# V6_01.net
KiCad netlist of a schematic drawn in Altium Designer
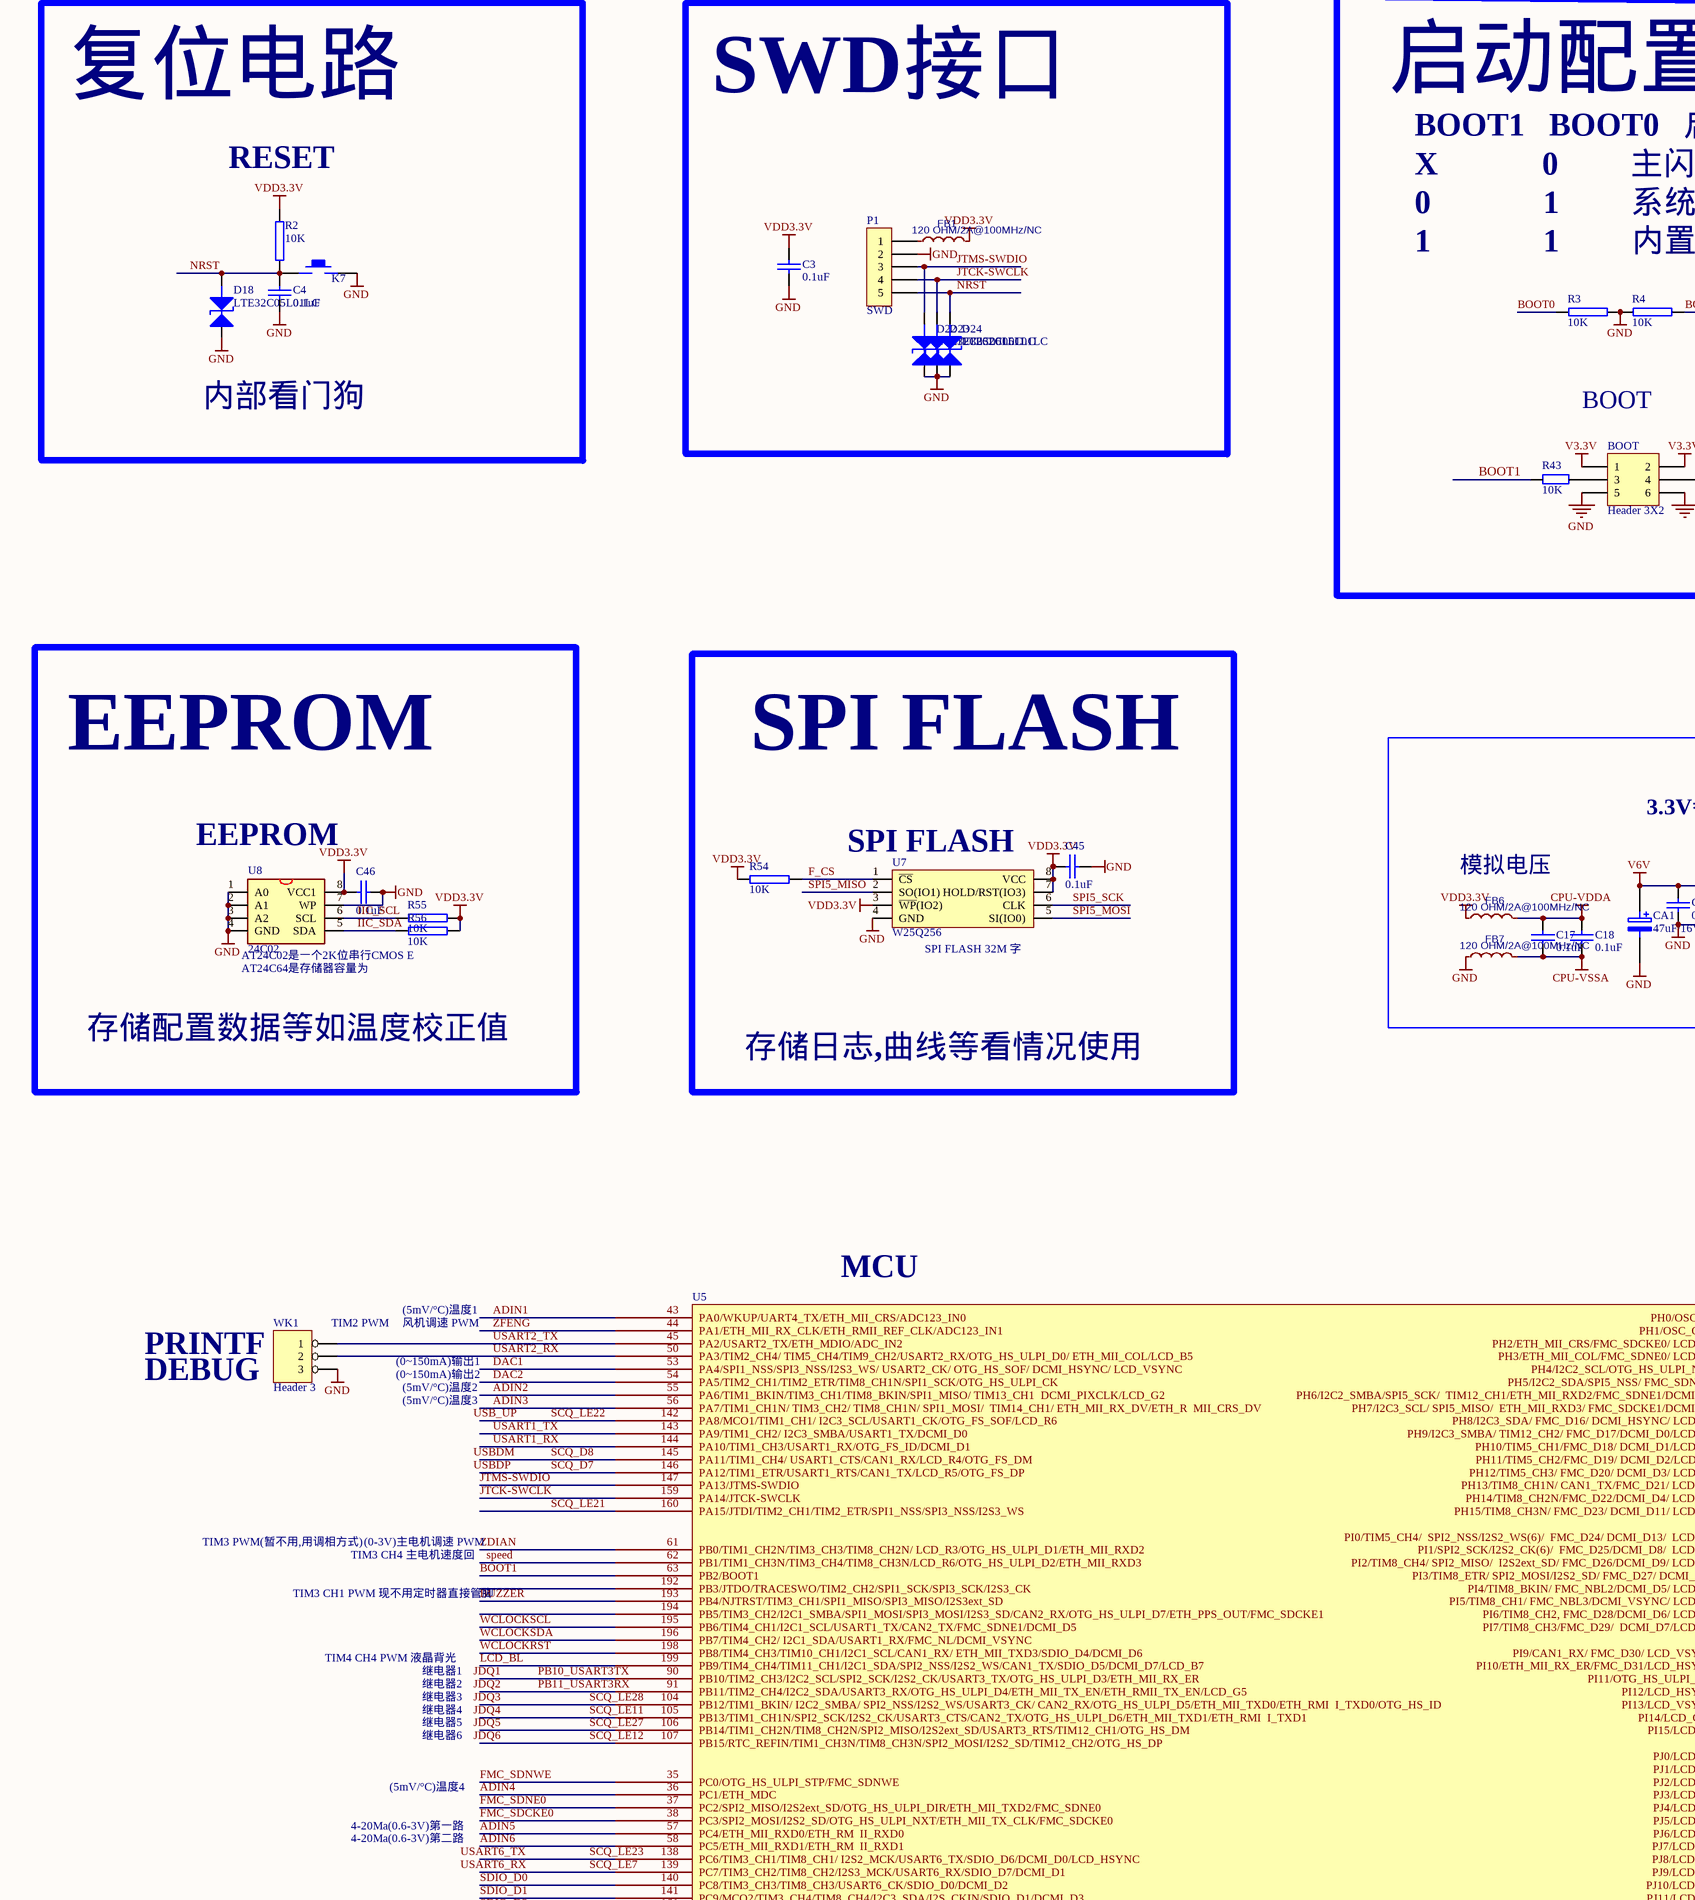
[diagram p0: 盲人学习机V6.01.SchDoc, top left]
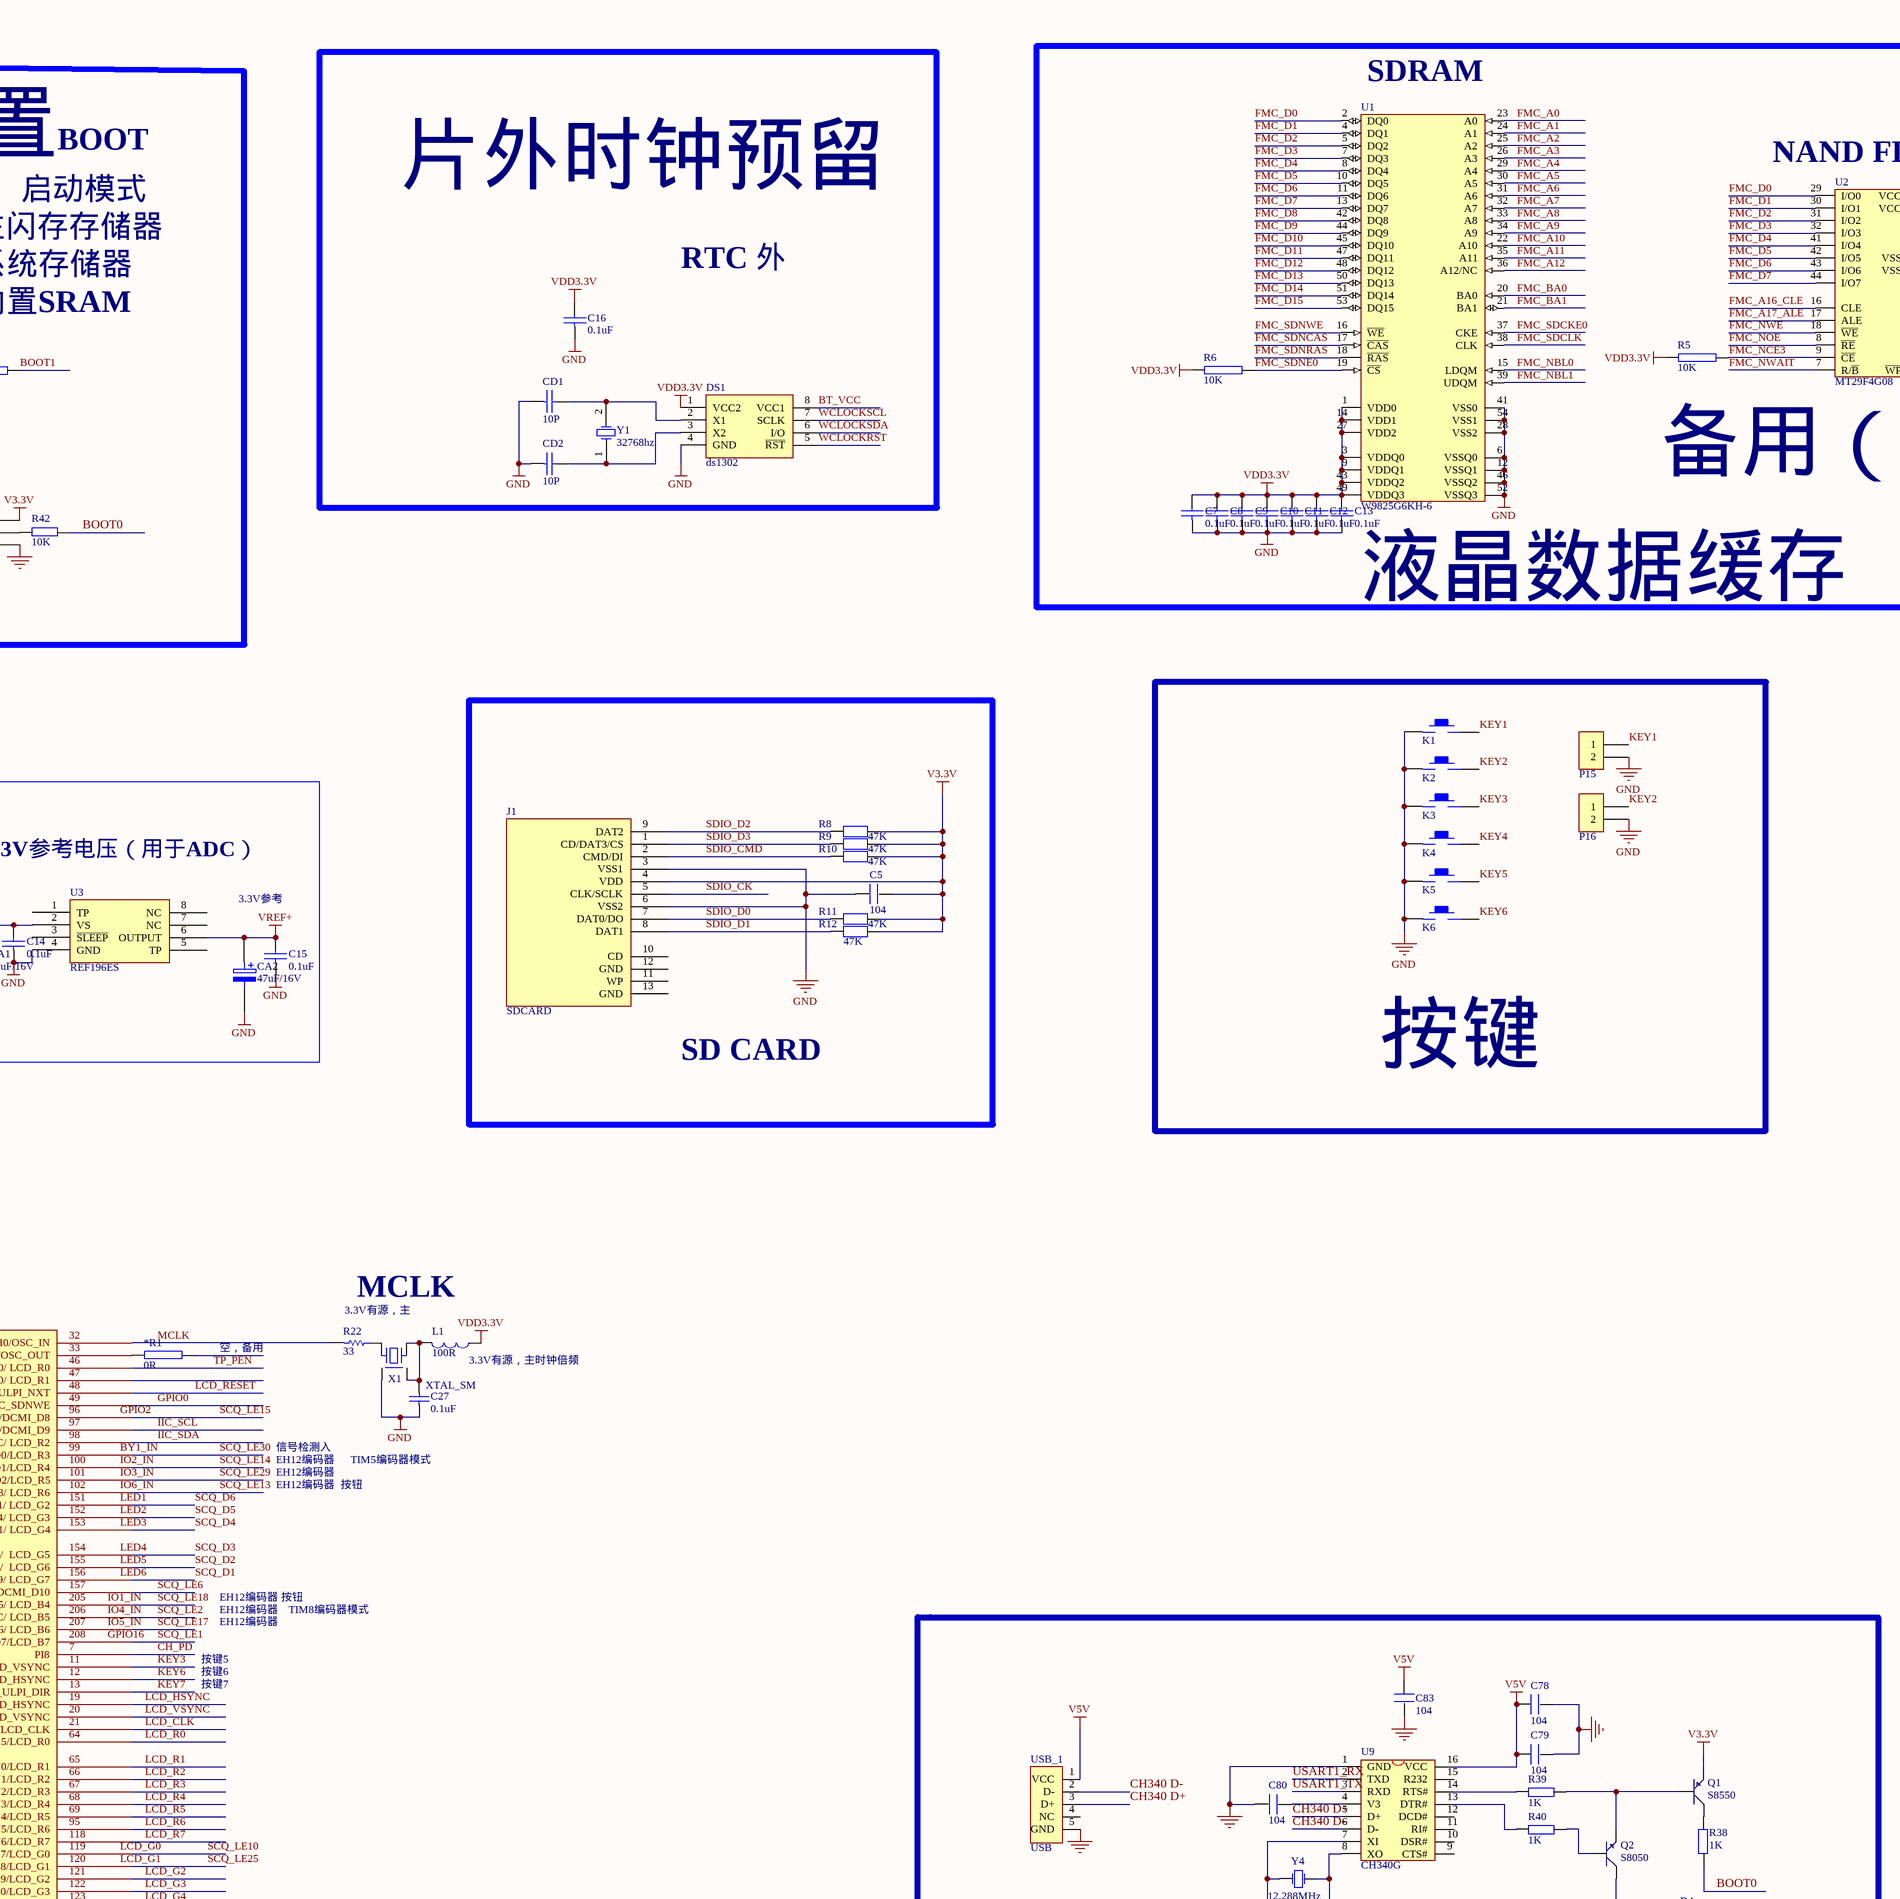
[diagram p1: 盲人学习机V6.01.SchDoc, top middle]
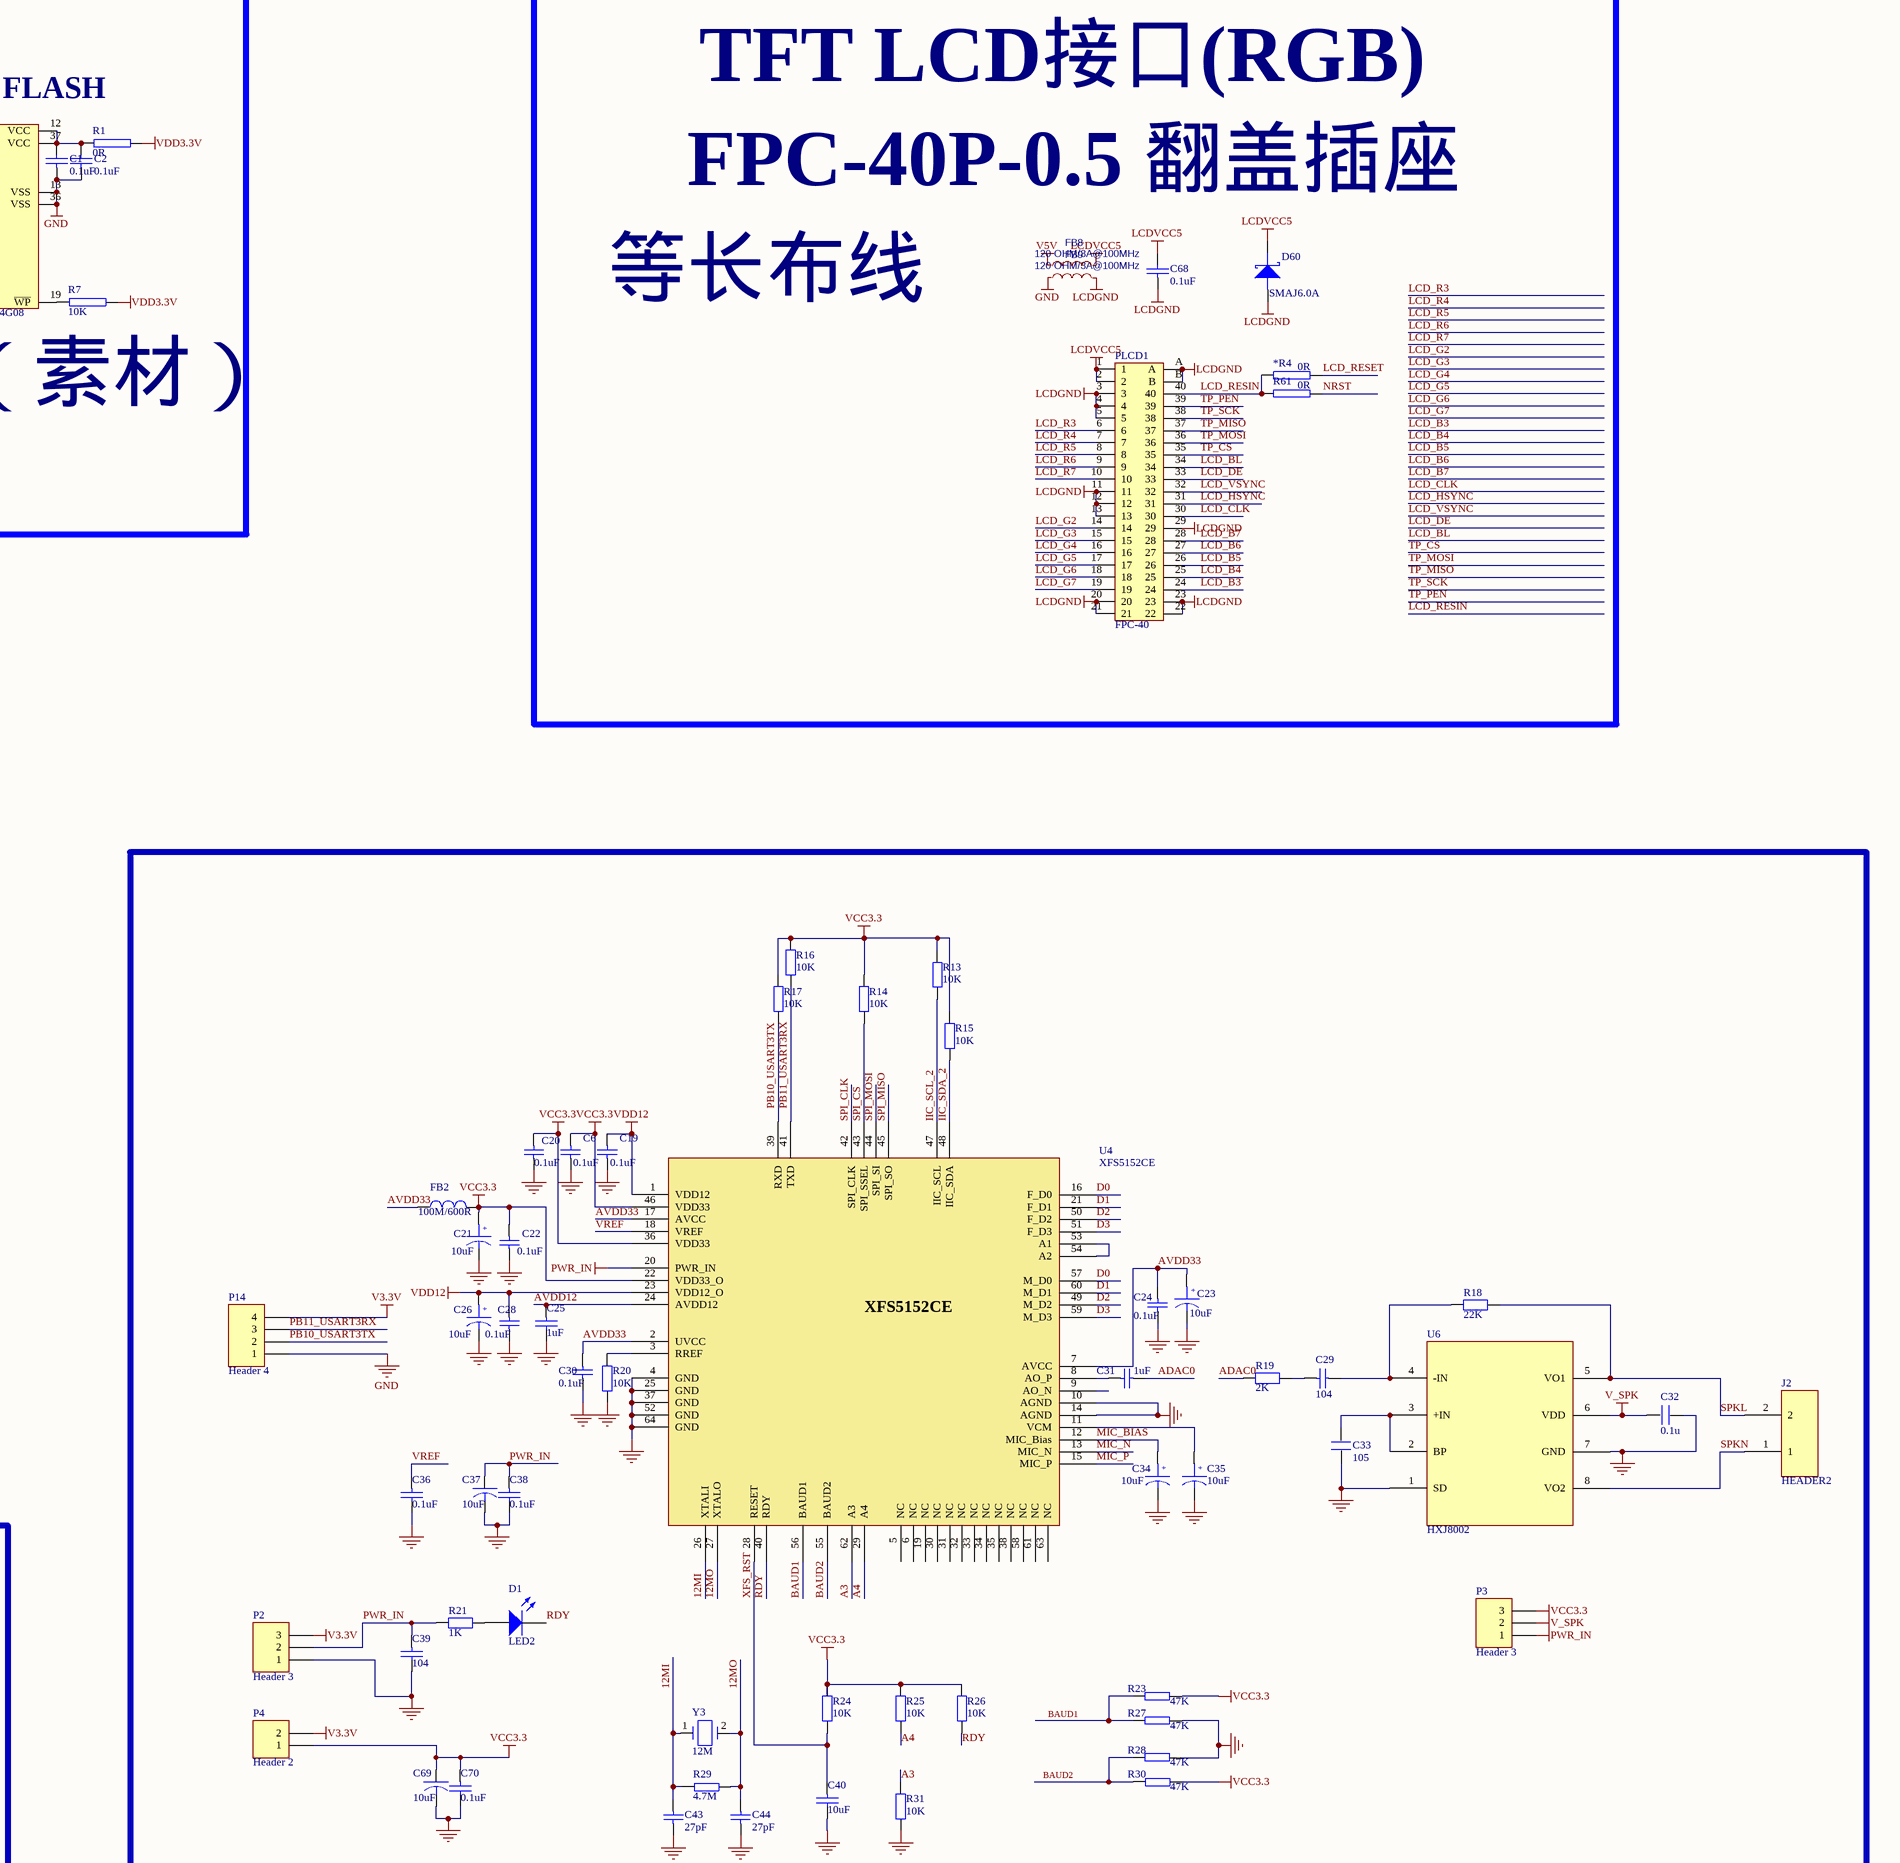
[diagram p2: 盲人学习机V6.01.SchDoc, top right]
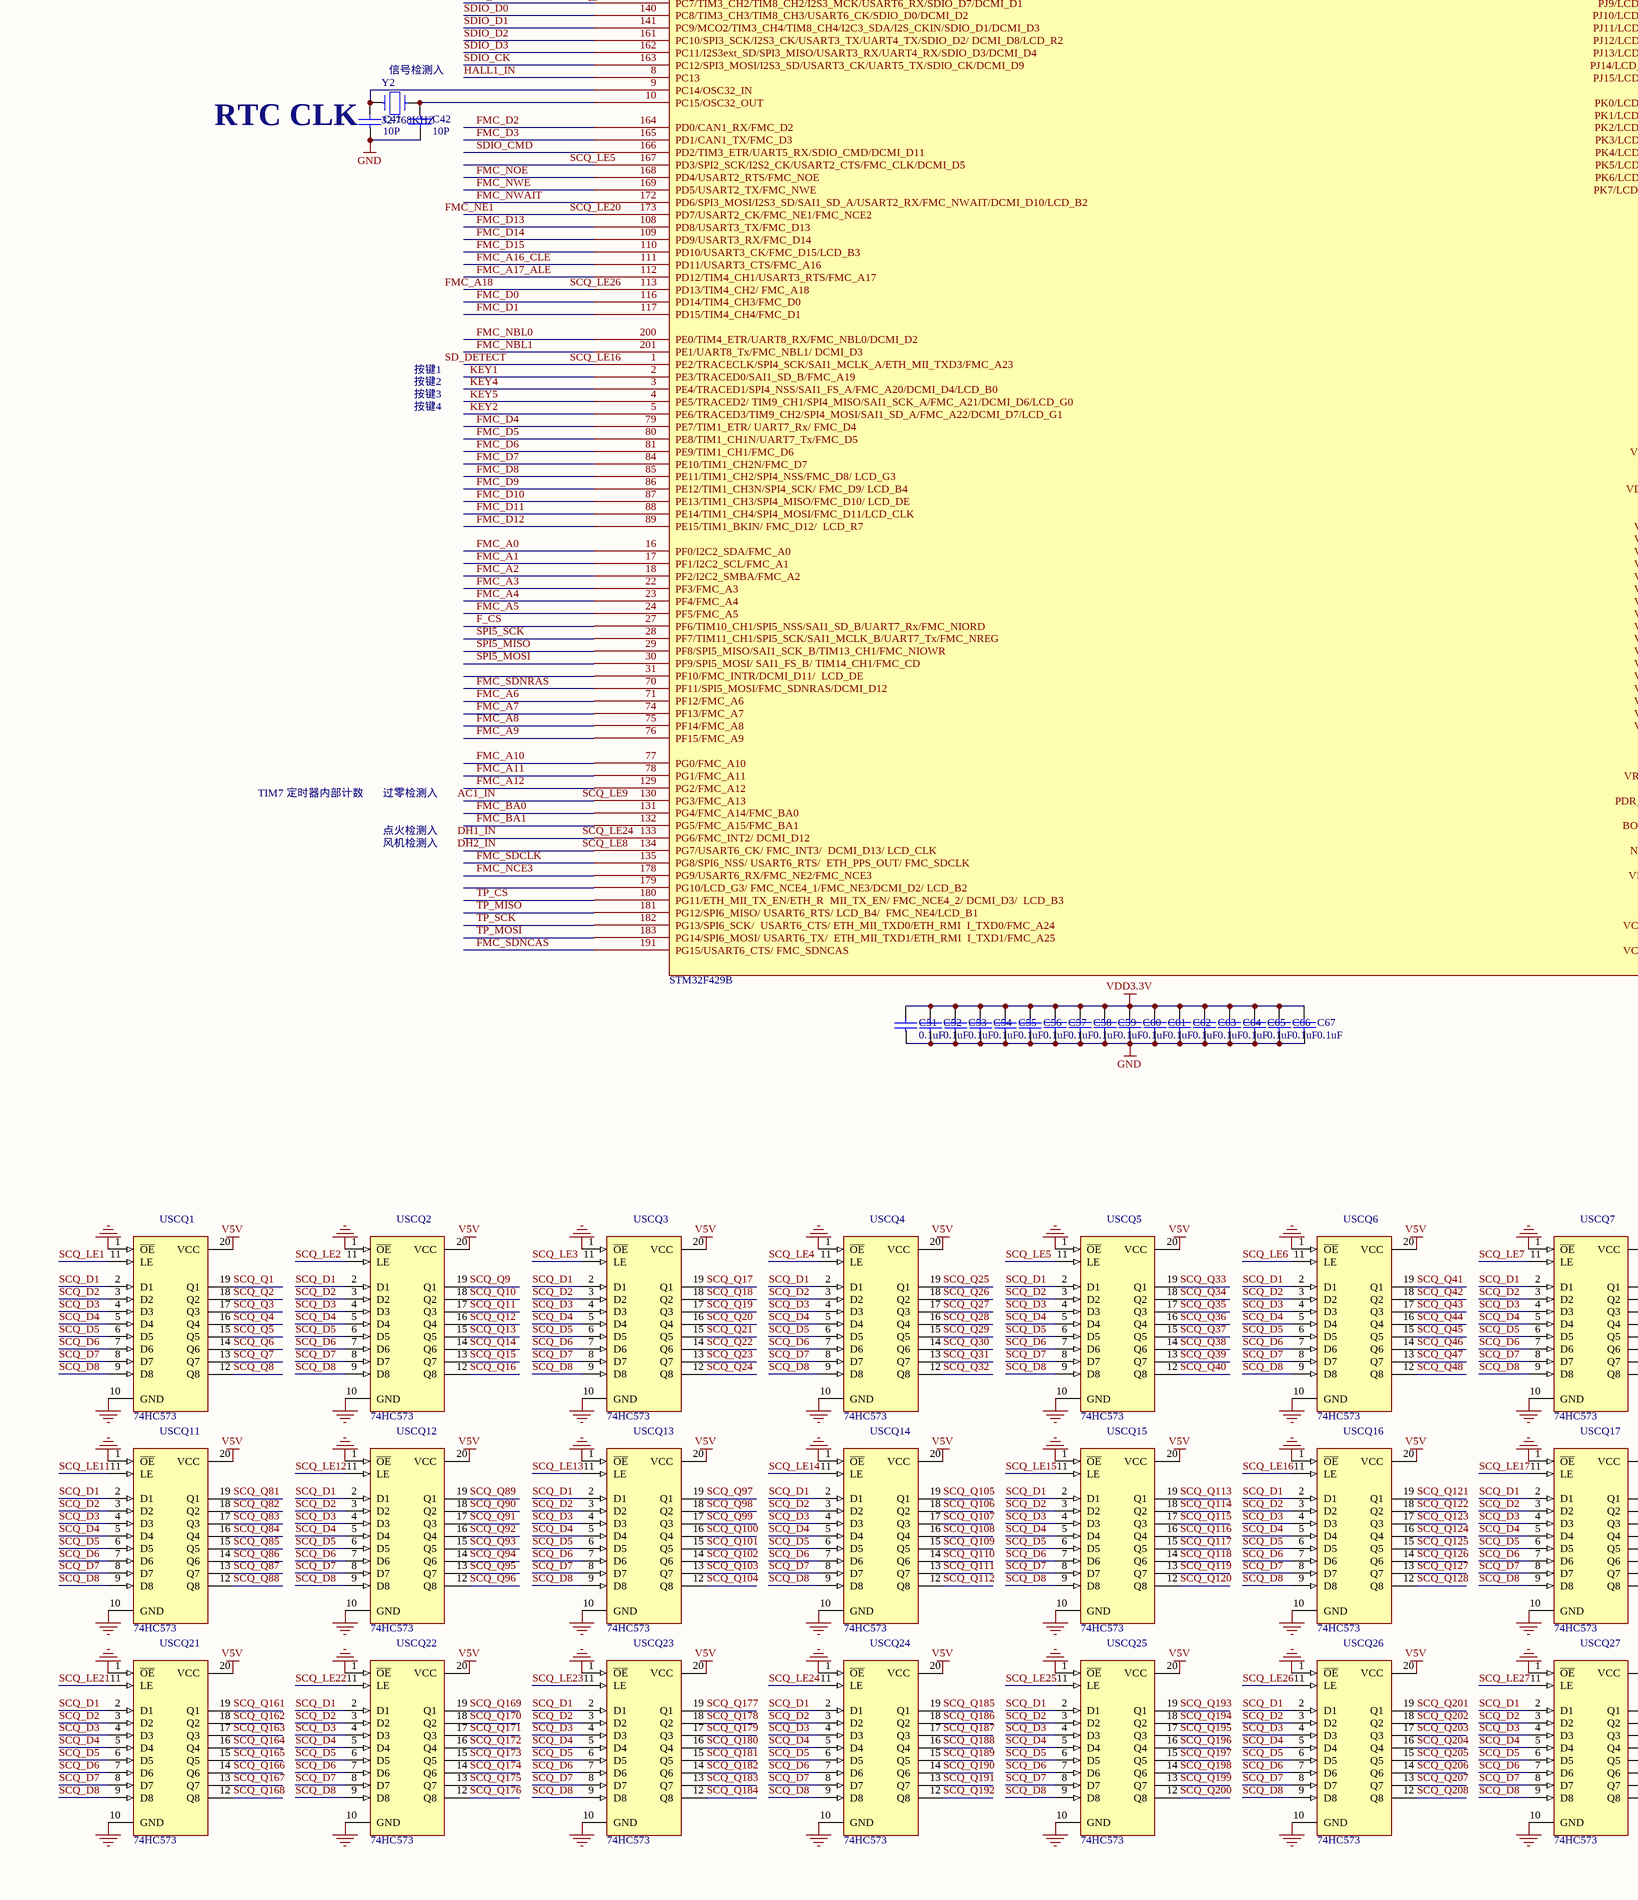
[diagram p3: 盲人学习机V6.01.SchDoc, bottom left]
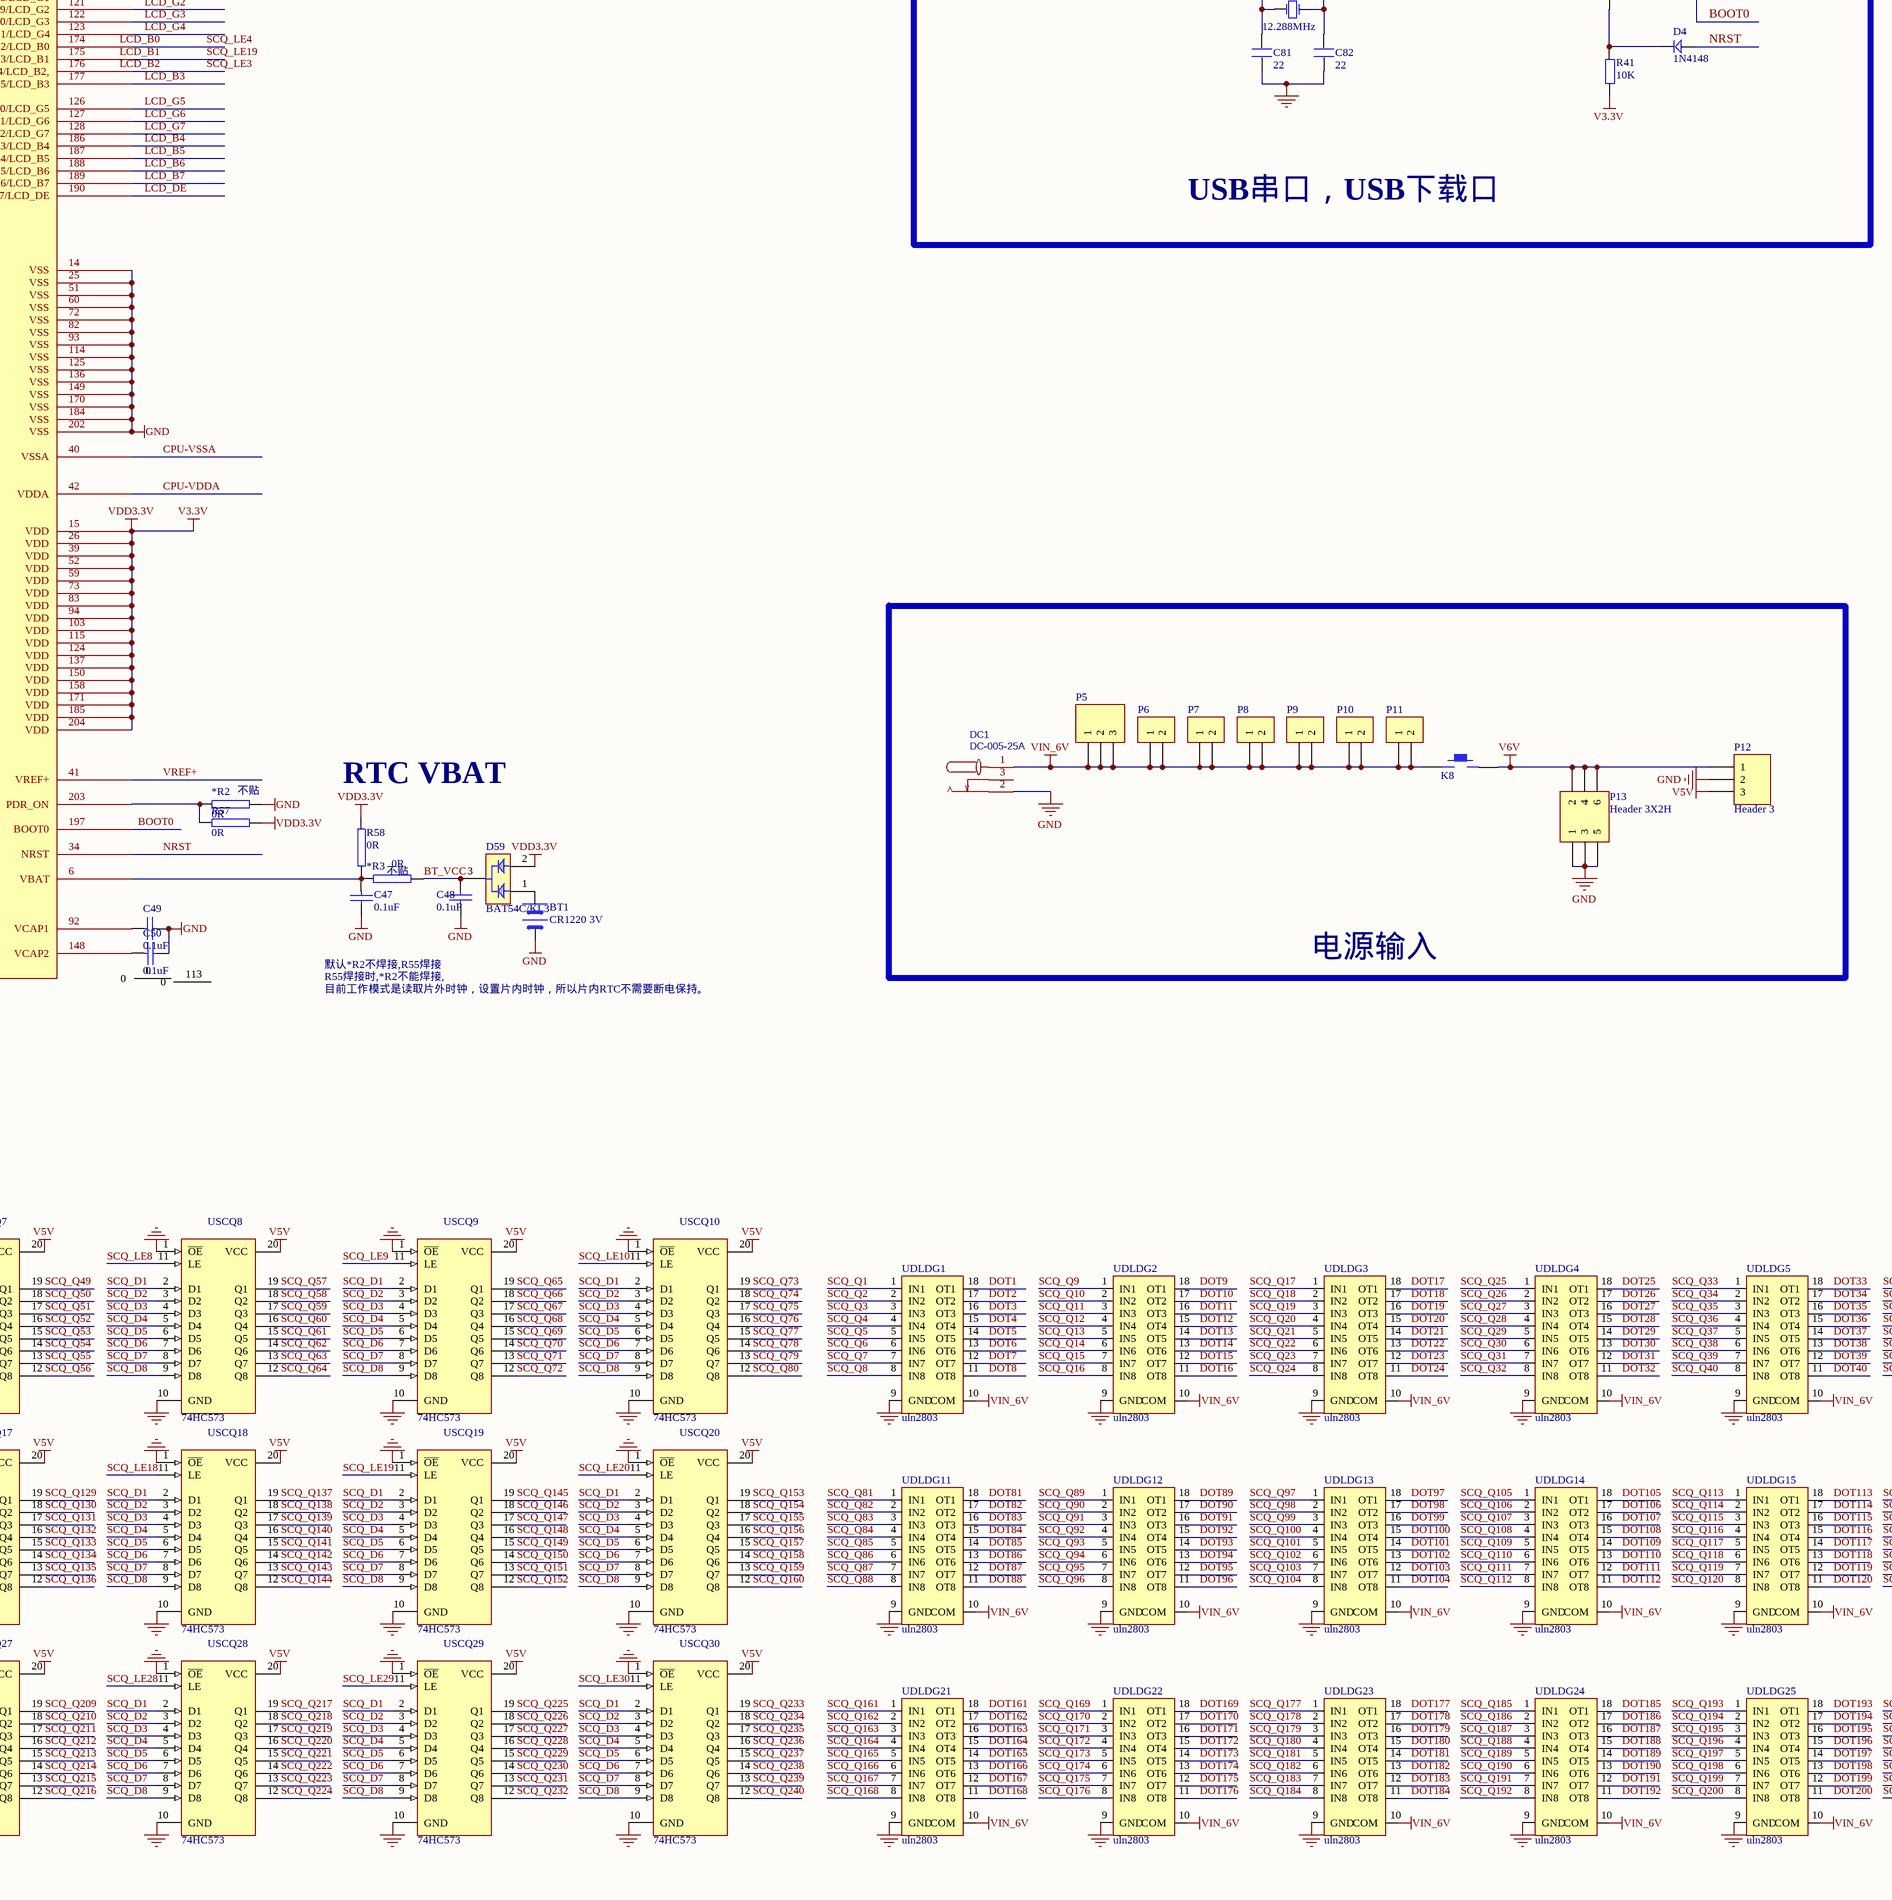
[diagram p4: 盲人学习机V6.01.SchDoc, bottom middle]
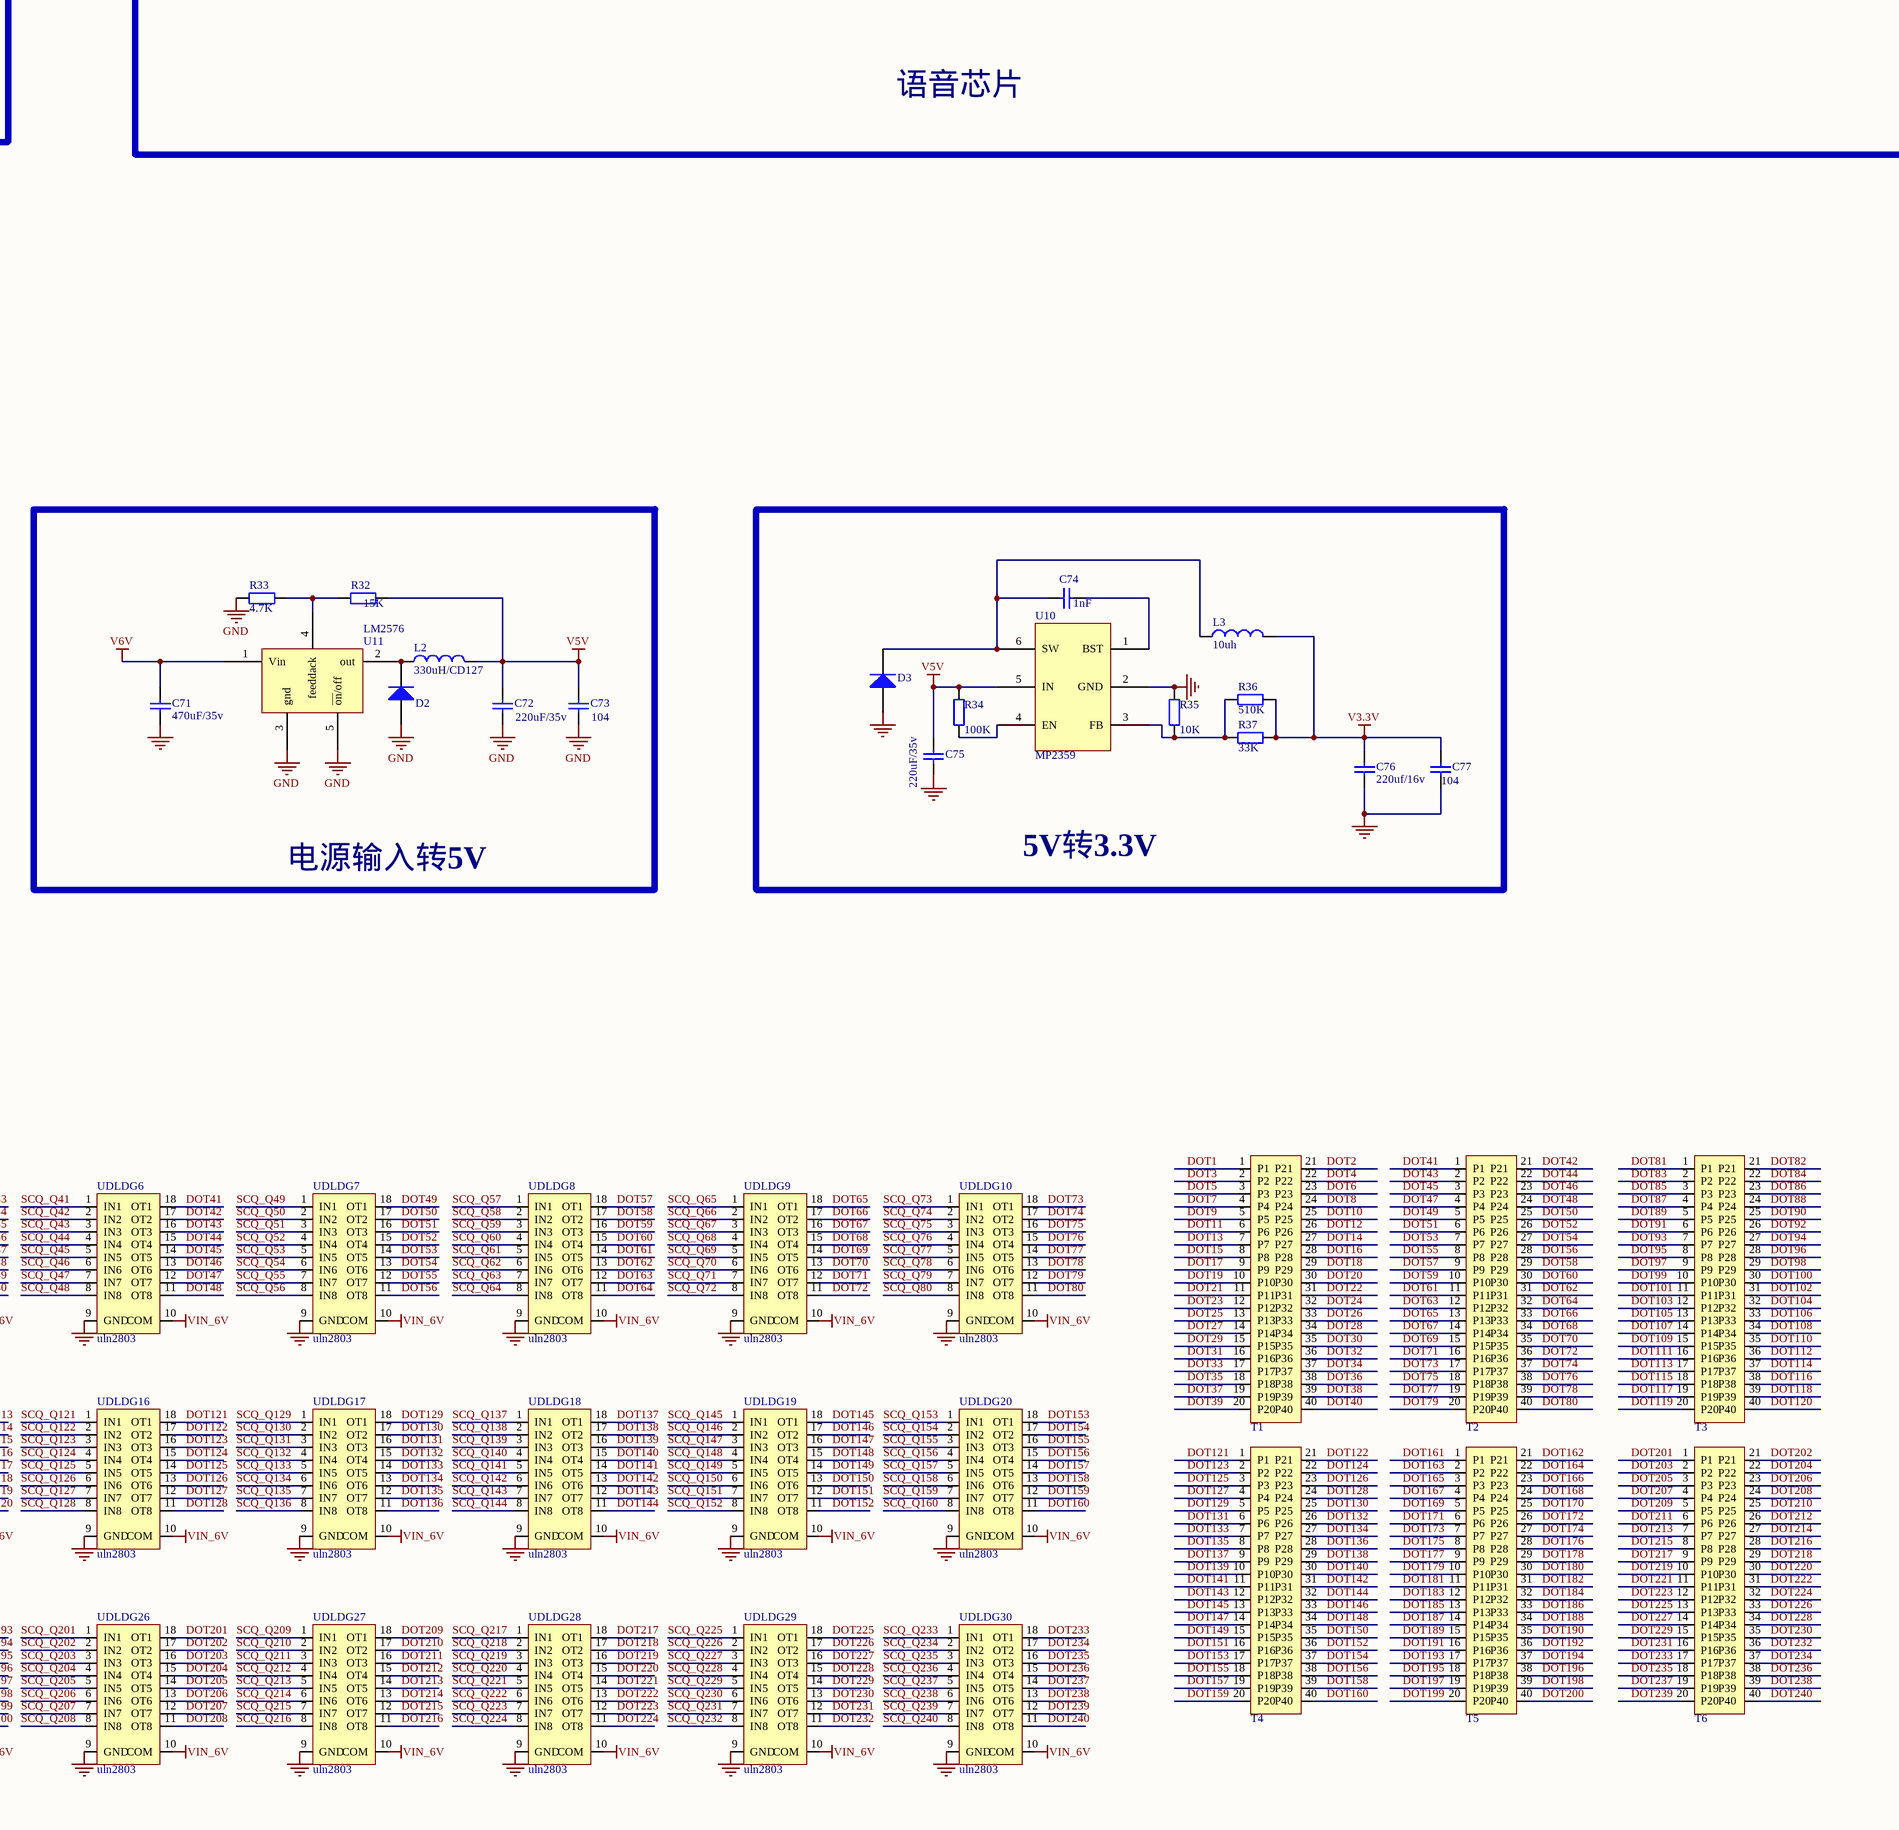
[diagram p5: 盲人学习机V6.01.SchDoc, bottom right]

(export (version "E")
  (design (tool "Eeschema 10.0.6"))
  (components
    (comp (ref "*R1") (value "0R") (footprint "0603R") (libsource (lib "*") (part "RES2")))
    (comp (ref "*R2") (value "0R") (footprint "0603R") (libsource (lib "*") (part "RES2")))
    (comp (ref "*R3") (value "0R") (footprint "0603R") (libsource (lib "") (part "RES2_1")))
    (comp (ref "*R4") (value "0R") (footprint "0603R") (libsource (lib "*") (part "RES2")))
    (comp (ref "BOOT")
      (value "Header 3X2")
      (footprint "HDR2X3")
      (description "Header, 3-Pin, Dual row")
      (fields (field (name "PUBLISHER") "Altium Limited"))
      (libsource (lib "战舰STM32开发板底板封装库") (part "Header 3X2"))
    )
    (comp (ref "BT1") (value "CR1220 3V") (footprint "CR1220-1") (libsource (lib "*") (part "BATTERY")))
    (comp (ref "C1")
      (value "0.1uF")
      (footprint "0603C")
      (description "Capacitor")
      (libsource (lib "*") (part "CAP"))
    )
    (comp (ref "C2")
      (value "0.1uF")
      (footprint "0603C")
      (description "Capacitor")
      (libsource (lib "*") (part "CAP"))
    )
    (comp (ref "C3")
      (value "0.1uF")
      (footprint "0603C")
      (description "Capacitor")
      (libsource (lib "*") (part "CAP"))
    )
    (comp (ref "C4")
      (value "0.1uF")
      (footprint "0603C")
      (description "Capacitor")
      (libsource (lib "*") (part "CAP"))
    )
    (comp (ref "C5") (value "104") (footprint "0603C") (libsource (lib "液晶模块封装库") (part "C")))
    (comp (ref "C6")
      (value "0.1uF")
      (footprint "0603C")
      (description "电容")
      (fields (field (name "PUBLISHER") "Altium Limited"))
      (libsource (lib "*") (part "Cap NP"))
    )
    (comp (ref "C7")
      (value "0.1uF")
      (footprint "0603C")
      (description "Capacitor")
      (libsource (lib "*") (part "CAP"))
    )
    (comp (ref "C8")
      (value "0.1uF")
      (footprint "0603C")
      (description "Capacitor")
      (libsource (lib "*") (part "CAP"))
    )
    (comp (ref "C9")
      (value "0.1uF")
      (footprint "0603C")
      (description "Capacitor")
      (libsource (lib "*") (part "CAP"))
    )
    (comp (ref "C10")
      (value "0.1uF")
      (footprint "0603C")
      (description "Capacitor")
      (libsource (lib "*") (part "CAP"))
    )
    (comp (ref "C11")
      (value "0.1uF")
      (footprint "0603C")
      (description "Capacitor")
      (libsource (lib "*") (part "CAP"))
    )
    (comp (ref "C12")
      (value "0.1uF")
      (footprint "0603C")
      (description "Capacitor")
      (libsource (lib "*") (part "CAP"))
    )
    (comp (ref "C13")
      (value "0.1uF")
      (footprint "0603C")
      (description "Capacitor")
      (libsource (lib "*") (part "CAP"))
    )
    (comp (ref "C14")
      (value "0.1uF")
      (footprint "0603C")
      (description "Capacitor")
      (libsource (lib "*") (part "CAP"))
    )
    (comp (ref "C15")
      (value "0.1uF")
      (footprint "0603C")
      (description "Capacitor")
      (libsource (lib "*") (part "CAP"))
    )
    (comp (ref "C16")
      (value "0.1uF")
      (footprint "0603C")
      (description "Capacitor")
      (libsource (lib "*") (part "CAP"))
    )
    (comp (ref "C17")
      (value "0.1uF")
      (footprint "0603C")
      (description "Capacitor")
      (libsource (lib "*") (part "CAP"))
    )
    (comp (ref "C18")
      (value "0.1uF")
      (footprint "0603C")
      (description "Capacitor")
      (libsource (lib "*") (part "CAP"))
    )
    (comp (ref "C19")
      (value "0.1uF")
      (footprint "0603C")
      (description "电容")
      (fields (field (name "PUBLISHER") "Altium Limited"))
      (libsource (lib "*") (part "Cap NP"))
    )
    (comp (ref "C20")
      (value "0.1uF")
      (footprint "0603C")
      (description "电容")
      (fields (field (name "PUBLISHER") "Altium Limited"))
      (libsource (lib "*") (part "Cap NP"))
    )
    (comp (ref "C21") (value "10uF") (footprint "0805C") (libsource (lib "*") (part "CAP POL")))
    (comp (ref "C22")
      (value "0.1uF")
      (footprint "0603C")
      (description "电容")
      (fields (field (name "PUBLISHER") "Altium Limited"))
      (libsource (lib "*") (part "Cap NP"))
    )
    (comp (ref "C23") (value "10uF") (footprint "0805C") (libsource (lib "*") (part "CAP POL")))
    (comp (ref "C24")
      (value "0.1uF")
      (footprint "0603C")
      (description "电容")
      (fields (field (name "PUBLISHER") "Altium Limited"))
      (libsource (lib "*") (part "Cap NP"))
    )
    (comp (ref "C25")
      (value "1uF")
      (footprint "0603C")
      (description "Capacitor")
      (libsource (lib "*") (part "CAP"))
    )
    (comp (ref "C26") (value "10uF") (footprint "0805C") (libsource (lib "*") (part "CAP POL")))
    (comp (ref "C27")
      (value "0.1uF")
      (footprint "0603C")
      (description "1nF")
      (fields (field (name "Comment") "Cap S1") (field (name "PUBLISHER") "Altium Limited"))
      (libsource (lib "*") (part "Cap S1"))
    )
    (comp (ref "C28")
      (value "0.1uF")
      (footprint "0603C")
      (description "电容")
      (fields (field (name "PUBLISHER") "Altium Limited"))
      (libsource (lib "*") (part "Cap NP"))
    )
    (comp (ref "C29")
      (value "104")
      (footprint "0603C")
      (description "电容")
      (fields (field (name "PUBLISHER") "Altium Limited"))
      (libsource (lib "*") (part "Cap NP"))
    )
    (comp (ref "C30")
      (value "0.1uF")
      (footprint "0603C")
      (description "电容")
      (fields (field (name "PUBLISHER") "Altium Limited"))
      (libsource (lib "*") (part "Cap NP"))
    )
    (comp (ref "C31")
      (value "1uF")
      (footprint "0603C")
      (description "电容")
      (fields (field (name "PUBLISHER") "Altium Limited"))
      (libsource (lib "*") (part "Cap NP"))
    )
    (comp (ref "C32") (value "0.1u") (footprint "0603C") (libsource (lib "战舰STM32开发板底板封装库") (part "C")))
    (comp (ref "C33") (value "105") (footprint "0603C") (libsource (lib "战舰STM32开发板底板封装库") (part "C")))
    (comp (ref "C34") (value "10uF") (footprint "0805C") (libsource (lib "*") (part "CAP POL")))
    (comp (ref "C35") (value "10uF") (footprint "0805C") (libsource (lib "*") (part "CAP POL")))
    (comp (ref "C36")
      (value "0.1uF")
      (footprint "0603C")
      (description "Capacitor")
      (libsource (lib "*") (part "CAP"))
    )
    (comp (ref "C37")
      (value "10uF")
      (footprint "0805C")
      (description "Capacitor")
      (libsource (lib "*") (part "CAPACITOR"))
    )
    (comp (ref "C38")
      (value "0.1uF")
      (footprint "0603C")
      (description "Capacitor")
      (libsource (lib "*") (part "CAP"))
    )
    (comp (ref "C39")
      (value "104")
      (footprint "0603C")
      (description "Capacitor")
      (libsource (lib "*") (part "CAP"))
    )
    (comp (ref "C40")
      (value "10uF")
      (footprint "0603C")
      (description "Capacitor")
      (libsource (lib "*") (part "CAP"))
    )
    (comp (ref "C41")
      (value "10P")
      (footprint "0603C")
      (description "Capacitor")
      (libsource (lib "*") (part "CAP"))
    )
    (comp (ref "C42")
      (value "10P")
      (footprint "0603C")
      (description "Capacitor")
      (libsource (lib "*") (part "CAP"))
    )
    (comp (ref "C43")
      (value "27pF")
      (footprint "0603C")
      (description "电容")
      (fields (field (name "PUBLISHER") "Altium Limited"))
      (libsource (lib "*") (part "Cap NP"))
    )
    (comp (ref "C44")
      (value "27pF")
      (footprint "0603C")
      (description "电容")
      (fields (field (name "PUBLISHER") "Altium Limited"))
      (libsource (lib "*") (part "Cap NP"))
    )
    (comp (ref "C45")
      (value "0.1uF")
      (footprint "0603C")
      (description "Capacitor")
      (libsource (lib "*") (part "CAP"))
    )
    (comp (ref "C46")
      (value "0.1uF")
      (footprint "0603C")
      (description "Capacitor")
      (libsource (lib "*") (part "CAP"))
    )
    (comp (ref "C47")
      (value "0.1uF")
      (footprint "0603C")
      (description "Capacitor")
      (libsource (lib "*") (part "CAP"))
    )
    (comp (ref "C48")
      (value "0.1uF")
      (footprint "0603C")
      (description "Capacitor")
      (libsource (lib "") (part "CAP_1"))
    )
    (comp (ref "C49")
      (value "0.1uF")
      (footprint "0603C")
      (description "Capacitor")
      (libsource (lib "*") (part "CAP"))
    )
    (comp (ref "C50")
      (value "0.1uF")
      (footprint "0603C")
      (description "Capacitor")
      (libsource (lib "*") (part "CAP"))
    )
    (comp (ref "C51")
      (value "0.1uF")
      (footprint "0603C")
      (description "Capacitor")
      (libsource (lib "*") (part "CAP"))
    )
    (comp (ref "C52")
      (value "0.1uF")
      (footprint "0603C")
      (description "Capacitor")
      (libsource (lib "*") (part "CAP"))
    )
    (comp (ref "C53")
      (value "0.1uF")
      (footprint "0603C")
      (description "Capacitor")
      (libsource (lib "*") (part "CAP"))
    )
    (comp (ref "C54")
      (value "0.1uF")
      (footprint "0603C")
      (description "Capacitor")
      (libsource (lib "*") (part "CAP"))
    )
    (comp (ref "C55")
      (value "0.1uF")
      (footprint "0603C")
      (description "Capacitor")
      (libsource (lib "*") (part "CAP"))
    )
    (comp (ref "C56")
      (value "0.1uF")
      (footprint "0603C")
      (description "Capacitor")
      (libsource (lib "*") (part "CAP"))
    )
    (comp (ref "C57")
      (value "0.1uF")
      (footprint "0603C")
      (description "Capacitor")
      (libsource (lib "*") (part "CAP"))
    )
    (comp (ref "C58")
      (value "0.1uF")
      (footprint "0603C")
      (description "Capacitor")
      (libsource (lib "*") (part "CAP"))
    )
    (comp (ref "C59")
      (value "0.1uF")
      (footprint "0603C")
      (description "Capacitor")
      (libsource (lib "*") (part "CAP"))
    )
    (comp (ref "C60")
      (value "0.1uF")
      (footprint "0603C")
      (description "Capacitor")
      (libsource (lib "*") (part "CAP"))
    )
    (comp (ref "C61")
      (value "0.1uF")
      (footprint "0603C")
      (description "Capacitor")
      (libsource (lib "*") (part "CAP"))
    )
    (comp (ref "C62")
      (value "0.1uF")
      (footprint "0603C")
      (description "Capacitor")
      (libsource (lib "*") (part "CAP"))
    )
    (comp (ref "C63")
      (value "0.1uF")
      (footprint "0603C")
      (description "Capacitor")
      (libsource (lib "*") (part "CAP"))
    )
    (comp (ref "C64")
      (value "0.1uF")
      (footprint "0603C")
      (description "Capacitor")
      (libsource (lib "*") (part "CAP"))
    )
    (comp (ref "C65")
      (value "0.1uF")
      (footprint "0603C")
      (description "Capacitor")
      (libsource (lib "*") (part "CAP"))
    )
    (comp (ref "C66")
      (value "0.1uF")
      (footprint "0603C")
      (description "Capacitor")
      (libsource (lib "*") (part "CAP"))
    )
    (comp (ref "C67")
      (value "0.1uF")
      (footprint "0603C")
      (description "Capacitor")
      (libsource (lib "*") (part "CAP"))
    )
    (comp (ref "C68")
      (value "0.1uF")
      (footprint "0603C")
      (description "Capacitor")
      (libsource (lib "*") (part "CAP"))
    )
    (comp (ref "C69")
      (value "10uF")
      (footprint "0805C")
      (description "Capacitor")
      (libsource (lib "*") (part "CAPACITOR"))
    )
    (comp (ref "C70")
      (value "0.1uF")
      (footprint "0603C")
      (description "Capacitor")
      (libsource (lib "*") (part "CAP"))
    )
    (comp (ref "C71")
      (value "470uF/35v")
      (footprint "C-1010-S")
      (description "Capacitor")
      (fields (field (name "PUBLISHER") "Altium Limited"))
      (libsource (lib "Miscellaneous Devices") (part "Cap"))
    )
    (comp (ref "C72")
      (value "220uF/35v")
      (footprint "C-0808-S")
      (description "Capacitor")
      (fields (field (name "PUBLISHER") "Altium Limited"))
      (libsource (lib "Miscellaneous Devices") (part "Cap"))
    )
    (comp (ref "C73")
      (value "104")
      (footprint "0603C")
      (description "Capacitor")
      (fields (field (name "PUBLISHER") "Altium Limited"))
      (libsource (lib "Miscellaneous Devices") (part "Cap"))
    )
    (comp (ref "C74")
      (value "1nF")
      (footprint "0603C")
      (description "Capacitor")
      (fields (field (name "PUBLISHER") "Altium Limited"))
      (libsource (lib "Miscellaneous Devices") (part "Cap"))
    )
    (comp (ref "C75")
      (value "220uF/35v")
      (footprint "C-0808-S")
      (description "Capacitor")
      (fields (field (name "PUBLISHER") "Altium Limited"))
      (libsource (lib "Miscellaneous Devices") (part "Cap"))
    )
    (comp (ref "C76")
      (value "220uf/16v")
      (footprint "C-0808-S")
      (description "Capacitor")
      (fields (field (name "PUBLISHER") "Altium Limited"))
      (libsource (lib "Miscellaneous Devices") (part "Cap"))
    )
    (comp (ref "C77")
      (value "104")
      (footprint "0603C")
      (description "Capacitor")
      (fields (field (name "PUBLISHER") "Altium Limited"))
      (libsource (lib "Miscellaneous Devices") (part "Cap"))
    )
    (comp (ref "C78") (value "104") (footprint "0603C") (libsource (lib "战舰STM32开发板底板封装库") (part "C")))
    (comp (ref "C79") (value "104") (footprint "0603C") (libsource (lib "战舰STM32开发板底板封装库") (part "C")))
    (comp (ref "C80") (value "104") (footprint "0603C") (libsource (lib "战舰STM32开发板底板封装库") (part "C")))
    (comp (ref "C81") (value "22") (footprint "0603C") (libsource (lib "战舰STM32开发板底板封装库") (part "C")))
    (comp (ref "C82") (value "22") (footprint "0603C") (libsource (lib "战舰STM32开发板底板封装库") (part "C")))
    (comp (ref "C83") (value "104") (footprint "0603C") (libsource (lib "战舰STM32开发板底板封装库") (part "C")))
    (comp (ref "CA1")
      (value "47uF/16V")
      (footprint "C1210")
      (description "Electrolytic Capacitor")
      (libsource (lib "*") (part "ELECTRO2"))
    )
    (comp (ref "CA2")
      (value "47uF/16V")
      (footprint "C1210")
      (description "Electrolytic Capacitor")
      (libsource (lib "*") (part "ELECTRO2"))
    )
    (comp (ref "CD1")
      (value "10P")
      (footprint "0603C")
      (description "Capacitor")
      (libsource (lib "*") (part "CAP"))
    )
    (comp (ref "CD2")
      (value "10P")
      (footprint "0603C")
      (description "Capacitor")
      (libsource (lib "*") (part "CAP"))
    )
    (comp (ref "D1")
      (value "LED2")
      (footprint "3.2X1.6X1.1")
      (description "Typical RED, GREEN, YELLOW, AMBER GaAs LED")
      (fields (field (name "PUBLISHER") "Altium Limited"))
      (libsource (lib "Miscellaneous Devices") (part "LED2"))
    )
    (comp (ref "D2")
      (value "~")
      (footprint "DO-214AA")
      (description "Default Diode")
      (fields (field (name "PUBLISHER") "Altium Limited"))
      (libsource (lib "Miscellaneous Devices") (part "Diode"))
    )
    (comp (ref "D3")
      (value "~")
      (footprint "1206D-N")
      (description "Default Diode")
      (fields (field (name "PUBLISHER") "Altium Limited"))
      (libsource (lib "Miscellaneous Devices") (part "Diode"))
    )
    (comp (ref "D4") (value "1N4148") (footprint "DIODE_SOP") (libsource (lib "战舰STM32开发板底板封装库") (part "D")))
    (comp (ref "D18")
      (value "LTE32C05L01LC")
      (footprint "SOD-323")
      (description "Zener Diode")
      (libsource (lib "*") (part "ZENER2"))
    )
    (comp (ref "D22")
      (value "LTE32C05L01LC")
      (footprint "SOD-323")
      (description "Zener Diode")
      (libsource (lib "*") (part "ZENER2"))
    )
    (comp (ref "D23")
      (value "LTE32C05L01LC")
      (footprint "SOD-323")
      (description "Zener Diode")
      (libsource (lib "*") (part "ZENER2"))
    )
    (comp (ref "D24")
      (value "LTE32C05L01LC")
      (footprint "SOD-323")
      (description "Zener Diode")
      (libsource (lib "*") (part "ZENER2"))
    )
    (comp (ref "D59") (value "BAT54C/KL3") (footprint "SOT-23") (libsource (lib "*") (part "BAT54C/KL3")))
    (comp (ref "D60")
      (value "SMAJ6.0A")
      (footprint "DO-214AB")
      (description "Schottky Diode")
      (libsource (lib "*") (part "DIODE SCHOTTKY"))
    )
    (comp (ref "DC1")
      (value "DC-005-25A")
      (footprint "DC10B")
      (fields (field (name "BOM_SUPPLIER PART") "C136715") (field (name "CONTRIBUTOR") "LCSC"))
      (libsource (lib "altium-import") (part "root_0_DC-005-25A_"))
    )
    (comp (ref "DS1") (value "ds1302") (footprint "SO-8N") (libsource (lib "*") (part "ds1302")))
    (comp (ref "FB1")
      (value "120 OHM/2A@100MHz/NC")
      (footprint "SL0603")
      (fields
        (field (name "BOM_MANUFACTURER PART") "BLM18PG121SN1D")
        (field (name "BOM_SUPPLIER PART") "C73100")
      )
      (libsource (lib "*") (part "120 OHM/2A@100MHz"))
    )
    (comp (ref "FB2")
      (value "100M/600R")
      (footprint "0603R")
      (description "磁珠")
      (fields (field (name "PUBLISHER") "Altium Limited"))
      (libsource (lib "*") (part "Fbead"))
    )
    (comp (ref "FB6")
      (value "120 OHM/2A@100MHz/NC")
      (footprint "SL0603")
      (fields
        (field (name "BOM_MANUFACTURER PART") "BLM18PG121SN1D")
        (field (name "BOM_SUPPLIER PART") "C73100")
      )
      (libsource (lib "*") (part "120 OHM/2A@100MHz"))
    )
    (comp (ref "FB7")
      (value "120 OHM/2A@100MHz/NC")
      (footprint "SL0603")
      (fields
        (field (name "BOM_MANUFACTURER PART") "BLM18PG121SN1D")
        (field (name "BOM_SUPPLIER PART") "C73100")
      )
      (libsource (lib "*") (part "120 OHM/2A@100MHz"))
    )
    (comp (ref "FB8")
      (value "120 OHM/3A@100MHz")
      (footprint "SL0805")
      (fields
        (field (name "BOM_MANUFACTURER PART") "BLM21PG121SN1D")
        (field (name "BOM_SUPPLIER PART") "C79382")
      )
      (libsource (lib "*") (part "120 OHM/3A@100MHz"))
    )
    (comp (ref "FB9")
      (value "120 OHM/3A@100MHz")
      (footprint "SL0805")
      (fields
        (field (name "BOM_MANUFACTURER PART") "BLM21PG121SN1D")
        (field (name "BOM_SUPPLIER PART") "C79382")
      )
      (libsource (lib "*") (part "120 OHM/3A@100MHz"))
    )
    (comp (ref "J1")
      (value "SDCARD")
      (footprint "SDCARD_L")
      (description "SD卡自弹")
      (libsource (lib "founder") (part "SDCARD"))
    )
    (comp (ref "J2") (value "HEADER2") (footprint "HDR1X2") (libsource (lib "v6原理图") (part "HEADER2")))
    (comp (ref "K1") (value "KEY_M") (footprint "KEY_M") (libsource (lib "战舰STM32开发板底板封装库") (part "KEY_M")))
    (comp (ref "K2") (value "KEY_M") (footprint "KEY_M") (libsource (lib "战舰STM32开发板底板封装库") (part "KEY_M")))
    (comp (ref "K3") (value "KEY_M") (footprint "KEY_M") (libsource (lib "战舰STM32开发板底板封装库") (part "KEY_M")))
    (comp (ref "K4") (value "KEY_M") (footprint "KEY_M") (libsource (lib "战舰STM32开发板底板封装库") (part "KEY_M")))
    (comp (ref "K5") (value "KEY_M") (footprint "KEY_M") (libsource (lib "战舰STM32开发板底板封装库") (part "KEY_M")))
    (comp (ref "K6") (value "KEY_M") (footprint "KEY_M") (libsource (lib "战舰STM32开发板底板封装库") (part "KEY_M")))
    (comp (ref "K7") (value "KEY_M") (footprint "KEY_M") (libsource (lib "战舰STM32开发板底板封装库") (part "KEY_M")))
    (comp (ref "K8") (value "KEY_M") (footprint "BTN8.5*8.5") (libsource (lib "") (part "KEY_M_1")))
    (comp (ref "L1")
      (value "100R")
      (footprint "0603R")
      (description "INDUCTOR")
      (libsource (lib "*") (part "INDUCTOR1"))
    )
    (comp (ref "L2")
      (value "~")
      (footprint "L1270")
      (description "Inductor")
      (fields (field (name "L1") "330uH/CD127") (field (name "PUBLISHER") "Altium Limited"))
      (libsource (lib "Miscellaneous Devices") (part "Inductor"))
    )
    (comp (ref "L3")
      (value "~")
      (footprint "L0630")
      (description "Inductor")
      (fields (field (name "L1") "10uh") (field (name "PUBLISHER") "Altium Limited"))
      (libsource (lib "") (part "Inductor_1"))
    )
    (comp (ref "P1")
      (value "SWD")
      (footprint "CON5_2.5_1")
      (description "Connector")
      (libsource (lib "*") (part "CON5"))
    )
    (comp (ref "P2")
      (value "Header 3")
      (footprint "HDR1X3")
      (description "Header, 3-Pin")
      (fields (field (name "PUBLISHER") "Altium Limited"))
      (libsource (lib "Miscellaneous Connectors") (part "Header 3"))
    )
    (comp (ref "P3")
      (value "Header 3")
      (footprint "HDR1X3")
      (description "Header, 3-Pin")
      (fields (field (name "PUBLISHER") "Altium Limited"))
      (libsource (lib "Miscellaneous Connectors") (part "Header 3"))
    )
    (comp (ref "P4")
      (value "Header 2")
      (footprint "HDR1X2")
      (description "Header, 2-Pin")
      (fields (field (name "PUBLISHER") "Altium Limited"))
      (libsource (lib "Miscellaneous Connectors") (part "Header 2"))
    )
    (comp (ref "P5")
      (value "Header 3")
      (footprint "HDR1X3")
      (description "Header, 3-Pin")
      (fields (field (name "PUBLISHER") "Altium Limited"))
      (libsource (lib "") (part "Header 3_1"))
    )
    (comp (ref "P6")
      (value "CON2")
      (footprint "N1A")
      (description "Connector")
      (libsource (lib "一排") (part "CON2"))
    )
    (comp (ref "P7")
      (value "CON2")
      (footprint "N1A")
      (description "Connector")
      (libsource (lib "一排") (part "CON2"))
    )
    (comp (ref "P8")
      (value "CON2")
      (footprint "N1A")
      (description "Connector")
      (libsource (lib "一排") (part "CON2"))
    )
    (comp (ref "P9")
      (value "CON2")
      (footprint "N1A")
      (description "Connector")
      (libsource (lib "一排") (part "CON2"))
    )
    (comp (ref "P10")
      (value "CON2")
      (footprint "N1A")
      (description "Connector")
      (libsource (lib "一排") (part "CON2"))
    )
    (comp (ref "P11")
      (value "CON2")
      (footprint "N1A")
      (description "Connector")
      (libsource (lib "一排") (part "CON2"))
    )
    (comp (ref "P12")
      (value "Header 3")
      (footprint "HDR1X3")
      (description "Header, 3-Pin")
      (fields (field (name "PUBLISHER") "Altium Limited"))
      (libsource (lib "") (part "Header 3_2"))
    )
    (comp (ref "P13")
      (value "Header 3X2H")
      (footprint "HDR2X3")
      (description "Header, 3-Pin, Dual row, Right Angle")
      (fields (field (name "PUBLISHER") "Altium Limited"))
      (libsource (lib "Miscellaneous Connectors") (part "Header 3X2H"))
    )
    (comp (ref "P14")
      (value "Header 4")
      (footprint "Header 2.54X4")
      (description "Header, 4-Pin")
      (fields (field (name "PUBLISHER") "Altium Limited"))
      (libsource (lib "Miscellaneous Connectors") (part "Header 4"))
    )
    (comp (ref "P15")
      (value "CON2")
      (footprint "HDR1X2")
      (description "Connector")
      (libsource (lib "") (part "CON2_1"))
    )
    (comp (ref "P16")
      (value "CON2")
      (footprint "HDR1X2")
      (description "Connector")
      (libsource (lib "") (part "CON2_1"))
    )
    (comp (ref "PLCD1") (value "FPC-40") (footprint "FPC-TOP40") (libsource (lib "*") (part "FPC-40")))
    (comp (ref "Q1")
      (value "S8550")
      (footprint "SOT-23R")
      (description "8550/BCW68")
      (libsource (lib "战舰STM32开发板底板封装库") (part "PNP"))
    )
    (comp (ref "Q2")
      (value "S8050")
      (footprint "SOT-23R")
      (description "8050/BCW846/BCW847")
      (libsource (lib "战舰STM32开发板底板封装库") (part "NPN"))
    )
    (comp (ref "R1") (value "0R") (footprint "0603R") (libsource (lib "*") (part "RES2")))
    (comp (ref "R2") (value "10K") (footprint "0603R") (libsource (lib "*") (part "RES2")))
    (comp (ref "R3") (value "10K") (footprint "0603R") (libsource (lib "*") (part "RES2")))
    (comp (ref "R4") (value "10K") (footprint "0603R") (libsource (lib "*") (part "RES2")))
    (comp (ref "R5") (value "10K") (footprint "0603R") (libsource (lib "*") (part "RES2")))
    (comp (ref "R6") (value "10K") (footprint "0603R") (libsource (lib "*") (part "RES2")))
    (comp (ref "R7") (value "10K") (footprint "0603R") (libsource (lib "*") (part "RES2")))
    (comp (ref "R8")
      (value "47K")
      (footprint "0603R")
      (description "贴片电阻")
      (fields (field (name "Comment") "Res1") (field (name "PUBLISHER") "Altium Limited"))
      (libsource (lib "founder") (part "Res1"))
    )
    (comp (ref "R9")
      (value "47K")
      (footprint "0603R")
      (description "贴片电阻")
      (fields (field (name "Comment") "Res1") (field (name "PUBLISHER") "Altium Limited"))
      (libsource (lib "founder") (part "Res1"))
    )
    (comp (ref "R10")
      (value "47K")
      (footprint "0603R")
      (description "贴片电阻")
      (fields (field (name "Comment") "Res1") (field (name "PUBLISHER") "Altium Limited"))
      (libsource (lib "founder") (part "Res1"))
    )
    (comp (ref "R11")
      (value "47K")
      (footprint "0603R")
      (description "贴片电阻")
      (fields (field (name "Comment") "Res1") (field (name "PUBLISHER") "Altium Limited"))
      (libsource (lib "founder") (part "Res1"))
    )
    (comp (ref "R12")
      (value "47K")
      (footprint "0603R")
      (description "贴片电阻")
      (fields (field (name "Comment") "Res1") (field (name "PUBLISHER") "Altium Limited"))
      (libsource (lib "founder") (part "Res1"))
    )
    (comp (ref "R13")
      (value "10K")
      (footprint "R0603")
      (description "Resistor")
      (fields (field (name "PUBLISHER") "Altium Limited"))
      (libsource (lib "*") (part "Res2"))
    )
    (comp (ref "R14")
      (value "10K")
      (footprint "R0603")
      (description "Resistor")
      (fields (field (name "PUBLISHER") "Altium Limited"))
      (libsource (lib "*") (part "Res2"))
    )
    (comp (ref "R15")
      (value "10K")
      (footprint "R0603")
      (description "Resistor")
      (fields (field (name "PUBLISHER") "Altium Limited"))
      (libsource (lib "*") (part "Res2"))
    )
    (comp (ref "R16")
      (value "10K")
      (footprint "R0603")
      (description "Resistor")
      (fields (field (name "PUBLISHER") "Altium Limited"))
      (libsource (lib "*") (part "Res2"))
    )
    (comp (ref "R17")
      (value "10K")
      (footprint "R0603")
      (description "Resistor")
      (fields (field (name "PUBLISHER") "Altium Limited"))
      (libsource (lib "*") (part "Res2"))
    )
    (comp (ref "R18")
      (value "22K")
      (footprint "R0603")
      (description "Resistor")
      (fields (field (name "PUBLISHER") "Altium Limited"))
      (libsource (lib "") (part "Res2_3"))
    )
    (comp (ref "R19")
      (value "2K")
      (footprint "R0603")
      (description "Resistor")
      (fields (field (name "Comment") "10K") (field (name "PUBLISHER") "Altium Limited"))
      (libsource (lib "") (part "Res2_3"))
    )
    (comp (ref "R20")
      (value "10K")
      (footprint "R0603")
      (description "Resistor")
      (fields (field (name "PUBLISHER") "Altium Limited"))
      (libsource (lib "") (part "Res2_1"))
    )
    (comp (ref "R21")
      (value "1K")
      (footprint "R0603")
      (description "Resistor")
      (fields (field (name "Comment") "10K") (field (name "PUBLISHER") "Altium Limited"))
      (libsource (lib "") (part "Res2_2"))
    )
    (comp (ref "R22")
      (value "33")
      (footprint "0603R")
      (fields (field (name "Comment") "R1-S") (field (name "PUBLISHER") "Altium Limited"))
      (libsource (lib "*") (part "R1-S"))
    )
    (comp (ref "R23")
      (value "47K")
      (footprint "R0603")
      (description "电阻")
      (libsource (lib "") (part "RES2_2"))
    )
    (comp (ref "R24")
      (value "10K")
      (footprint "R0603")
      (description "Resistor")
      (fields (field (name "PUBLISHER") "Altium Limited"))
      (libsource (lib "*") (part "Res2"))
    )
    (comp (ref "R25")
      (value "10K")
      (footprint "R0603")
      (description "Resistor")
      (fields (field (name "PUBLISHER") "Altium Limited"))
      (libsource (lib "*") (part "Res2"))
    )
    (comp (ref "R26")
      (value "10K")
      (footprint "R0603")
      (description "Resistor")
      (fields (field (name "PUBLISHER") "Altium Limited"))
      (libsource (lib "") (part "Res2_1"))
    )
    (comp (ref "R27")
      (value "47K")
      (footprint "R0603")
      (description "电阻")
      (libsource (lib "") (part "RES2_2"))
    )
    (comp (ref "R28")
      (value "47K")
      (footprint "R0603")
      (description "电阻")
      (libsource (lib "") (part "RES2_2"))
    )
    (comp (ref "R29")
      (value "4.7M")
      (footprint "R0603")
      (description "电阻")
      (libsource (lib "") (part "RES2_2"))
    )
    (comp (ref "R30")
      (value "47K")
      (footprint "R0603")
      (description "电阻")
      (libsource (lib "") (part "RES2_2"))
    )
    (comp (ref "R31")
      (value "10K")
      (footprint "R0603")
      (description "Resistor")
      (fields (field (name "PUBLISHER") "Altium Limited"))
      (libsource (lib "") (part "Res2_1"))
    )
    (comp (ref "R32")
      (value "15K")
      (footprint "0603R")
      (description "Resistor")
      (fields (field (name "PUBLISHER") "Altium Limited"))
      (libsource (lib "") (part "Res2_2"))
    )
    (comp (ref "R33")
      (value "4.7K")
      (footprint "0603R")
      (description "Resistor")
      (fields (field (name "PUBLISHER") "Altium Limited"))
      (libsource (lib "Miscellaneous Devices") (part "Res2"))
    )
    (comp (ref "R34")
      (value "100K")
      (footprint "0603R")
      (description "Resistor")
      (fields (field (name "PUBLISHER") "Altium Limited"))
      (libsource (lib "") (part "Res2_1"))
    )
    (comp (ref "R35")
      (value "10K")
      (footprint "0603R")
      (description "Resistor")
      (fields (field (name "PUBLISHER") "Altium Limited"))
      (libsource (lib "") (part "Res2_1"))
    )
    (comp (ref "R36")
      (value "510K")
      (footprint "0603R")
      (description "Resistor")
      (fields (field (name "PUBLISHER") "Altium Limited"))
      (libsource (lib "Miscellaneous Devices") (part "Res2"))
    )
    (comp (ref "R37")
      (value "33K")
      (footprint "0603R")
      (description "Resistor")
      (fields (field (name "PUBLISHER") "Altium Limited"))
      (libsource (lib "Miscellaneous Devices") (part "Res2"))
    )
    (comp (ref "R38") (value "1K") (footprint "0603R") (libsource (lib "战舰STM32开发板底板封装库") (part "R")))
    (comp (ref "R39") (value "1K") (footprint "0603R") (libsource (lib "战舰STM32开发板底板封装库") (part "R")))
    (comp (ref "R40") (value "1K") (footprint "0603R") (libsource (lib "战舰STM32开发板底板封装库") (part "R")))
    (comp (ref "R41") (value "10K") (footprint "0603R") (libsource (lib "战舰STM32开发板底板封装库") (part "R")))
    (comp (ref "R42") (value "10K") (footprint "0603R") (libsource (lib "战舰STM32开发板底板封装库") (part "R")))
    (comp (ref "R43") (value "10K") (footprint "0603R") (libsource (lib "战舰STM32开发板底板封装库") (part "R")))
    (comp (ref "R54") (value "10K") (footprint "0603R") (libsource (lib "*") (part "RES2")))
    (comp (ref "R55") (value "10K") (footprint "0603R") (libsource (lib "*") (part "RES2")))
    (comp (ref "R56") (value "10K") (footprint "0603R") (libsource (lib "*") (part "RES2")))
    (comp (ref "R57") (value "0R") (footprint "0603R") (libsource (lib "*") (part "RES2")))
    (comp (ref "R58") (value "0R") (footprint "0603R") (libsource (lib "") (part "RES2_1")))
    (comp (ref "R61") (value "0R") (footprint "0603R") (libsource (lib "*") (part "RES2")))
    (comp (ref "T1") (value "dubangxian") (footprint "杜邦线插脚") (libsource (lib "一排原理图库") (part "dubangxian")))
    (comp (ref "T2") (value "dubangxian") (footprint "杜邦线插脚") (libsource (lib "一排原理图库") (part "dubangxian")))
    (comp (ref "T3") (value "dubangxian") (footprint "杜邦线插脚") (libsource (lib "一排原理图库") (part "dubangxian")))
    (comp (ref "T4") (value "dubangxian") (footprint "杜邦线插脚") (libsource (lib "一排原理图库") (part "dubangxian")))
    (comp (ref "T5") (value "dubangxian") (footprint "杜邦线插脚") (libsource (lib "一排原理图库") (part "dubangxian")))
    (comp (ref "T6") (value "dubangxian") (footprint "杜邦线插脚") (libsource (lib "一排原理图库") (part "dubangxian")))
    (comp (ref "U1")
      (value "W9825G6KH-6")
      (footprint "TSOP54")
      (description "32MB SDRAM")
      (libsource (lib "*") (part "IS42S16160B"))
    )
    (comp (ref "U2")
      (value "MT29F4G08")
      (footprint "TSOP48")
      (description "256MB NAND FLASH")
      (libsource (lib "*") (part "K9F2G08U0C"))
    )
    (comp (ref "U3") (value "REF196ES") (footprint "SO-8N") (libsource (lib "*") (part "REF195ES")))
    (comp (ref "U4") (value "XFS5152CE") (footprint "LQFP64_N") (libsource (lib "*") (part "XFS5152-2")))
    (comp (ref "U5")
      (value "STM32F429B")
      (footprint "STM32F429_LQFP208")
      (libsource (lib "*") (part "STM32F429B"))
    )
    (comp (ref "U6") (value "HXJ8002") (footprint "SO-8") (libsource (lib "v6原理图") (part "HXJ8002")))
    (comp (ref "U7")
      (value "W25Q256")
      (footprint "SOP8-K")
      (description "W25Q128")
      (libsource (lib "*") (part "W25Q128"))
    )
    (comp (ref "U8")
      (value "24C02")
      (footprint "SO-8N")
      (description "EEPROM")
      (libsource (lib "*") (part "24C256"))
    )
    (comp (ref "U9")
      (value "CH340G")
      (footprint "SOP16M")
      (description "USB2UART")
      (libsource (lib "战舰STM32开发板底板封装库") (part "CH340G"))
    )
    (comp (ref "U10") (value "MP2359") (footprint "SOT-26A") (libsource (lib "v6原理图") (part "MP2359")))
    (comp (ref "U11") (value "LM2576") (footprint "TO-263") (libsource (lib "*") (part "LM2576-ADJ")))
    (comp (ref "UDLDG1") (value "uln2803") (footprint "sol-18") (libsource (lib "MW原理图库") (part "uln2803")))
    (comp (ref "UDLDG2") (value "uln2803") (footprint "sol-18") (libsource (lib "MW原理图库") (part "uln2803")))
    (comp (ref "UDLDG3") (value "uln2803") (footprint "sol-18") (libsource (lib "MW原理图库") (part "uln2803")))
    (comp (ref "UDLDG4") (value "uln2803") (footprint "sol-18") (libsource (lib "MW原理图库") (part "uln2803")))
    (comp (ref "UDLDG5") (value "uln2803") (footprint "sol-18") (libsource (lib "MW原理图库") (part "uln2803")))
    (comp (ref "UDLDG6") (value "uln2803") (footprint "sol-18") (libsource (lib "MW原理图库") (part "uln2803")))
    (comp (ref "UDLDG7") (value "uln2803") (footprint "sol-18") (libsource (lib "MW原理图库") (part "uln2803")))
    (comp (ref "UDLDG8") (value "uln2803") (footprint "sol-18") (libsource (lib "MW原理图库") (part "uln2803")))
    (comp (ref "UDLDG9") (value "uln2803") (footprint "sol-18") (libsource (lib "MW原理图库") (part "uln2803")))
    (comp (ref "UDLDG10") (value "uln2803") (footprint "sol-18") (libsource (lib "MW原理图库") (part "uln2803")))
    (comp (ref "UDLDG11") (value "uln2803") (footprint "sol-18") (libsource (lib "MW原理图库") (part "uln2803")))
    (comp (ref "UDLDG12") (value "uln2803") (footprint "sol-18") (libsource (lib "MW原理图库") (part "uln2803")))
    (comp (ref "UDLDG13") (value "uln2803") (footprint "sol-18") (libsource (lib "MW原理图库") (part "uln2803")))
    (comp (ref "UDLDG14") (value "uln2803") (footprint "sol-18") (libsource (lib "MW原理图库") (part "uln2803")))
    (comp (ref "UDLDG15") (value "uln2803") (footprint "sol-18") (libsource (lib "MW原理图库") (part "uln2803")))
    (comp (ref "UDLDG16") (value "uln2803") (footprint "sol-18") (libsource (lib "MW原理图库") (part "uln2803")))
    (comp (ref "UDLDG17") (value "uln2803") (footprint "sol-18") (libsource (lib "MW原理图库") (part "uln2803")))
    (comp (ref "UDLDG18") (value "uln2803") (footprint "sol-18") (libsource (lib "MW原理图库") (part "uln2803")))
    (comp (ref "UDLDG19") (value "uln2803") (footprint "sol-18") (libsource (lib "MW原理图库") (part "uln2803")))
    (comp (ref "UDLDG20") (value "uln2803") (footprint "sol-18") (libsource (lib "MW原理图库") (part "uln2803")))
    (comp (ref "UDLDG21") (value "uln2803") (footprint "sol-18") (libsource (lib "MW原理图库") (part "uln2803")))
    (comp (ref "UDLDG22") (value "uln2803") (footprint "sol-18") (libsource (lib "MW原理图库") (part "uln2803")))
    (comp (ref "UDLDG23") (value "uln2803") (footprint "sol-18") (libsource (lib "MW原理图库") (part "uln2803")))
    (comp (ref "UDLDG24") (value "uln2803") (footprint "sol-18") (libsource (lib "MW原理图库") (part "uln2803")))
    (comp (ref "UDLDG25") (value "uln2803") (footprint "sol-18") (libsource (lib "MW原理图库") (part "uln2803")))
    (comp (ref "UDLDG26") (value "uln2803") (footprint "sol-18") (libsource (lib "MW原理图库") (part "uln2803")))
    (comp (ref "UDLDG27") (value "uln2803") (footprint "sol-18") (libsource (lib "MW原理图库") (part "uln2803")))
    (comp (ref "UDLDG28") (value "uln2803") (footprint "sol-18") (libsource (lib "MW原理图库") (part "uln2803")))
    (comp (ref "UDLDG29") (value "uln2803") (footprint "sol-18") (libsource (lib "MW原理图库") (part "uln2803")))
    (comp (ref "UDLDG30") (value "uln2803") (footprint "sol-18") (libsource (lib "MW原理图库") (part "uln2803")))
    (comp (ref "USB_1")
      (value "USB")
      (footprint "USB/SM0.8-6H5")
      (libsource (lib "战舰STM32开发板底板封装库") (part "USB5"))
    )
    (comp (ref "USCQ1")
      (value "74HC573")
      (footprint "SO20_M")
      (description "Octal D-Type Transparent Latch with 3-State Outputs")
      (fields (field (name "PUBLISHER") "Altium Limited"))
      (libsource (lib "TI Logic Latch") (part "SN74HC573DW"))
    )
    (comp (ref "USCQ2")
      (value "74HC573")
      (footprint "SO20_M")
      (description "Octal D-Type Transparent Latch with 3-State Outputs")
      (fields (field (name "PUBLISHER") "Altium Limited"))
      (libsource (lib "TI Logic Latch") (part "SN74HC573DW"))
    )
    (comp (ref "USCQ3")
      (value "74HC573")
      (footprint "SO20_M")
      (description "Octal D-Type Transparent Latch with 3-State Outputs")
      (fields (field (name "PUBLISHER") "Altium Limited"))
      (libsource (lib "TI Logic Latch") (part "SN74HC573DW"))
    )
    (comp (ref "USCQ4")
      (value "74HC573")
      (footprint "SO20_M")
      (description "Octal D-Type Transparent Latch with 3-State Outputs")
      (fields (field (name "PUBLISHER") "Altium Limited"))
      (libsource (lib "TI Logic Latch") (part "SN74HC573DW"))
    )
    (comp (ref "USCQ5")
      (value "74HC573")
      (footprint "SO20_M")
      (description "Octal D-Type Transparent Latch with 3-State Outputs")
      (fields (field (name "PUBLISHER") "Altium Limited"))
      (libsource (lib "TI Logic Latch") (part "SN74HC573DW"))
    )
    (comp (ref "USCQ6")
      (value "74HC573")
      (footprint "SO20_M")
      (description "Octal D-Type Transparent Latch with 3-State Outputs")
      (fields (field (name "PUBLISHER") "Altium Limited"))
      (libsource (lib "TI Logic Latch") (part "SN74HC573DW"))
    )
    (comp (ref "USCQ7")
      (value "74HC573")
      (footprint "SO20_M")
      (description "Octal D-Type Transparent Latch with 3-State Outputs")
      (fields (field (name "PUBLISHER") "Altium Limited"))
      (libsource (lib "TI Logic Latch") (part "SN74HC573DW"))
    )
    (comp (ref "USCQ8")
      (value "74HC573")
      (footprint "SO20_M")
      (description "Octal D-Type Transparent Latch with 3-State Outputs")
      (fields (field (name "PUBLISHER") "Altium Limited"))
      (libsource (lib "TI Logic Latch") (part "SN74HC573DW"))
    )
    (comp (ref "USCQ9")
      (value "74HC573")
      (footprint "SO20_M")
      (description "Octal D-Type Transparent Latch with 3-State Outputs")
      (fields (field (name "PUBLISHER") "Altium Limited"))
      (libsource (lib "TI Logic Latch") (part "SN74HC573DW"))
    )
    (comp (ref "USCQ10")
      (value "74HC573")
      (footprint "SO20_M")
      (description "Octal D-Type Transparent Latch with 3-State Outputs")
      (fields (field (name "PUBLISHER") "Altium Limited"))
      (libsource (lib "TI Logic Latch") (part "SN74HC573DW"))
    )
    (comp (ref "USCQ11")
      (value "74HC573")
      (footprint "SO20_M")
      (description "Octal D-Type Transparent Latch with 3-State Outputs")
      (fields (field (name "PUBLISHER") "Altium Limited"))
      (libsource (lib "TI Logic Latch") (part "SN74HC573DW"))
    )
    (comp (ref "USCQ12")
      (value "74HC573")
      (footprint "SO20_M")
      (description "Octal D-Type Transparent Latch with 3-State Outputs")
      (fields (field (name "PUBLISHER") "Altium Limited"))
      (libsource (lib "TI Logic Latch") (part "SN74HC573DW"))
    )
    (comp (ref "USCQ13")
      (value "74HC573")
      (footprint "SO20_M")
      (description "Octal D-Type Transparent Latch with 3-State Outputs")
      (fields (field (name "PUBLISHER") "Altium Limited"))
      (libsource (lib "TI Logic Latch") (part "SN74HC573DW"))
    )
    (comp (ref "USCQ14")
      (value "74HC573")
      (footprint "SO20_M")
      (description "Octal D-Type Transparent Latch with 3-State Outputs")
      (fields (field (name "PUBLISHER") "Altium Limited"))
      (libsource (lib "TI Logic Latch") (part "SN74HC573DW"))
    )
    (comp (ref "USCQ15")
      (value "74HC573")
      (footprint "SO20_M")
      (description "Octal D-Type Transparent Latch with 3-State Outputs")
      (fields (field (name "PUBLISHER") "Altium Limited"))
      (libsource (lib "TI Logic Latch") (part "SN74HC573DW"))
    )
    (comp (ref "USCQ16")
      (value "74HC573")
      (footprint "SO20_M")
      (description "Octal D-Type Transparent Latch with 3-State Outputs")
      (fields (field (name "PUBLISHER") "Altium Limited"))
      (libsource (lib "TI Logic Latch") (part "SN74HC573DW"))
    )
    (comp (ref "USCQ17")
      (value "74HC573")
      (footprint "SO20_M")
      (description "Octal D-Type Transparent Latch with 3-State Outputs")
      (fields (field (name "PUBLISHER") "Altium Limited"))
      (libsource (lib "TI Logic Latch") (part "SN74HC573DW"))
    )
    (comp (ref "USCQ18")
      (value "74HC573")
      (footprint "SO20_M")
      (description "Octal D-Type Transparent Latch with 3-State Outputs")
      (fields (field (name "PUBLISHER") "Altium Limited"))
      (libsource (lib "TI Logic Latch") (part "SN74HC573DW"))
    )
    (comp (ref "USCQ19")
      (value "74HC573")
      (footprint "SO20_M")
      (description "Octal D-Type Transparent Latch with 3-State Outputs")
      (fields (field (name "PUBLISHER") "Altium Limited"))
      (libsource (lib "TI Logic Latch") (part "SN74HC573DW"))
    )
    (comp (ref "USCQ20")
      (value "74HC573")
      (footprint "SO20_M")
      (description "Octal D-Type Transparent Latch with 3-State Outputs")
      (fields (field (name "PUBLISHER") "Altium Limited"))
      (libsource (lib "TI Logic Latch") (part "SN74HC573DW"))
    )
    (comp (ref "USCQ21")
      (value "74HC573")
      (footprint "SO20_M")
      (description "Octal D-Type Transparent Latch with 3-State Outputs")
      (fields (field (name "PUBLISHER") "Altium Limited"))
      (libsource (lib "TI Logic Latch") (part "SN74HC573DW"))
    )
    (comp (ref "USCQ22")
      (value "74HC573")
      (footprint "SO20_M")
      (description "Octal D-Type Transparent Latch with 3-State Outputs")
      (fields (field (name "PUBLISHER") "Altium Limited"))
      (libsource (lib "TI Logic Latch") (part "SN74HC573DW"))
    )
    (comp (ref "USCQ23")
      (value "74HC573")
      (footprint "SO20_M")
      (description "Octal D-Type Transparent Latch with 3-State Outputs")
      (fields (field (name "PUBLISHER") "Altium Limited"))
      (libsource (lib "TI Logic Latch") (part "SN74HC573DW"))
    )
    (comp (ref "USCQ24")
      (value "74HC573")
      (footprint "SO20_M")
      (description "Octal D-Type Transparent Latch with 3-State Outputs")
      (fields (field (name "PUBLISHER") "Altium Limited"))
      (libsource (lib "TI Logic Latch") (part "SN74HC573DW"))
    )
    (comp (ref "USCQ25")
      (value "74HC573")
      (footprint "SO20_M")
      (description "Octal D-Type Transparent Latch with 3-State Outputs")
      (fields (field (name "PUBLISHER") "Altium Limited"))
      (libsource (lib "TI Logic Latch") (part "SN74HC573DW"))
    )
    (comp (ref "USCQ26")
      (value "74HC573")
      (footprint "SO20_M")
      (description "Octal D-Type Transparent Latch with 3-State Outputs")
      (fields (field (name "PUBLISHER") "Altium Limited"))
      (libsource (lib "TI Logic Latch") (part "SN74HC573DW"))
    )
    (comp (ref "USCQ27")
      (value "74HC573")
      (footprint "SO20_M")
      (description "Octal D-Type Transparent Latch with 3-State Outputs")
      (fields (field (name "PUBLISHER") "Altium Limited"))
      (libsource (lib "TI Logic Latch") (part "SN74HC573DW"))
    )
    (comp (ref "USCQ28")
      (value "74HC573")
      (footprint "SO20_M")
      (description "Octal D-Type Transparent Latch with 3-State Outputs")
      (fields (field (name "PUBLISHER") "Altium Limited"))
      (libsource (lib "TI Logic Latch") (part "SN74HC573DW"))
    )
    (comp (ref "USCQ29")
      (value "74HC573")
      (footprint "SO20_M")
      (description "Octal D-Type Transparent Latch with 3-State Outputs")
      (fields (field (name "PUBLISHER") "Altium Limited"))
      (libsource (lib "TI Logic Latch") (part "SN74HC573DW"))
    )
    (comp (ref "USCQ30")
      (value "74HC573")
      (footprint "SO20_M")
      (description "Octal D-Type Transparent Latch with 3-State Outputs")
      (fields (field (name "PUBLISHER") "Altium Limited"))
      (libsource (lib "TI Logic Latch") (part "SN74HC573DW"))
    )
    (comp (ref "WK1") (value "Header 3") (footprint "CON-3-2.5") (libsource (lib "*") (part "HEADER 3")))
    (comp (ref "X1")
      (value "XTAL_SM")
      (footprint "X5032-1")
      (description "Crystal")
      (libsource (lib "*") (part "XTAL_SM"))
    )
    (comp (ref "Y1")
      (value "32768hz")
      (footprint "XTAL-3215")
      (description "Crystal Oscillator")
      (fields (field (name "PUBLISHER") "Altium Limited"))
      (libsource (lib "*") (part "XTAL"))
    )
    (comp (ref "Y2") (value "32.768KHZ") (footprint "XTAL-3215") (libsource (lib "*") (part "CRYSTAL2")))
    (comp (ref "Y3")
      (value "12M")
      (footprint "XTAL_US")
      (description "晶振")
      (libsource (lib "*") (part "XTAL1"))
    )
    (comp (ref "Y4")
      (value "12.288MHz")
      (footprint "XTAL_US")
      (description "Crystal Oscillator")
      (fields (field (name "PUBLISHER") "Altium Limited"))
      (libsource (lib "战舰STM32开发板底板封装库") (part "XTAL_2"))
    )
  )
  (nets
    (net (code "1") (name "/12MI") (class "Default")
      (node (ref "C43") (pin "2") (pinfunction "2_2") (pintype "passive"))
      (node (ref "R29") (pin "1") (pintype "passive"))
      (node (ref "U4") (pin "26") (pinfunction "XTALI_26") (pintype "passive"))
      (node (ref "Y3") (pin "1") (pinfunction "1_1") (pintype "passive"))
    )
    (net (code "2") (name "/12MO") (class "Default")
      (node (ref "C44") (pin "2") (pinfunction "2_2") (pintype "passive"))
      (node (ref "R29") (pin "2") (pintype "passive"))
      (node (ref "U4") (pin "27") (pinfunction "XTALO_27") (pintype "passive"))
      (node (ref "Y3") (pin "2") (pinfunction "2_2") (pintype "passive"))
    )
    (net (code "3") (name "/A3") (class "Default")
      (node (ref "R31") (pin "2") (pinfunction "2_2") (pintype "passive"))
      (node (ref "U4") (pin "62") (pinfunction "A3_62") (pintype "passive"))
    )
    (net (code "4") (name "/A4") (class "Default")
      (node (ref "R25") (pin "2") (pinfunction "2_2") (pintype "passive"))
      (node (ref "U4") (pin "29") (pinfunction "A4_29") (pintype "passive"))
    )
    (net (code "6") (name "/ADAC0") (class "Default")
      (node (ref "C31") (pin "1") (pinfunction "1_1") (pintype "passive"))
      (node (ref "R19") (pin "1") (pinfunction "1_1") (pintype "passive"))
    )
    (net (code "7") (name "/ADIN1") (class "Default")
      (node (ref "U5") (pin "43") (pinfunction "PA0/WKUP/UART4_TX/ETH_MII_CRS/ADC123_IN0_43") (pintype "passive"))
    )
    (net (code "8") (name "/ADIN2") (class "Default")
      (node (ref "U5") (pin "55") (pinfunction "PA6/TIM1_BKIN/TIM3_CH1/TIM8_BKIN/SPI1_MISO/_TIM13_CH1__DCMI_PIXCLK/LCD_G2_55") (pintype "passive"))
    )
    (net (code "9") (name "/ADIN3") (class "Default")
      (node (ref "U5") (pin "56") (pinfunction "PA7/TIM1_CH1N/_TIM3_CH2/_TIM8_CH1N/_SPI1_MOSI/__TIM14_CH1/_ETH_MII_RX_DV/ETH_R__MII_CRS_DV_56") (pintype "passive"))
    )
    (net (code "10") (name "/ADIN4") (class "Default")
      (node (ref "U5") (pin "36") (pinfunction "PC1/ETH_MDC_36") (pintype "passive"))
    )
    (net (code "11") (name "/ADIN5") (class "Default")
      (node (ref "U5") (pin "57") (pinfunction "PC4/ETH_MII_RXD0/ETH_RM__II_RXD0_57") (pintype "passive"))
    )
    (net (code "12") (name "/ADIN6") (class "Default")
      (node (ref "U5") (pin "58") (pinfunction "PC5/ETH_MII_RXD1/ETH_RM__II_RXD1_58") (pintype "passive"))
    )
    (net (code "13") (name "/AVDD12") (class "Default")
      (node (ref "C25") (pin "1") (pinfunction "1_1") (pintype "passive"))
      (node (ref "U4") (pin "24") (pinfunction "AVDD12_24") (pintype "passive"))
    )
    (net (code "14") (name "/AVDD33") (class "Default")
      (node (ref "C23") (pin "1") (pinfunction "1_1") (pintype "passive"))
      (node (ref "C24") (pin "2") (pinfunction "2_2") (pintype "passive"))
      (node (ref "C30") (pin "2") (pinfunction "2_2") (pintype "passive"))
      (node (ref "FB2") (pin "1") (pinfunction "1_1") (pintype "passive"))
      (node (ref "U4") (pin "17") (pinfunction "AVCC_17") (pintype "passive"))
      (node (ref "U4") (pin "2") (pinfunction "UVCC_2") (pintype "passive"))
      (node (ref "U4") (pin "7") (pinfunction "AVCC_7") (pintype "passive"))
    )
    (net (code "15") (name "/BAUD1") (class "Default")
      (node (ref "R23") (pin "2") (pintype "passive"))
      (node (ref "R27") (pin "2") (pintype "passive"))
      (node (ref "U4") (pin "56") (pinfunction "BAUD1_56") (pintype "passive"))
    )
    (net (code "16") (name "/BAUD2") (class "Default")
      (node (ref "R28") (pin "2") (pintype "passive"))
      (node (ref "R30") (pin "1") (pintype "passive"))
      (node (ref "U4") (pin "55") (pinfunction "BAUD2_55") (pintype "passive"))
    )
    (net (code "17") (name "/BOOT0") (class "Default")
      (node (ref "R3") (pin "2") (pintype "passive"))
      (node (ref "R38") (pin "2") (pintype "passive"))
      (node (ref "R42") (pin "1") (pintype "passive"))
      (node (ref "U5") (pin "197") (pinfunction "BOOT0_197") (pintype "passive"))
    )
    (net (code "18") (name "/BOOT1") (class "Default")
      (node (ref "R4") (pin "2") (pintype "passive"))
      (node (ref "R43") (pin "2") (pintype "passive"))
      (node (ref "U5") (pin "63") (pinfunction "PB2/BOOT1_63") (pintype "passive"))
    )
    (net (code "19") (name "/BT_VCC") (class "Default")
      (node (ref "*R3") (pin "1") (pintype "passive"))
      (node (ref "C48") (pin "2") (pinfunction "2_2") (pintype "passive"))
      (node (ref "D59") (pin "3") (pinfunction "3_3") (pintype "passive"))
      (node (ref "DS1") (pin "8") (pinfunction "VCC1_8") (pintype "passive"))
    )
    (net (code "20") (name "/BUZZER") (class "Default")
      (node (ref "U5") (pin "193") (pinfunction "PB4/NJTRST/TIM3_CH1/SPI1_MISO/SPI3_MISO/I2S3ext_SD_193") (pintype "passive"))
    )
    (net (code "22") (name "/CH340 D+") (class "Default")
      (node (ref "U9") (pin "5") (pinfunction "D+_5") (pintype "passive"))
      (node (ref "USB_1") (pin "3") (pinfunction "D+_3") (pintype "passive"))
    )
    (net (code "23") (name "/CH340 D-") (class "Default")
      (node (ref "U9") (pin "6") (pinfunction "D-_6") (pintype "passive"))
      (node (ref "USB_1") (pin "2") (pinfunction "D-_2") (pintype "passive"))
    )
    (net (code "24") (name "/CH_PD") (class "Default")
      (node (ref "U5") (pin "7") (pinfunction "PI8_7") (pintype "passive"))
    )
    (net (code "25") (name "/D0") (class "Default")
      (node (ref "U4") (pin "16") (pinfunction "F_D0_16") (pintype "passive"))
      (node (ref "U4") (pin "57") (pinfunction "M_D0_57") (pintype "passive"))
    )
    (net (code "26") (name "/D1") (class "Default")
      (node (ref "U4") (pin "21") (pinfunction "F_D1_21") (pintype "passive"))
      (node (ref "U4") (pin "60") (pinfunction "M_D1_60") (pintype "passive"))
    )
    (net (code "27") (name "/D2") (class "Default")
      (node (ref "U4") (pin "49") (pinfunction "M_D2_49") (pintype "passive"))
      (node (ref "U4") (pin "50") (pinfunction "F_D2_50") (pintype "passive"))
    )
    (net (code "28") (name "/D3") (class "Default")
      (node (ref "U4") (pin "51") (pinfunction "F_D3_51") (pintype "passive"))
      (node (ref "U4") (pin "59") (pinfunction "M_D3_59") (pintype "passive"))
    )
    (net (code "29") (name "/DAC1") (class "Default")
      (node (ref "U5") (pin "53") (pinfunction "PA4/SPI1_NSS/SPI3_NSS/I2S3_WS/_USART2_CK/_OTG_HS_SOF/_DCMI_HSYNC/_LCD_VSYNC_53") (pintype "passive"))
    )
    (net (code "30") (name "/DAC2") (class "Default")
      (node (ref "U5") (pin "54") (pinfunction "PA5/TIM2_CH1/TIM2_ETR/TIM8_CH1N/SPI1_SCK/OTG_HS_ULPI_CK_54") (pintype "passive"))
    )
    (net (code "33") (name "/DOT1") (class "Default")
      (node (ref "T1") (pin "1") (pinfunction "P1_1") (pintype "passive"))
      (node (ref "UDLDG1") (pin "18") (pinfunction "OT1_18") (pintype "passive"))
    )
    (net (code "34") (name "/DOT2") (class "Default")
      (node (ref "T1") (pin "21") (pinfunction "P21_21") (pintype "passive"))
      (node (ref "UDLDG1") (pin "17") (pinfunction "OT2_17") (pintype "passive"))
    )
    (net (code "35") (name "/DOT3") (class "Default")
      (node (ref "T1") (pin "2") (pinfunction "P2_2") (pintype "passive"))
      (node (ref "UDLDG1") (pin "16") (pinfunction "OT3_16") (pintype "passive"))
    )
    (net (code "36") (name "/DOT4") (class "Default")
      (node (ref "T1") (pin "22") (pinfunction "P22_22") (pintype "passive"))
      (node (ref "UDLDG1") (pin "15") (pinfunction "OT4_15") (pintype "passive"))
    )
    (net (code "37") (name "/DOT5") (class "Default")
      (node (ref "T1") (pin "3") (pinfunction "P3_3") (pintype "passive"))
      (node (ref "UDLDG1") (pin "14") (pinfunction "OT5_14") (pintype "passive"))
    )
    (net (code "38") (name "/DOT6") (class "Default")
      (node (ref "T1") (pin "23") (pinfunction "P23_23") (pintype "passive"))
      (node (ref "UDLDG1") (pin "13") (pinfunction "OT6_13") (pintype "passive"))
    )
    (net (code "39") (name "/DOT7") (class "Default")
      (node (ref "T1") (pin "4") (pinfunction "P4_4") (pintype "passive"))
      (node (ref "UDLDG1") (pin "12") (pinfunction "OT7_12") (pintype "passive"))
    )
    (net (code "40") (name "/DOT8") (class "Default")
      (node (ref "T1") (pin "24") (pinfunction "P24_24") (pintype "passive"))
      (node (ref "UDLDG1") (pin "11") (pinfunction "OT8_11") (pintype "passive"))
    )
    (net (code "41") (name "/DOT9") (class "Default")
      (node (ref "T1") (pin "5") (pinfunction "P5_5") (pintype "passive"))
      (node (ref "UDLDG2") (pin "18") (pinfunction "OT1_18") (pintype "passive"))
    )
    (net (code "42") (name "/DOT10") (class "Default")
      (node (ref "T1") (pin "25") (pinfunction "P25_25") (pintype "passive"))
      (node (ref "UDLDG2") (pin "17") (pinfunction "OT2_17") (pintype "passive"))
    )
    (net (code "43") (name "/DOT11") (class "Default")
      (node (ref "T1") (pin "6") (pinfunction "P6_6") (pintype "passive"))
      (node (ref "UDLDG2") (pin "16") (pinfunction "OT3_16") (pintype "passive"))
    )
    (net (code "44") (name "/DOT12") (class "Default")
      (node (ref "T1") (pin "26") (pinfunction "P26_26") (pintype "passive"))
      (node (ref "UDLDG2") (pin "15") (pinfunction "OT4_15") (pintype "passive"))
    )
    (net (code "45") (name "/DOT13") (class "Default")
      (node (ref "T1") (pin "7") (pinfunction "P7_7") (pintype "passive"))
      (node (ref "UDLDG2") (pin "14") (pinfunction "OT5_14") (pintype "passive"))
    )
    (net (code "46") (name "/DOT14") (class "Default")
      (node (ref "T1") (pin "27") (pinfunction "P27_27") (pintype "passive"))
      (node (ref "UDLDG2") (pin "13") (pinfunction "OT6_13") (pintype "passive"))
    )
    (net (code "47") (name "/DOT15") (class "Default")
      (node (ref "T1") (pin "8") (pinfunction "P8_8") (pintype "passive"))
      (node (ref "UDLDG2") (pin "12") (pinfunction "OT7_12") (pintype "passive"))
    )
    (net (code "48") (name "/DOT16") (class "Default")
      (node (ref "T1") (pin "28") (pinfunction "P28_28") (pintype "passive"))
      (node (ref "UDLDG2") (pin "11") (pinfunction "OT8_11") (pintype "passive"))
    )
    (net (code "49") (name "/DOT17") (class "Default")
      (node (ref "T1") (pin "9") (pinfunction "P9_9") (pintype "passive"))
      (node (ref "UDLDG3") (pin "18") (pinfunction "OT1_18") (pintype "passive"))
    )
    (net (code "50") (name "/DOT18") (class "Default")
      (node (ref "T1") (pin "29") (pinfunction "P29_29") (pintype "passive"))
      (node (ref "UDLDG3") (pin "17") (pinfunction "OT2_17") (pintype "passive"))
    )
    (net (code "51") (name "/DOT19") (class "Default")
      (node (ref "T1") (pin "10") (pinfunction "P10_10") (pintype "passive"))
      (node (ref "UDLDG3") (pin "16") (pinfunction "OT3_16") (pintype "passive"))
    )
    (net (code "52") (name "/DOT20") (class "Default")
      (node (ref "T1") (pin "30") (pinfunction "P30_30") (pintype "passive"))
      (node (ref "UDLDG3") (pin "15") (pinfunction "OT4_15") (pintype "passive"))
    )
    (net (code "53") (name "/DOT21") (class "Default")
      (node (ref "T1") (pin "11") (pinfunction "P11_11") (pintype "passive"))
      (node (ref "UDLDG3") (pin "14") (pinfunction "OT5_14") (pintype "passive"))
    )
    (net (code "54") (name "/DOT22") (class "Default")
      (node (ref "T1") (pin "31") (pinfunction "P31_31") (pintype "passive"))
      (node (ref "UDLDG3") (pin "13") (pinfunction "OT6_13") (pintype "passive"))
    )
    (net (code "55") (name "/DOT23") (class "Default")
      (node (ref "T1") (pin "12") (pinfunction "P12_12") (pintype "passive"))
      (node (ref "UDLDG3") (pin "12") (pinfunction "OT7_12") (pintype "passive"))
    )
    (net (code "56") (name "/DOT24") (class "Default")
      (node (ref "T1") (pin "32") (pinfunction "P32_32") (pintype "passive"))
      (node (ref "UDLDG3") (pin "11") (pinfunction "OT8_11") (pintype "passive"))
    )
    (net (code "57") (name "/DOT25") (class "Default")
      (node (ref "T1") (pin "13") (pinfunction "P13_13") (pintype "passive"))
      (node (ref "UDLDG4") (pin "18") (pinfunction "OT1_18") (pintype "passive"))
    )
    (net (code "58") (name "/DOT26") (class "Default")
      (node (ref "T1") (pin "33") (pinfunction "P33_33") (pintype "passive"))
      (node (ref "UDLDG4") (pin "17") (pinfunction "OT2_17") (pintype "passive"))
    )
    (net (code "59") (name "/DOT27") (class "Default")
      (node (ref "T1") (pin "14") (pinfunction "P14_14") (pintype "passive"))
      (node (ref "UDLDG4") (pin "16") (pinfunction "OT3_16") (pintype "passive"))
    )
    (net (code "60") (name "/DOT28") (class "Default")
      (node (ref "T1") (pin "34") (pinfunction "P34_34") (pintype "passive"))
      (node (ref "UDLDG4") (pin "15") (pinfunction "OT4_15") (pintype "passive"))
    )
    (net (code "61") (name "/DOT29") (class "Default")
      (node (ref "T1") (pin "15") (pinfunction "P15_15") (pintype "passive"))
      (node (ref "UDLDG4") (pin "14") (pinfunction "OT5_14") (pintype "passive"))
    )
    (net (code "62") (name "/DOT30") (class "Default")
      (node (ref "T1") (pin "35") (pinfunction "P35_35") (pintype "passive"))
      (node (ref "UDLDG4") (pin "13") (pinfunction "OT6_13") (pintype "passive"))
    )
    (net (code "63") (name "/DOT31") (class "Default")
      (node (ref "T1") (pin "16") (pinfunction "P16_16") (pintype "passive"))
      (node (ref "UDLDG4") (pin "12") (pinfunction "OT7_12") (pintype "passive"))
    )
    (net (code "64") (name "/DOT32") (class "Default")
      (node (ref "T1") (pin "36") (pinfunction "P36_36") (pintype "passive"))
      (node (ref "UDLDG4") (pin "11") (pinfunction "OT8_11") (pintype "passive"))
    )
    (net (code "65") (name "/DOT33") (class "Default")
      (node (ref "T1") (pin "17") (pinfunction "P17_17") (pintype "passive"))
      (node (ref "UDLDG5") (pin "18") (pinfunction "OT1_18") (pintype "passive"))
    )
    (net (code "66") (name "/DOT34") (class "Default")
      (node (ref "T1") (pin "37") (pinfunction "P37_37") (pintype "passive"))
      (node (ref "UDLDG5") (pin "17") (pinfunction "OT2_17") (pintype "passive"))
    )
    (net (code "67") (name "/DOT35") (class "Default")
      (node (ref "T1") (pin "18") (pinfunction "P18_18") (pintype "passive"))
      (node (ref "UDLDG5") (pin "16") (pinfunction "OT3_16") (pintype "passive"))
    )
    (net (code "68") (name "/DOT36") (class "Default")
      (node (ref "T1") (pin "38") (pinfunction "P38_38") (pintype "passive"))
      (node (ref "UDLDG5") (pin "15") (pinfunction "OT4_15") (pintype "passive"))
    )
    (net (code "69") (name "/DOT37") (class "Default")
      (node (ref "T1") (pin "19") (pinfunction "P19_19") (pintype "passive"))
      (node (ref "UDLDG5") (pin "14") (pinfunction "OT5_14") (pintype "passive"))
    )
    (net (code "70") (name "/DOT38") (class "Default")
      (node (ref "T1") (pin "39") (pinfunction "P39_39") (pintype "passive"))
      (node (ref "UDLDG5") (pin "13") (pinfunction "OT6_13") (pintype "passive"))
    )
    (net (code "71") (name "/DOT39") (class "Default")
      (node (ref "T1") (pin "20") (pinfunction "P20_20") (pintype "passive"))
      (node (ref "UDLDG5") (pin "12") (pinfunction "OT7_12") (pintype "passive"))
    )
    (net (code "72") (name "/DOT40") (class "Default")
      (node (ref "T1") (pin "40") (pinfunction "P40_40") (pintype "passive"))
      (node (ref "UDLDG5") (pin "11") (pinfunction "OT8_11") (pintype "passive"))
    )
    (net (code "73") (name "/DOT41") (class "Default")
      (node (ref "T2") (pin "1") (pinfunction "P1_1") (pintype "passive"))
      (node (ref "UDLDG6") (pin "18") (pinfunction "OT1_18") (pintype "passive"))
    )
    (net (code "74") (name "/DOT42") (class "Default")
      (node (ref "T2") (pin "21") (pinfunction "P21_21") (pintype "passive"))
      (node (ref "UDLDG6") (pin "17") (pinfunction "OT2_17") (pintype "passive"))
    )
    (net (code "75") (name "/DOT43") (class "Default")
      (node (ref "T2") (pin "2") (pinfunction "P2_2") (pintype "passive"))
      (node (ref "UDLDG6") (pin "16") (pinfunction "OT3_16") (pintype "passive"))
    )
    (net (code "76") (name "/DOT44") (class "Default")
      (node (ref "T2") (pin "22") (pinfunction "P22_22") (pintype "passive"))
      (node (ref "UDLDG6") (pin "15") (pinfunction "OT4_15") (pintype "passive"))
    )
    (net (code "77") (name "/DOT45") (class "Default")
      (node (ref "T2") (pin "3") (pinfunction "P3_3") (pintype "passive"))
      (node (ref "UDLDG6") (pin "14") (pinfunction "OT5_14") (pintype "passive"))
    )
    (net (code "78") (name "/DOT46") (class "Default")
      (node (ref "T2") (pin "23") (pinfunction "P23_23") (pintype "passive"))
      (node (ref "UDLDG6") (pin "13") (pinfunction "OT6_13") (pintype "passive"))
    )
    (net (code "79") (name "/DOT47") (class "Default")
      (node (ref "T2") (pin "4") (pinfunction "P4_4") (pintype "passive"))
      (node (ref "UDLDG6") (pin "12") (pinfunction "OT7_12") (pintype "passive"))
    )
    (net (code "80") (name "/DOT48") (class "Default")
      (node (ref "T2") (pin "24") (pinfunction "P24_24") (pintype "passive"))
      (node (ref "UDLDG6") (pin "11") (pinfunction "OT8_11") (pintype "passive"))
    )
    (net (code "81") (name "/DOT49") (class "Default")
      (node (ref "T2") (pin "5") (pinfunction "P5_5") (pintype "passive"))
      (node (ref "UDLDG7") (pin "18") (pinfunction "OT1_18") (pintype "passive"))
    )
    (net (code "82") (name "/DOT50") (class "Default")
      (node (ref "T2") (pin "25") (pinfunction "P25_25") (pintype "passive"))
      (node (ref "UDLDG7") (pin "17") (pinfunction "OT2_17") (pintype "passive"))
    )
    (net (code "83") (name "/DOT51") (class "Default")
      (node (ref "T2") (pin "6") (pinfunction "P6_6") (pintype "passive"))
      (node (ref "UDLDG7") (pin "16") (pinfunction "OT3_16") (pintype "passive"))
    )
    (net (code "84") (name "/DOT52") (class "Default")
      (node (ref "T2") (pin "26") (pinfunction "P26_26") (pintype "passive"))
      (node (ref "UDLDG7") (pin "15") (pinfunction "OT4_15") (pintype "passive"))
    )
    (net (code "85") (name "/DOT53") (class "Default")
      (node (ref "T2") (pin "7") (pinfunction "P7_7") (pintype "passive"))
      (node (ref "UDLDG7") (pin "14") (pinfunction "OT5_14") (pintype "passive"))
    )
    (net (code "86") (name "/DOT54") (class "Default")
      (node (ref "T2") (pin "27") (pinfunction "P27_27") (pintype "passive"))
      (node (ref "UDLDG7") (pin "13") (pinfunction "OT6_13") (pintype "passive"))
    )
    (net (code "87") (name "/DOT55") (class "Default")
      (node (ref "T2") (pin "8") (pinfunction "P8_8") (pintype "passive"))
      (node (ref "UDLDG7") (pin "12") (pinfunction "OT7_12") (pintype "passive"))
    )
    (net (code "88") (name "/DOT56") (class "Default")
      (node (ref "T2") (pin "28") (pinfunction "P28_28") (pintype "passive"))
      (node (ref "UDLDG7") (pin "11") (pinfunction "OT8_11") (pintype "passive"))
    )
    (net (code "89") (name "/DOT57") (class "Default")
      (node (ref "T2") (pin "9") (pinfunction "P9_9") (pintype "passive"))
      (node (ref "UDLDG8") (pin "18") (pinfunction "OT1_18") (pintype "passive"))
    )
    (net (code "90") (name "/DOT58") (class "Default")
      (node (ref "T2") (pin "29") (pinfunction "P29_29") (pintype "passive"))
      (node (ref "UDLDG8") (pin "17") (pinfunction "OT2_17") (pintype "passive"))
    )
    (net (code "91") (name "/DOT59") (class "Default")
      (node (ref "T2") (pin "10") (pinfunction "P10_10") (pintype "passive"))
      (node (ref "UDLDG8") (pin "16") (pinfunction "OT3_16") (pintype "passive"))
    )
    (net (code "92") (name "/DOT60") (class "Default")
      (node (ref "T2") (pin "30") (pinfunction "P30_30") (pintype "passive"))
      (node (ref "UDLDG8") (pin "15") (pinfunction "OT4_15") (pintype "passive"))
    )
    (net (code "93") (name "/DOT61") (class "Default")
      (node (ref "T2") (pin "11") (pinfunction "P11_11") (pintype "passive"))
      (node (ref "UDLDG8") (pin "14") (pinfunction "OT5_14") (pintype "passive"))
    )
    (net (code "94") (name "/DOT62") (class "Default")
      (node (ref "T2") (pin "31") (pinfunction "P31_31") (pintype "passive"))
      (node (ref "UDLDG8") (pin "13") (pinfunction "OT6_13") (pintype "passive"))
    )
    (net (code "95") (name "/DOT63") (class "Default")
      (node (ref "T2") (pin "12") (pinfunction "P12_12") (pintype "passive"))
      (node (ref "UDLDG8") (pin "12") (pinfunction "OT7_12") (pintype "passive"))
    )
    (net (code "96") (name "/DOT64") (class "Default")
      (node (ref "T2") (pin "32") (pinfunction "P32_32") (pintype "passive"))
      (node (ref "UDLDG8") (pin "11") (pinfunction "OT8_11") (pintype "passive"))
    )
    (net (code "97") (name "/DOT65") (class "Default")
      (node (ref "T2") (pin "13") (pinfunction "P13_13") (pintype "passive"))
      (node (ref "UDLDG9") (pin "18") (pinfunction "OT1_18") (pintype "passive"))
    )
    (net (code "98") (name "/DOT66") (class "Default")
      (node (ref "T2") (pin "33") (pinfunction "P33_33") (pintype "passive"))
      (node (ref "UDLDG9") (pin "17") (pinfunction "OT2_17") (pintype "passive"))
    )
    (net (code "99") (name "/DOT67") (class "Default")
      (node (ref "T2") (pin "14") (pinfunction "P14_14") (pintype "passive"))
      (node (ref "UDLDG9") (pin "16") (pinfunction "OT3_16") (pintype "passive"))
    )
    (net (code "100") (name "/DOT68") (class "Default")
      (node (ref "T2") (pin "34") (pinfunction "P34_34") (pintype "passive"))
      (node (ref "UDLDG9") (pin "15") (pinfunction "OT4_15") (pintype "passive"))
    )
    (net (code "101") (name "/DOT69") (class "Default")
      (node (ref "T2") (pin "15") (pinfunction "P15_15") (pintype "passive"))
      (node (ref "UDLDG9") (pin "14") (pinfunction "OT5_14") (pintype "passive"))
    )
    (net (code "102") (name "/DOT70") (class "Default")
      (node (ref "T2") (pin "35") (pinfunction "P35_35") (pintype "passive"))
      (node (ref "UDLDG9") (pin "13") (pinfunction "OT6_13") (pintype "passive"))
    )
    (net (code "103") (name "/DOT71") (class "Default")
      (node (ref "T2") (pin "16") (pinfunction "P16_16") (pintype "passive"))
      (node (ref "UDLDG9") (pin "12") (pinfunction "OT7_12") (pintype "passive"))
    )
    (net (code "104") (name "/DOT72") (class "Default")
      (node (ref "T2") (pin "36") (pinfunction "P36_36") (pintype "passive"))
      (node (ref "UDLDG9") (pin "11") (pinfunction "OT8_11") (pintype "passive"))
    )
    (net (code "105") (name "/DOT73") (class "Default")
      (node (ref "T2") (pin "17") (pinfunction "P17_17") (pintype "passive"))
      (node (ref "UDLDG10") (pin "18") (pinfunction "OT1_18") (pintype "passive"))
    )
    (net (code "106") (name "/DOT74") (class "Default")
      (node (ref "T2") (pin "37") (pinfunction "P37_37") (pintype "passive"))
      (node (ref "UDLDG10") (pin "17") (pinfunction "OT2_17") (pintype "passive"))
    )
    (net (code "107") (name "/DOT75") (class "Default")
      (node (ref "T2") (pin "18") (pinfunction "P18_18") (pintype "passive"))
      (node (ref "UDLDG10") (pin "16") (pinfunction "OT3_16") (pintype "passive"))
    )
    (net (code "108") (name "/DOT76") (class "Default")
      (node (ref "T2") (pin "38") (pinfunction "P38_38") (pintype "passive"))
      (node (ref "UDLDG10") (pin "15") (pinfunction "OT4_15") (pintype "passive"))
    )
    (net (code "109") (name "/DOT77") (class "Default")
      (node (ref "T2") (pin "19") (pinfunction "P19_19") (pintype "passive"))
      (node (ref "UDLDG10") (pin "14") (pinfunction "OT5_14") (pintype "passive"))
    )
    (net (code "110") (name "/DOT78") (class "Default")
      (node (ref "T2") (pin "39") (pinfunction "P39_39") (pintype "passive"))
      (node (ref "UDLDG10") (pin "13") (pinfunction "OT6_13") (pintype "passive"))
    )
    (net (code "111") (name "/DOT79") (class "Default")
      (node (ref "T2") (pin "20") (pinfunction "P20_20") (pintype "passive"))
      (node (ref "UDLDG10") (pin "12") (pinfunction "OT7_12") (pintype "passive"))
    )
    (net (code "112") (name "/DOT80") (class "Default")
      (node (ref "T2") (pin "40") (pinfunction "P40_40") (pintype "passive"))
      (node (ref "UDLDG10") (pin "11") (pinfunction "OT8_11") (pintype "passive"))
    )
    (net (code "113") (name "/DOT81") (class "Default")
      (node (ref "T3") (pin "1") (pinfunction "P1_1") (pintype "passive"))
      (node (ref "UDLDG11") (pin "18") (pinfunction "OT1_18") (pintype "passive"))
    )
    (net (code "114") (name "/DOT82") (class "Default")
      (node (ref "T3") (pin "21") (pinfunction "P21_21") (pintype "passive"))
      (node (ref "UDLDG11") (pin "17") (pinfunction "OT2_17") (pintype "passive"))
    )
    (net (code "115") (name "/DOT83") (class "Default")
      (node (ref "T3") (pin "2") (pinfunction "P2_2") (pintype "passive"))
      (node (ref "UDLDG11") (pin "16") (pinfunction "OT3_16") (pintype "passive"))
    )
    (net (code "116") (name "/DOT84") (class "Default")
      (node (ref "T3") (pin "22") (pinfunction "P22_22") (pintype "passive"))
      (node (ref "UDLDG11") (pin "15") (pinfunction "OT4_15") (pintype "passive"))
    )
    (net (code "117") (name "/DOT85") (class "Default")
      (node (ref "T3") (pin "3") (pinfunction "P3_3") (pintype "passive"))
      (node (ref "UDLDG11") (pin "14") (pinfunction "OT5_14") (pintype "passive"))
    )
    (net (code "118") (name "/DOT86") (class "Default")
      (node (ref "T3") (pin "23") (pinfunction "P23_23") (pintype "passive"))
      (node (ref "UDLDG11") (pin "13") (pinfunction "OT6_13") (pintype "passive"))
    )
    (net (code "119") (name "/DOT87") (class "Default")
      (node (ref "T3") (pin "4") (pinfunction "P4_4") (pintype "passive"))
      (node (ref "UDLDG11") (pin "12") (pinfunction "OT7_12") (pintype "passive"))
    )
    (net (code "120") (name "/DOT88") (class "Default")
      (node (ref "T3") (pin "24") (pinfunction "P24_24") (pintype "passive"))
      (node (ref "UDLDG11") (pin "11") (pinfunction "OT8_11") (pintype "passive"))
    )
    (net (code "121") (name "/DOT89") (class "Default")
      (node (ref "T3") (pin "5") (pinfunction "P5_5") (pintype "passive"))
      (node (ref "UDLDG12") (pin "18") (pinfunction "OT1_18") (pintype "passive"))
    )
    (net (code "122") (name "/DOT90") (class "Default")
      (node (ref "T3") (pin "25") (pinfunction "P25_25") (pintype "passive"))
      (node (ref "UDLDG12") (pin "17") (pinfunction "OT2_17") (pintype "passive"))
    )
    (net (code "123") (name "/DOT91") (class "Default")
      (node (ref "T3") (pin "6") (pinfunction "P6_6") (pintype "passive"))
      (node (ref "UDLDG12") (pin "16") (pinfunction "OT3_16") (pintype "passive"))
    )
    (net (code "124") (name "/DOT92") (class "Default")
      (node (ref "T3") (pin "26") (pinfunction "P26_26") (pintype "passive"))
      (node (ref "UDLDG12") (pin "15") (pinfunction "OT4_15") (pintype "passive"))
    )
    (net (code "125") (name "/DOT93") (class "Default")
      (node (ref "T3") (pin "7") (pinfunction "P7_7") (pintype "passive"))
      (node (ref "UDLDG12") (pin "14") (pinfunction "OT5_14") (pintype "passive"))
    )
    (net (code "126") (name "/DOT94") (class "Default")
      (node (ref "T3") (pin "27") (pinfunction "P27_27") (pintype "passive"))
      (node (ref "UDLDG12") (pin "13") (pinfunction "OT6_13") (pintype "passive"))
    )
    (net (code "127") (name "/DOT95") (class "Default")
      (node (ref "T3") (pin "8") (pinfunction "P8_8") (pintype "passive"))
      (node (ref "UDLDG12") (pin "12") (pinfunction "OT7_12") (pintype "passive"))
    )
    (net (code "128") (name "/DOT96") (class "Default")
      (node (ref "T3") (pin "28") (pinfunction "P28_28") (pintype "passive"))
      (node (ref "UDLDG12") (pin "11") (pinfunction "OT8_11") (pintype "passive"))
    )
    (net (code "129") (name "/DOT97") (class "Default")
      (node (ref "T3") (pin "9") (pinfunction "P9_9") (pintype "passive"))
      (node (ref "UDLDG13") (pin "18") (pinfunction "OT1_18") (pintype "passive"))
    )
    (net (code "130") (name "/DOT98") (class "Default")
      (node (ref "T3") (pin "29") (pinfunction "P29_29") (pintype "passive"))
      (node (ref "UDLDG13") (pin "17") (pinfunction "OT2_17") (pintype "passive"))
    )
    (net (code "131") (name "/DOT99") (class "Default")
      (node (ref "T3") (pin "10") (pinfunction "P10_10") (pintype "passive"))
      (node (ref "UDLDG13") (pin "16") (pinfunction "OT3_16") (pintype "passive"))
    )
    (net (code "132") (name "/DOT100") (class "Default")
      (node (ref "T3") (pin "30") (pinfunction "P30_30") (pintype "passive"))
      (node (ref "UDLDG13") (pin "15") (pinfunction "OT4_15") (pintype "passive"))
    )
    (net (code "133") (name "/DOT101") (class "Default")
      (node (ref "T3") (pin "11") (pinfunction "P11_11") (pintype "passive"))
      (node (ref "UDLDG13") (pin "14") (pinfunction "OT5_14") (pintype "passive"))
    )
    (net (code "134") (name "/DOT102") (class "Default")
      (node (ref "T3") (pin "31") (pinfunction "P31_31") (pintype "passive"))
      (node (ref "UDLDG13") (pin "13") (pinfunction "OT6_13") (pintype "passive"))
    )
    (net (code "135") (name "/DOT103") (class "Default")
      (node (ref "T3") (pin "12") (pinfunction "P12_12") (pintype "passive"))
      (node (ref "UDLDG13") (pin "12") (pinfunction "OT7_12") (pintype "passive"))
    )
    (net (code "136") (name "/DOT104") (class "Default")
      (node (ref "T3") (pin "32") (pinfunction "P32_32") (pintype "passive"))
      (node (ref "UDLDG13") (pin "11") (pinfunction "OT8_11") (pintype "passive"))
    )
    (net (code "137") (name "/DOT105") (class "Default")
      (node (ref "T3") (pin "13") (pinfunction "P13_13") (pintype "passive"))
      (node (ref "UDLDG14") (pin "18") (pinfunction "OT1_18") (pintype "passive"))
    )
    (net (code "138") (name "/DOT106") (class "Default")
      (node (ref "T3") (pin "33") (pinfunction "P33_33") (pintype "passive"))
      (node (ref "UDLDG14") (pin "17") (pinfunction "OT2_17") (pintype "passive"))
    )
    (net (code "139") (name "/DOT107") (class "Default")
      (node (ref "T3") (pin "14") (pinfunction "P14_14") (pintype "passive"))
      (node (ref "UDLDG14") (pin "16") (pinfunction "OT3_16") (pintype "passive"))
    )
    (net (code "140") (name "/DOT108") (class "Default")
      (node (ref "T3") (pin "34") (pinfunction "P34_34") (pintype "passive"))
      (node (ref "UDLDG14") (pin "15") (pinfunction "OT4_15") (pintype "passive"))
    )
    (net (code "141") (name "/DOT109") (class "Default")
      (node (ref "T3") (pin "15") (pinfunction "P15_15") (pintype "passive"))
      (node (ref "UDLDG14") (pin "14") (pinfunction "OT5_14") (pintype "passive"))
    )
    (net (code "142") (name "/DOT110") (class "Default")
      (node (ref "T3") (pin "35") (pinfunction "P35_35") (pintype "passive"))
      (node (ref "UDLDG14") (pin "13") (pinfunction "OT6_13") (pintype "passive"))
    )
    (net (code "143") (name "/DOT111") (class "Default")
      (node (ref "T3") (pin "16") (pinfunction "P16_16") (pintype "passive"))
      (node (ref "UDLDG14") (pin "12") (pinfunction "OT7_12") (pintype "passive"))
    )
    (net (code "144") (name "/DOT112") (class "Default")
      (node (ref "T3") (pin "36") (pinfunction "P36_36") (pintype "passive"))
      (node (ref "UDLDG14") (pin "11") (pinfunction "OT8_11") (pintype "passive"))
    )
    (net (code "145") (name "/DOT113") (class "Default")
      (node (ref "T3") (pin "17") (pinfunction "P17_17") (pintype "passive"))
      (node (ref "UDLDG15") (pin "18") (pinfunction "OT1_18") (pintype "passive"))
    )
    (net (code "146") (name "/DOT114") (class "Default")
      (node (ref "T3") (pin "37") (pinfunction "P37_37") (pintype "passive"))
      (node (ref "UDLDG15") (pin "17") (pinfunction "OT2_17") (pintype "passive"))
    )
    (net (code "147") (name "/DOT115") (class "Default")
      (node (ref "T3") (pin "18") (pinfunction "P18_18") (pintype "passive"))
      (node (ref "UDLDG15") (pin "16") (pinfunction "OT3_16") (pintype "passive"))
    )
    (net (code "148") (name "/DOT116") (class "Default")
      (node (ref "T3") (pin "38") (pinfunction "P38_38") (pintype "passive"))
      (node (ref "UDLDG15") (pin "15") (pinfunction "OT4_15") (pintype "passive"))
    )
    (net (code "149") (name "/DOT117") (class "Default")
      (node (ref "T3") (pin "19") (pinfunction "P19_19") (pintype "passive"))
      (node (ref "UDLDG15") (pin "14") (pinfunction "OT5_14") (pintype "passive"))
    )
    (net (code "150") (name "/DOT118") (class "Default")
      (node (ref "T3") (pin "39") (pinfunction "P39_39") (pintype "passive"))
      (node (ref "UDLDG15") (pin "13") (pinfunction "OT6_13") (pintype "passive"))
    )
    (net (code "151") (name "/DOT119") (class "Default")
      (node (ref "T3") (pin "20") (pinfunction "P20_20") (pintype "passive"))
      (node (ref "UDLDG15") (pin "12") (pinfunction "OT7_12") (pintype "passive"))
    )
    (net (code "152") (name "/DOT120") (class "Default")
      (node (ref "T3") (pin "40") (pinfunction "P40_40") (pintype "passive"))
      (node (ref "UDLDG15") (pin "11") (pinfunction "OT8_11") (pintype "passive"))
    )
    (net (code "153") (name "/DOT121") (class "Default")
      (node (ref "T4") (pin "1") (pinfunction "P1_1") (pintype "passive"))
      (node (ref "UDLDG16") (pin "18") (pinfunction "OT1_18") (pintype "passive"))
    )
    (net (code "154") (name "/DOT122") (class "Default")
      (node (ref "T4") (pin "21") (pinfunction "P21_21") (pintype "passive"))
      (node (ref "UDLDG16") (pin "17") (pinfunction "OT2_17") (pintype "passive"))
    )
    (net (code "155") (name "/DOT123") (class "Default")
      (node (ref "T4") (pin "2") (pinfunction "P2_2") (pintype "passive"))
      (node (ref "UDLDG16") (pin "16") (pinfunction "OT3_16") (pintype "passive"))
    )
    (net (code "156") (name "/DOT124") (class "Default")
      (node (ref "T4") (pin "22") (pinfunction "P22_22") (pintype "passive"))
      (node (ref "UDLDG16") (pin "15") (pinfunction "OT4_15") (pintype "passive"))
    )
    (net (code "157") (name "/DOT125") (class "Default")
      (node (ref "T4") (pin "3") (pinfunction "P3_3") (pintype "passive"))
      (node (ref "UDLDG16") (pin "14") (pinfunction "OT5_14") (pintype "passive"))
    )
    (net (code "158") (name "/DOT126") (class "Default")
      (node (ref "T4") (pin "23") (pinfunction "P23_23") (pintype "passive"))
      (node (ref "UDLDG16") (pin "13") (pinfunction "OT6_13") (pintype "passive"))
    )
    (net (code "159") (name "/DOT127") (class "Default")
      (node (ref "T4") (pin "4") (pinfunction "P4_4") (pintype "passive"))
      (node (ref "UDLDG16") (pin "12") (pinfunction "OT7_12") (pintype "passive"))
    )
    (net (code "160") (name "/DOT128") (class "Default")
      (node (ref "T4") (pin "24") (pinfunction "P24_24") (pintype "passive"))
      (node (ref "UDLDG16") (pin "11") (pinfunction "OT8_11") (pintype "passive"))
    )
    (net (code "161") (name "/DOT129") (class "Default")
      (node (ref "T4") (pin "5") (pinfunction "P5_5") (pintype "passive"))
      (node (ref "UDLDG17") (pin "18") (pinfunction "OT1_18") (pintype "passive"))
    )
    (net (code "162") (name "/DOT130") (class "Default")
      (node (ref "T4") (pin "25") (pinfunction "P25_25") (pintype "passive"))
      (node (ref "UDLDG17") (pin "17") (pinfunction "OT2_17") (pintype "passive"))
    )
    (net (code "163") (name "/DOT131") (class "Default")
      (node (ref "T4") (pin "6") (pinfunction "P6_6") (pintype "passive"))
      (node (ref "UDLDG17") (pin "16") (pinfunction "OT3_16") (pintype "passive"))
    )
    (net (code "164") (name "/DOT132") (class "Default")
      (node (ref "T4") (pin "26") (pinfunction "P26_26") (pintype "passive"))
      (node (ref "UDLDG17") (pin "15") (pinfunction "OT4_15") (pintype "passive"))
    )
    (net (code "165") (name "/DOT133") (class "Default")
      (node (ref "T4") (pin "7") (pinfunction "P7_7") (pintype "passive"))
      (node (ref "UDLDG17") (pin "14") (pinfunction "OT5_14") (pintype "passive"))
    )
    (net (code "166") (name "/DOT134") (class "Default")
      (node (ref "T4") (pin "27") (pinfunction "P27_27") (pintype "passive"))
      (node (ref "UDLDG17") (pin "13") (pinfunction "OT6_13") (pintype "passive"))
    )
    (net (code "167") (name "/DOT135") (class "Default")
      (node (ref "T4") (pin "8") (pinfunction "P8_8") (pintype "passive"))
      (node (ref "UDLDG17") (pin "12") (pinfunction "OT7_12") (pintype "passive"))
    )
    (net (code "168") (name "/DOT136") (class "Default")
      (node (ref "T4") (pin "28") (pinfunction "P28_28") (pintype "passive"))
      (node (ref "UDLDG17") (pin "11") (pinfunction "OT8_11") (pintype "passive"))
    )
    (net (code "169") (name "/DOT137") (class "Default")
      (node (ref "T4") (pin "9") (pinfunction "P9_9") (pintype "passive"))
      (node (ref "UDLDG18") (pin "18") (pinfunction "OT1_18") (pintype "passive"))
    )
    (net (code "170") (name "/DOT138") (class "Default")
      (node (ref "T4") (pin "29") (pinfunction "P29_29") (pintype "passive"))
      (node (ref "UDLDG18") (pin "17") (pinfunction "OT2_17") (pintype "passive"))
    )
    (net (code "171") (name "/DOT139") (class "Default")
      (node (ref "T4") (pin "10") (pinfunction "P10_10") (pintype "passive"))
      (node (ref "UDLDG18") (pin "16") (pinfunction "OT3_16") (pintype "passive"))
    )
    (net (code "172") (name "/DOT140") (class "Default")
      (node (ref "T4") (pin "30") (pinfunction "P30_30") (pintype "passive"))
      (node (ref "UDLDG18") (pin "15") (pinfunction "OT4_15") (pintype "passive"))
    )
    (net (code "173") (name "/DOT141") (class "Default")
      (node (ref "T4") (pin "11") (pinfunction "P11_11") (pintype "passive"))
      (node (ref "UDLDG18") (pin "14") (pinfunction "OT5_14") (pintype "passive"))
    )
    (net (code "174") (name "/DOT142") (class "Default")
      (node (ref "T4") (pin "31") (pinfunction "P31_31") (pintype "passive"))
      (node (ref "UDLDG18") (pin "13") (pinfunction "OT6_13") (pintype "passive"))
    )
    (net (code "175") (name "/DOT143") (class "Default")
      (node (ref "T4") (pin "12") (pinfunction "P12_12") (pintype "passive"))
      (node (ref "UDLDG18") (pin "12") (pinfunction "OT7_12") (pintype "passive"))
    )
    (net (code "176") (name "/DOT144") (class "Default")
      (node (ref "T4") (pin "32") (pinfunction "P32_32") (pintype "passive"))
      (node (ref "UDLDG18") (pin "11") (pinfunction "OT8_11") (pintype "passive"))
    )
    (net (code "177") (name "/DOT145") (class "Default")
      (node (ref "T4") (pin "13") (pinfunction "P13_13") (pintype "passive"))
      (node (ref "UDLDG19") (pin "18") (pinfunction "OT1_18") (pintype "passive"))
    )
    (net (code "178") (name "/DOT146") (class "Default")
      (node (ref "T4") (pin "33") (pinfunction "P33_33") (pintype "passive"))
      (node (ref "UDLDG19") (pin "17") (pinfunction "OT2_17") (pintype "passive"))
    )
    (net (code "179") (name "/DOT147") (class "Default")
      (node (ref "T4") (pin "14") (pinfunction "P14_14") (pintype "passive"))
      (node (ref "UDLDG19") (pin "16") (pinfunction "OT3_16") (pintype "passive"))
    )
    (net (code "180") (name "/DOT148") (class "Default")
      (node (ref "T4") (pin "34") (pinfunction "P34_34") (pintype "passive"))
      (node (ref "UDLDG19") (pin "15") (pinfunction "OT4_15") (pintype "passive"))
    )
    (net (code "181") (name "/DOT149") (class "Default")
      (node (ref "T4") (pin "15") (pinfunction "P15_15") (pintype "passive"))
      (node (ref "UDLDG19") (pin "14") (pinfunction "OT5_14") (pintype "passive"))
    )
    (net (code "182") (name "/DOT150") (class "Default")
      (node (ref "T4") (pin "35") (pinfunction "P35_35") (pintype "passive"))
      (node (ref "UDLDG19") (pin "13") (pinfunction "OT6_13") (pintype "passive"))
    )
    (net (code "183") (name "/DOT151") (class "Default")
      (node (ref "T4") (pin "16") (pinfunction "P16_16") (pintype "passive"))
      (node (ref "UDLDG19") (pin "12") (pinfunction "OT7_12") (pintype "passive"))
    )
    (net (code "184") (name "/DOT152") (class "Default")
      (node (ref "T4") (pin "36") (pinfunction "P36_36") (pintype "passive"))
      (node (ref "UDLDG19") (pin "11") (pinfunction "OT8_11") (pintype "passive"))
    )
    (net (code "185") (name "/DOT153") (class "Default")
      (node (ref "T4") (pin "17") (pinfunction "P17_17") (pintype "passive"))
      (node (ref "UDLDG20") (pin "18") (pinfunction "OT1_18") (pintype "passive"))
    )
    (net (code "186") (name "/DOT154") (class "Default")
      (node (ref "T4") (pin "37") (pinfunction "P37_37") (pintype "passive"))
      (node (ref "UDLDG20") (pin "17") (pinfunction "OT2_17") (pintype "passive"))
    )
    (net (code "187") (name "/DOT155") (class "Default")
      (node (ref "T4") (pin "18") (pinfunction "P18_18") (pintype "passive"))
      (node (ref "UDLDG20") (pin "16") (pinfunction "OT3_16") (pintype "passive"))
    )
    (net (code "188") (name "/DOT156") (class "Default")
      (node (ref "T4") (pin "38") (pinfunction "P38_38") (pintype "passive"))
      (node (ref "UDLDG20") (pin "15") (pinfunction "OT4_15") (pintype "passive"))
    )
    (net (code "189") (name "/DOT157") (class "Default")
      (node (ref "T4") (pin "19") (pinfunction "P19_19") (pintype "passive"))
      (node (ref "UDLDG20") (pin "14") (pinfunction "OT5_14") (pintype "passive"))
    )
    (net (code "190") (name "/DOT158") (class "Default")
      (node (ref "T4") (pin "39") (pinfunction "P39_39") (pintype "passive"))
      (node (ref "UDLDG20") (pin "13") (pinfunction "OT6_13") (pintype "passive"))
    )
    (net (code "191") (name "/DOT159") (class "Default")
      (node (ref "T4") (pin "20") (pinfunction "P20_20") (pintype "passive"))
      (node (ref "UDLDG20") (pin "12") (pinfunction "OT7_12") (pintype "passive"))
    )
    (net (code "192") (name "/DOT160") (class "Default")
      (node (ref "T4") (pin "40") (pinfunction "P40_40") (pintype "passive"))
      (node (ref "UDLDG20") (pin "11") (pinfunction "OT8_11") (pintype "passive"))
    )
    (net (code "193") (name "/DOT161") (class "Default")
      (node (ref "T5") (pin "1") (pinfunction "P1_1") (pintype "passive"))
      (node (ref "UDLDG21") (pin "18") (pinfunction "OT1_18") (pintype "passive"))
    )
    (net (code "194") (name "/DOT162") (class "Default")
      (node (ref "T5") (pin "21") (pinfunction "P21_21") (pintype "passive"))
      (node (ref "UDLDG21") (pin "17") (pinfunction "OT2_17") (pintype "passive"))
    )
    (net (code "195") (name "/DOT163") (class "Default")
      (node (ref "T5") (pin "2") (pinfunction "P2_2") (pintype "passive"))
      (node (ref "UDLDG21") (pin "16") (pinfunction "OT3_16") (pintype "passive"))
    )
    (net (code "196") (name "/DOT164") (class "Default")
      (node (ref "T5") (pin "22") (pinfunction "P22_22") (pintype "passive"))
      (node (ref "UDLDG21") (pin "15") (pinfunction "OT4_15") (pintype "passive"))
    )
    (net (code "197") (name "/DOT165") (class "Default")
      (node (ref "T5") (pin "3") (pinfunction "P3_3") (pintype "passive"))
      (node (ref "UDLDG21") (pin "14") (pinfunction "OT5_14") (pintype "passive"))
    )
    (net (code "198") (name "/DOT166") (class "Default")
      (node (ref "T5") (pin "23") (pinfunction "P23_23") (pintype "passive"))
      (node (ref "UDLDG21") (pin "13") (pinfunction "OT6_13") (pintype "passive"))
    )
    (net (code "199") (name "/DOT167") (class "Default")
      (node (ref "T5") (pin "4") (pinfunction "P4_4") (pintype "passive"))
      (node (ref "UDLDG21") (pin "12") (pinfunction "OT7_12") (pintype "passive"))
    )
    (net (code "200") (name "/DOT168") (class "Default")
      (node (ref "T5") (pin "24") (pinfunction "P24_24") (pintype "passive"))
      (node (ref "UDLDG21") (pin "11") (pinfunction "OT8_11") (pintype "passive"))
    )
    (net (code "201") (name "/DOT169") (class "Default")
      (node (ref "T5") (pin "5") (pinfunction "P5_5") (pintype "passive"))
      (node (ref "UDLDG22") (pin "18") (pinfunction "OT1_18") (pintype "passive"))
    )
    (net (code "202") (name "/DOT170") (class "Default")
      (node (ref "T5") (pin "25") (pinfunction "P25_25") (pintype "passive"))
      (node (ref "UDLDG22") (pin "17") (pinfunction "OT2_17") (pintype "passive"))
    )
    (net (code "203") (name "/DOT171") (class "Default")
      (node (ref "T5") (pin "6") (pinfunction "P6_6") (pintype "passive"))
      (node (ref "UDLDG22") (pin "16") (pinfunction "OT3_16") (pintype "passive"))
    )
    (net (code "204") (name "/DOT172") (class "Default")
      (node (ref "T5") (pin "26") (pinfunction "P26_26") (pintype "passive"))
      (node (ref "UDLDG22") (pin "15") (pinfunction "OT4_15") (pintype "passive"))
    )
    (net (code "205") (name "/DOT173") (class "Default")
      (node (ref "T5") (pin "7") (pinfunction "P7_7") (pintype "passive"))
      (node (ref "UDLDG22") (pin "14") (pinfunction "OT5_14") (pintype "passive"))
    )
    (net (code "206") (name "/DOT174") (class "Default")
      (node (ref "T5") (pin "27") (pinfunction "P27_27") (pintype "passive"))
      (node (ref "UDLDG22") (pin "13") (pinfunction "OT6_13") (pintype "passive"))
    )
    (net (code "207") (name "/DOT175") (class "Default")
      (node (ref "T5") (pin "8") (pinfunction "P8_8") (pintype "passive"))
      (node (ref "UDLDG22") (pin "12") (pinfunction "OT7_12") (pintype "passive"))
    )
    (net (code "208") (name "/DOT176") (class "Default")
      (node (ref "T5") (pin "28") (pinfunction "P28_28") (pintype "passive"))
      (node (ref "UDLDG22") (pin "11") (pinfunction "OT8_11") (pintype "passive"))
    )
    (net (code "209") (name "/DOT177") (class "Default")
      (node (ref "T5") (pin "9") (pinfunction "P9_9") (pintype "passive"))
      (node (ref "UDLDG23") (pin "18") (pinfunction "OT1_18") (pintype "passive"))
    )
    (net (code "210") (name "/DOT178") (class "Default")
      (node (ref "T5") (pin "29") (pinfunction "P29_29") (pintype "passive"))
      (node (ref "UDLDG23") (pin "17") (pinfunction "OT2_17") (pintype "passive"))
    )
    (net (code "211") (name "/DOT179") (class "Default")
      (node (ref "T5") (pin "10") (pinfunction "P10_10") (pintype "passive"))
      (node (ref "UDLDG23") (pin "16") (pinfunction "OT3_16") (pintype "passive"))
    )
    (net (code "212") (name "/DOT180") (class "Default")
      (node (ref "T5") (pin "30") (pinfunction "P30_30") (pintype "passive"))
      (node (ref "UDLDG23") (pin "15") (pinfunction "OT4_15") (pintype "passive"))
    )
    (net (code "213") (name "/DOT181") (class "Default")
      (node (ref "T5") (pin "11") (pinfunction "P11_11") (pintype "passive"))
      (node (ref "UDLDG23") (pin "14") (pinfunction "OT5_14") (pintype "passive"))
    )
    (net (code "214") (name "/DOT182") (class "Default")
      (node (ref "T5") (pin "31") (pinfunction "P31_31") (pintype "passive"))
      (node (ref "UDLDG23") (pin "13") (pinfunction "OT6_13") (pintype "passive"))
    )
    (net (code "215") (name "/DOT183") (class "Default")
      (node (ref "T5") (pin "12") (pinfunction "P12_12") (pintype "passive"))
      (node (ref "UDLDG23") (pin "12") (pinfunction "OT7_12") (pintype "passive"))
    )
    (net (code "216") (name "/DOT184") (class "Default")
      (node (ref "T5") (pin "32") (pinfunction "P32_32") (pintype "passive"))
      (node (ref "UDLDG23") (pin "11") (pinfunction "OT8_11") (pintype "passive"))
    )
    (net (code "217") (name "/DOT185") (class "Default")
      (node (ref "T5") (pin "13") (pinfunction "P13_13") (pintype "passive"))
      (node (ref "UDLDG24") (pin "18") (pinfunction "OT1_18") (pintype "passive"))
    )
    (net (code "218") (name "/DOT186") (class "Default")
      (node (ref "T5") (pin "33") (pinfunction "P33_33") (pintype "passive"))
      (node (ref "UDLDG24") (pin "17") (pinfunction "OT2_17") (pintype "passive"))
    )
    (net (code "219") (name "/DOT187") (class "Default")
      (node (ref "T5") (pin "14") (pinfunction "P14_14") (pintype "passive"))
      (node (ref "UDLDG24") (pin "16") (pinfunction "OT3_16") (pintype "passive"))
    )
    (net (code "220") (name "/DOT188") (class "Default")
      (node (ref "T5") (pin "34") (pinfunction "P34_34") (pintype "passive"))
      (node (ref "UDLDG24") (pin "15") (pinfunction "OT4_15") (pintype "passive"))
    )
    (net (code "221") (name "/DOT189") (class "Default")
      (node (ref "T5") (pin "15") (pinfunction "P15_15") (pintype "passive"))
      (node (ref "UDLDG24") (pin "14") (pinfunction "OT5_14") (pintype "passive"))
    )
    (net (code "222") (name "/DOT190") (class "Default")
      (node (ref "T5") (pin "35") (pinfunction "P35_35") (pintype "passive"))
      (node (ref "UDLDG24") (pin "13") (pinfunction "OT6_13") (pintype "passive"))
    )
    (net (code "223") (name "/DOT191") (class "Default")
      (node (ref "T5") (pin "16") (pinfunction "P16_16") (pintype "passive"))
      (node (ref "UDLDG24") (pin "12") (pinfunction "OT7_12") (pintype "passive"))
    )
    (net (code "224") (name "/DOT192") (class "Default")
      (node (ref "T5") (pin "36") (pinfunction "P36_36") (pintype "passive"))
      (node (ref "UDLDG24") (pin "11") (pinfunction "OT8_11") (pintype "passive"))
    )
    (net (code "225") (name "/DOT193") (class "Default")
      (node (ref "T5") (pin "17") (pinfunction "P17_17") (pintype "passive"))
      (node (ref "UDLDG25") (pin "18") (pinfunction "OT1_18") (pintype "passive"))
    )
    (net (code "226") (name "/DOT194") (class "Default")
      (node (ref "T5") (pin "37") (pinfunction "P37_37") (pintype "passive"))
      (node (ref "UDLDG25") (pin "17") (pinfunction "OT2_17") (pintype "passive"))
    )
    (net (code "227") (name "/DOT195") (class "Default")
      (node (ref "T5") (pin "18") (pinfunction "P18_18") (pintype "passive"))
      (node (ref "UDLDG25") (pin "16") (pinfunction "OT3_16") (pintype "passive"))
    )
    (net (code "228") (name "/DOT196") (class "Default")
      (node (ref "T5") (pin "38") (pinfunction "P38_38") (pintype "passive"))
      (node (ref "UDLDG25") (pin "15") (pinfunction "OT4_15") (pintype "passive"))
    )
    (net (code "229") (name "/DOT197") (class "Default")
      (node (ref "T5") (pin "19") (pinfunction "P19_19") (pintype "passive"))
      (node (ref "UDLDG25") (pin "14") (pinfunction "OT5_14") (pintype "passive"))
    )
    (net (code "230") (name "/DOT198") (class "Default")
      (node (ref "T5") (pin "39") (pinfunction "P39_39") (pintype "passive"))
      (node (ref "UDLDG25") (pin "13") (pinfunction "OT6_13") (pintype "passive"))
    )
    (net (code "231") (name "/DOT199") (class "Default")
      (node (ref "T5") (pin "20") (pinfunction "P20_20") (pintype "passive"))
      (node (ref "UDLDG25") (pin "12") (pinfunction "OT7_12") (pintype "passive"))
    )
    (net (code "232") (name "/DOT200") (class "Default")
      (node (ref "T5") (pin "40") (pinfunction "P40_40") (pintype "passive"))
      (node (ref "UDLDG25") (pin "11") (pinfunction "OT8_11") (pintype "passive"))
    )
    (net (code "233") (name "/DOT201") (class "Default")
      (node (ref "T6") (pin "1") (pinfunction "P1_1") (pintype "passive"))
      (node (ref "UDLDG26") (pin "18") (pinfunction "OT1_18") (pintype "passive"))
    )
    (net (code "234") (name "/DOT202") (class "Default")
      (node (ref "T6") (pin "21") (pinfunction "P21_21") (pintype "passive"))
      (node (ref "UDLDG26") (pin "17") (pinfunction "OT2_17") (pintype "passive"))
    )
    (net (code "235") (name "/DOT203") (class "Default")
      (node (ref "T6") (pin "2") (pinfunction "P2_2") (pintype "passive"))
      (node (ref "UDLDG26") (pin "16") (pinfunction "OT3_16") (pintype "passive"))
    )
    (net (code "236") (name "/DOT204") (class "Default")
      (node (ref "T6") (pin "22") (pinfunction "P22_22") (pintype "passive"))
      (node (ref "UDLDG26") (pin "15") (pinfunction "OT4_15") (pintype "passive"))
    )
    (net (code "237") (name "/DOT205") (class "Default")
      (node (ref "T6") (pin "3") (pinfunction "P3_3") (pintype "passive"))
      (node (ref "UDLDG26") (pin "14") (pinfunction "OT5_14") (pintype "passive"))
    )
    (net (code "238") (name "/DOT206") (class "Default")
      (node (ref "T6") (pin "23") (pinfunction "P23_23") (pintype "passive"))
      (node (ref "UDLDG26") (pin "13") (pinfunction "OT6_13") (pintype "passive"))
    )
    (net (code "239") (name "/DOT207") (class "Default")
      (node (ref "T6") (pin "4") (pinfunction "P4_4") (pintype "passive"))
      (node (ref "UDLDG26") (pin "12") (pinfunction "OT7_12") (pintype "passive"))
    )
    (net (code "240") (name "/DOT208") (class "Default")
      (node (ref "T6") (pin "24") (pinfunction "P24_24") (pintype "passive"))
      (node (ref "UDLDG26") (pin "11") (pinfunction "OT8_11") (pintype "passive"))
    )
    (net (code "241") (name "/DOT209") (class "Default")
      (node (ref "T6") (pin "5") (pinfunction "P5_5") (pintype "passive"))
      (node (ref "UDLDG27") (pin "18") (pinfunction "OT1_18") (pintype "passive"))
    )
    (net (code "242") (name "/DOT210") (class "Default")
      (node (ref "T6") (pin "25") (pinfunction "P25_25") (pintype "passive"))
      (node (ref "UDLDG27") (pin "17") (pinfunction "OT2_17") (pintype "passive"))
    )
    (net (code "243") (name "/DOT211") (class "Default")
      (node (ref "T6") (pin "6") (pinfunction "P6_6") (pintype "passive"))
      (node (ref "UDLDG27") (pin "16") (pinfunction "OT3_16") (pintype "passive"))
    )
    (net (code "244") (name "/DOT212") (class "Default")
      (node (ref "T6") (pin "26") (pinfunction "P26_26") (pintype "passive"))
      (node (ref "UDLDG27") (pin "15") (pinfunction "OT4_15") (pintype "passive"))
    )
    (net (code "245") (name "/DOT213") (class "Default")
      (node (ref "T6") (pin "7") (pinfunction "P7_7") (pintype "passive"))
      (node (ref "UDLDG27") (pin "14") (pinfunction "OT5_14") (pintype "passive"))
    )
    (net (code "246") (name "/DOT214") (class "Default")
      (node (ref "T6") (pin "27") (pinfunction "P27_27") (pintype "passive"))
      (node (ref "UDLDG27") (pin "13") (pinfunction "OT6_13") (pintype "passive"))
    )
    (net (code "247") (name "/DOT215") (class "Default")
      (node (ref "T6") (pin "8") (pinfunction "P8_8") (pintype "passive"))
      (node (ref "UDLDG27") (pin "12") (pinfunction "OT7_12") (pintype "passive"))
    )
    (net (code "248") (name "/DOT216") (class "Default")
      (node (ref "T6") (pin "28") (pinfunction "P28_28") (pintype "passive"))
      (node (ref "UDLDG27") (pin "11") (pinfunction "OT8_11") (pintype "passive"))
    )
    (net (code "249") (name "/DOT217") (class "Default")
      (node (ref "T6") (pin "9") (pinfunction "P9_9") (pintype "passive"))
      (node (ref "UDLDG28") (pin "18") (pinfunction "OT1_18") (pintype "passive"))
    )
    (net (code "250") (name "/DOT218") (class "Default")
      (node (ref "T6") (pin "29") (pinfunction "P29_29") (pintype "passive"))
      (node (ref "UDLDG28") (pin "17") (pinfunction "OT2_17") (pintype "passive"))
    )
    (net (code "251") (name "/DOT219") (class "Default")
      (node (ref "T6") (pin "10") (pinfunction "P10_10") (pintype "passive"))
      (node (ref "UDLDG28") (pin "16") (pinfunction "OT3_16") (pintype "passive"))
    )
    (net (code "252") (name "/DOT220") (class "Default")
      (node (ref "T6") (pin "30") (pinfunction "P30_30") (pintype "passive"))
      (node (ref "UDLDG28") (pin "15") (pinfunction "OT4_15") (pintype "passive"))
    )
    (net (code "253") (name "/DOT221") (class "Default")
      (node (ref "T6") (pin "11") (pinfunction "P11_11") (pintype "passive"))
      (node (ref "UDLDG28") (pin "14") (pinfunction "OT5_14") (pintype "passive"))
    )
    (net (code "254") (name "/DOT222") (class "Default")
      (node (ref "T6") (pin "31") (pinfunction "P31_31") (pintype "passive"))
      (node (ref "UDLDG28") (pin "13") (pinfunction "OT6_13") (pintype "passive"))
    )
    (net (code "255") (name "/DOT223") (class "Default")
      (node (ref "T6") (pin "12") (pinfunction "P12_12") (pintype "passive"))
      (node (ref "UDLDG28") (pin "12") (pinfunction "OT7_12") (pintype "passive"))
    )
    (net (code "256") (name "/DOT224") (class "Default")
      (node (ref "T6") (pin "32") (pinfunction "P32_32") (pintype "passive"))
      (node (ref "UDLDG28") (pin "11") (pinfunction "OT8_11") (pintype "passive"))
    )
    (net (code "257") (name "/DOT225") (class "Default")
      (node (ref "T6") (pin "13") (pinfunction "P13_13") (pintype "passive"))
      (node (ref "UDLDG29") (pin "18") (pinfunction "OT1_18") (pintype "passive"))
    )
    (net (code "258") (name "/DOT226") (class "Default")
      (node (ref "T6") (pin "33") (pinfunction "P33_33") (pintype "passive"))
      (node (ref "UDLDG29") (pin "17") (pinfunction "OT2_17") (pintype "passive"))
    )
    (net (code "259") (name "/DOT227") (class "Default")
      (node (ref "T6") (pin "14") (pinfunction "P14_14") (pintype "passive"))
      (node (ref "UDLDG29") (pin "16") (pinfunction "OT3_16") (pintype "passive"))
    )
    (net (code "260") (name "/DOT228") (class "Default")
      (node (ref "T6") (pin "34") (pinfunction "P34_34") (pintype "passive"))
      (node (ref "UDLDG29") (pin "15") (pinfunction "OT4_15") (pintype "passive"))
    )
    (net (code "261") (name "/DOT229") (class "Default")
      (node (ref "T6") (pin "15") (pinfunction "P15_15") (pintype "passive"))
      (node (ref "UDLDG29") (pin "14") (pinfunction "OT5_14") (pintype "passive"))
    )
    (net (code "262") (name "/DOT230") (class "Default")
      (node (ref "T6") (pin "35") (pinfunction "P35_35") (pintype "passive"))
      (node (ref "UDLDG29") (pin "13") (pinfunction "OT6_13") (pintype "passive"))
    )
    (net (code "263") (name "/DOT231") (class "Default")
      (node (ref "T6") (pin "16") (pinfunction "P16_16") (pintype "passive"))
      (node (ref "UDLDG29") (pin "12") (pinfunction "OT7_12") (pintype "passive"))
    )
    (net (code "264") (name "/DOT232") (class "Default")
      (node (ref "T6") (pin "36") (pinfunction "P36_36") (pintype "passive"))
      (node (ref "UDLDG29") (pin "11") (pinfunction "OT8_11") (pintype "passive"))
    )
    (net (code "265") (name "/DOT233") (class "Default")
      (node (ref "T6") (pin "17") (pinfunction "P17_17") (pintype "passive"))
      (node (ref "UDLDG30") (pin "18") (pinfunction "OT1_18") (pintype "passive"))
    )
    (net (code "266") (name "/DOT234") (class "Default")
      (node (ref "T6") (pin "37") (pinfunction "P37_37") (pintype "passive"))
      (node (ref "UDLDG30") (pin "17") (pinfunction "OT2_17") (pintype "passive"))
    )
    (net (code "267") (name "/DOT235") (class "Default")
      (node (ref "T6") (pin "18") (pinfunction "P18_18") (pintype "passive"))
      (node (ref "UDLDG30") (pin "16") (pinfunction "OT3_16") (pintype "passive"))
    )
    (net (code "268") (name "/DOT236") (class "Default")
      (node (ref "T6") (pin "38") (pinfunction "P38_38") (pintype "passive"))
      (node (ref "UDLDG30") (pin "15") (pinfunction "OT4_15") (pintype "passive"))
    )
    (net (code "269") (name "/DOT237") (class "Default")
      (node (ref "T6") (pin "19") (pinfunction "P19_19") (pintype "passive"))
      (node (ref "UDLDG30") (pin "14") (pinfunction "OT5_14") (pintype "passive"))
    )
    (net (code "270") (name "/DOT238") (class "Default")
      (node (ref "T6") (pin "39") (pinfunction "P39_39") (pintype "passive"))
      (node (ref "UDLDG30") (pin "13") (pinfunction "OT6_13") (pintype "passive"))
    )
    (net (code "271") (name "/DOT239") (class "Default")
      (node (ref "T6") (pin "20") (pinfunction "P20_20") (pintype "passive"))
      (node (ref "UDLDG30") (pin "12") (pinfunction "OT7_12") (pintype "passive"))
    )
    (net (code "272") (name "/DOT240") (class "Default")
      (node (ref "T6") (pin "40") (pinfunction "P40_40") (pintype "passive"))
      (node (ref "UDLDG30") (pin "11") (pinfunction "OT8_11") (pintype "passive"))
    )
    (net (code "273") (name "/FMC_A0") (class "Default")
      (node (ref "U1") (pin "23") (pinfunction "A0_23") (pintype "input"))
      (node (ref "U5") (pin "16") (pinfunction "PF0/I2C2_SDA/FMC_A0_16") (pintype "passive"))
    )
    (net (code "274") (name "/FMC_A1") (class "Default")
      (node (ref "U1") (pin "24") (pinfunction "A1_24") (pintype "input"))
      (node (ref "U5") (pin "17") (pinfunction "PF1/I2C2_SCL/FMC_A1_17") (pintype "passive"))
    )
    (net (code "275") (name "/FMC_A2") (class "Default")
      (node (ref "U1") (pin "25") (pinfunction "A2_25") (pintype "input"))
      (node (ref "U5") (pin "18") (pinfunction "PF2/I2C2_SMBA/FMC_A2_18") (pintype "passive"))
    )
    (net (code "276") (name "/FMC_A3") (class "Default")
      (node (ref "U1") (pin "26") (pinfunction "A3_26") (pintype "input"))
      (node (ref "U5") (pin "22") (pinfunction "PF3/FMC_A3_22") (pintype "passive"))
    )
    (net (code "277") (name "/FMC_A4") (class "Default")
      (node (ref "U1") (pin "29") (pinfunction "A4_29") (pintype "input"))
      (node (ref "U5") (pin "23") (pinfunction "PF4/FMC_A4_23") (pintype "passive"))
    )
    (net (code "278") (name "/FMC_A5") (class "Default")
      (node (ref "U1") (pin "30") (pinfunction "A5_30") (pintype "input"))
      (node (ref "U5") (pin "24") (pinfunction "PF5/FMC_A5_24") (pintype "passive"))
    )
    (net (code "279") (name "/FMC_A6") (class "Default")
      (node (ref "U1") (pin "31") (pinfunction "A6_31") (pintype "input"))
      (node (ref "U5") (pin "71") (pinfunction "PF12/FMC_A6_71") (pintype "passive"))
    )
    (net (code "280") (name "/FMC_A7") (class "Default")
      (node (ref "U1") (pin "32") (pinfunction "A7_32") (pintype "input"))
      (node (ref "U5") (pin "74") (pinfunction "PF13/FMC_A7_74") (pintype "passive"))
    )
    (net (code "281") (name "/FMC_A8") (class "Default")
      (node (ref "U1") (pin "33") (pinfunction "A8_33") (pintype "input"))
      (node (ref "U5") (pin "75") (pinfunction "PF14/FMC_A8_75") (pintype "passive"))
    )
    (net (code "282") (name "/FMC_A9") (class "Default")
      (node (ref "U1") (pin "34") (pinfunction "A9_34") (pintype "input"))
      (node (ref "U5") (pin "76") (pinfunction "PF15/FMC_A9_76") (pintype "passive"))
    )
    (net (code "283") (name "/FMC_A10") (class "Default")
      (node (ref "U1") (pin "22") (pinfunction "A10_22") (pintype "input"))
      (node (ref "U5") (pin "77") (pinfunction "PG0/FMC_A10_77") (pintype "passive"))
    )
    (net (code "284") (name "/FMC_A11") (class "Default")
      (node (ref "U1") (pin "35") (pinfunction "A11_35") (pintype "input"))
      (node (ref "U5") (pin "78") (pinfunction "PG1/FMC_A11_78") (pintype "passive"))
    )
    (net (code "285") (name "/FMC_A12") (class "Default")
      (node (ref "U1") (pin "36") (pinfunction "A12/NC_36") (pintype "input"))
      (node (ref "U5") (pin "129") (pinfunction "PG2/FMC_A12_129") (pintype "passive"))
    )
    (net (code "286") (name "/FMC_A16_CLE") (class "Default")
      (node (ref "U2") (pin "16") (pinfunction "CLE_16") (pintype "passive"))
      (node (ref "U5") (pin "111") (pinfunction "PD11/USART3_CTS/FMC_A16_111") (pintype "passive"))
    )
    (net (code "287") (name "/FMC_A17_ALE") (class "Default")
      (node (ref "U2") (pin "17") (pinfunction "ALE_17") (pintype "passive"))
      (node (ref "U5") (pin "112") (pinfunction "PD12/TIM4_CH1/USART3_RTS/FMC_A17_112") (pintype "passive"))
    )
    (net (code "289") (name "/FMC_BA0") (class "Default")
      (node (ref "U1") (pin "20") (pinfunction "BA0_20") (pintype "input"))
      (node (ref "U5") (pin "131") (pinfunction "PG4/FMC_A14/FMC_BA0_131") (pintype "passive"))
    )
    (net (code "290") (name "/FMC_BA1") (class "Default")
      (node (ref "U1") (pin "21") (pinfunction "BA1_21") (pintype "bidirectional"))
      (node (ref "U5") (pin "132") (pinfunction "PG5/FMC_A15/FMC_BA1_132") (pintype "passive"))
    )
    (net (code "291") (name "/FMC_D0") (class "Default")
      (node (ref "U1") (pin "2") (pinfunction "DQ0_2") (pintype "bidirectional"))
      (node (ref "U2") (pin "29") (pinfunction "I/O0_29") (pintype "passive"))
      (node (ref "U5") (pin "116") (pinfunction "PD14/TIM4_CH3/FMC_D0_116") (pintype "passive"))
    )
    (net (code "292") (name "/FMC_D1") (class "Default")
      (node (ref "U1") (pin "4") (pinfunction "DQ1_4") (pintype "bidirectional"))
      (node (ref "U2") (pin "30") (pinfunction "I/O1_30") (pintype "passive"))
      (node (ref "U5") (pin "117") (pinfunction "PD15/TIM4_CH4/FMC_D1_117") (pintype "passive"))
    )
    (net (code "293") (name "/FMC_D2") (class "Default")
      (node (ref "U1") (pin "5") (pinfunction "DQ2_5") (pintype "bidirectional"))
      (node (ref "U2") (pin "31") (pinfunction "I/O2_31") (pintype "passive"))
      (node (ref "U5") (pin "164") (pinfunction "PD0/CAN1_RX/FMC_D2_164") (pintype "passive"))
    )
    (net (code "294") (name "/FMC_D3") (class "Default")
      (node (ref "U1") (pin "7") (pinfunction "DQ3_7") (pintype "bidirectional"))
      (node (ref "U2") (pin "32") (pinfunction "I/O3_32") (pintype "passive"))
      (node (ref "U5") (pin "165") (pinfunction "PD1/CAN1_TX/FMC_D3_165") (pintype "passive"))
    )
    (net (code "295") (name "/FMC_D4") (class "Default")
      (node (ref "U1") (pin "8") (pinfunction "DQ4_8") (pintype "bidirectional"))
      (node (ref "U2") (pin "41") (pinfunction "I/O4_41") (pintype "passive"))
      (node (ref "U5") (pin "79") (pinfunction "PE7/TIM1_ETR/_UART7_Rx/_FMC_D4_79") (pintype "passive"))
    )
    (net (code "296") (name "/FMC_D5") (class "Default")
      (node (ref "U1") (pin "10") (pinfunction "DQ5_10") (pintype "bidirectional"))
      (node (ref "U2") (pin "42") (pinfunction "I/O5_42") (pintype "passive"))
      (node (ref "U5") (pin "80") (pinfunction "PE8/TIM1_CH1N/UART7_Tx/FMC_D5_80") (pintype "passive"))
    )
    (net (code "297") (name "/FMC_D6") (class "Default")
      (node (ref "U1") (pin "11") (pinfunction "DQ6_11") (pintype "bidirectional"))
      (node (ref "U2") (pin "43") (pinfunction "I/O6_43") (pintype "passive"))
      (node (ref "U5") (pin "81") (pinfunction "PE9/TIM1_CH1/FMC_D6_81") (pintype "passive"))
    )
    (net (code "298") (name "/FMC_D7") (class "Default")
      (node (ref "U1") (pin "13") (pinfunction "DQ7_13") (pintype "bidirectional"))
      (node (ref "U2") (pin "44") (pinfunction "I/O7_44") (pintype "passive"))
      (node (ref "U5") (pin "84") (pinfunction "PE10/TIM1_CH2N/FMC_D7_84") (pintype "passive"))
    )
    (net (code "299") (name "/FMC_D8") (class "Default")
      (node (ref "U1") (pin "42") (pinfunction "DQ8_42") (pintype "bidirectional"))
      (node (ref "U5") (pin "85") (pinfunction "PE11/TIM1_CH2/SPI4_NSS/FMC_D8/_LCD_G3_85") (pintype "passive"))
    )
    (net (code "300") (name "/FMC_D9") (class "Default")
      (node (ref "U1") (pin "44") (pinfunction "DQ9_44") (pintype "bidirectional"))
      (node (ref "U5") (pin "86") (pinfunction "PE12/TIM1_CH3N/SPI4_SCK/_FMC_D9/_LCD_B4_86") (pintype "passive"))
    )
    (net (code "301") (name "/FMC_D10") (class "Default")
      (node (ref "U1") (pin "45") (pinfunction "DQ10_45") (pintype "bidirectional"))
      (node (ref "U5") (pin "87") (pinfunction "PE13/TIM1_CH3/SPI4_MISO/FMC_D10/_LCD_DE_87") (pintype "passive"))
    )
    (net (code "302") (name "/FMC_D11") (class "Default")
      (node (ref "U1") (pin "47") (pinfunction "DQ11_47") (pintype "bidirectional"))
      (node (ref "U5") (pin "88") (pinfunction "PE14/TIM1_CH4/SPI4_MOSI/FMC_D11/LCD_CLK_88") (pintype "passive"))
    )
    (net (code "303") (name "/FMC_D12") (class "Default")
      (node (ref "U1") (pin "48") (pinfunction "DQ12_48") (pintype "bidirectional"))
      (node (ref "U5") (pin "89") (pinfunction "PE15/TIM1_BKIN/_FMC_D12/__LCD_R7_89") (pintype "passive"))
    )
    (net (code "304") (name "/FMC_D13") (class "Default")
      (node (ref "U1") (pin "50") (pinfunction "DQ13_50") (pintype "bidirectional"))
      (node (ref "U5") (pin "108") (pinfunction "PD8/USART3_TX/FMC_D13_108") (pintype "passive"))
    )
    (net (code "305") (name "/FMC_D14") (class "Default")
      (node (ref "U1") (pin "51") (pinfunction "DQ14_51") (pintype "bidirectional"))
      (node (ref "U5") (pin "109") (pinfunction "PD9/USART3_RX/FMC_D14_109") (pintype "passive"))
    )
    (net (code "306") (name "/FMC_D15") (class "Default")
      (node (ref "U1") (pin "53") (pinfunction "DQ15_53") (pintype "bidirectional"))
      (node (ref "U5") (pin "110") (pinfunction "PD10/USART3_CK/FMC_D15/LCD_B3_110") (pintype "passive"))
    )
    (net (code "307") (name "/FMC_NBL0") (class "Default")
      (node (ref "U1") (pin "15") (pinfunction "LDQM_15") (pintype "input"))
      (node (ref "U5") (pin "200") (pinfunction "PE0/TIM4_ETR/UART8_RX/FMC_NBL0/DCMI_D2_200") (pintype "passive"))
    )
    (net (code "308") (name "/FMC_NBL1") (class "Default")
      (node (ref "U1") (pin "39") (pinfunction "UDQM_39") (pintype "input"))
      (node (ref "U5") (pin "201") (pinfunction "PE1/UART8_Tx/FMC_NBL1/_DCMI_D3_201") (pintype "passive"))
    )
    (net (code "309") (name "/FMC_NCE3") (class "Default")
      (node (ref "R5") (pin "1") (pintype "passive"))
      (node (ref "U2") (pin "9") (pinfunction "~{CE}_9") (pintype "passive"))
      (node (ref "U5") (pin "178") (pinfunction "PG9/USART6_RX/FMC_NE2/FMC_NCE3_178") (pintype "passive"))
    )
    (net (code "311") (name "/FMC_NOE") (class "Default")
      (node (ref "U2") (pin "8") (pinfunction "~{RE}_8") (pintype "passive"))
      (node (ref "U5") (pin "168") (pinfunction "PD4/USART2_RTS/FMC_NOE_168") (pintype "passive"))
    )
    (net (code "312") (name "/FMC_NWAIT") (class "Default")
      (node (ref "U2") (pin "7") (pinfunction "R/~{B}_7") (pintype "passive"))
      (node (ref "U5") (pin "172") (pinfunction "PD6/SPI3_MOSI/I2S3_SD/SAI1_SD_A/USART2_RX/FMC_NWAIT/DCMI_D10/LCD_B2_172") (pintype "passive"))
    )
    (net (code "313") (name "/FMC_NWE") (class "Default")
      (node (ref "U2") (pin "18") (pinfunction "~{WE}_18") (pintype "passive"))
      (node (ref "U5") (pin "169") (pinfunction "PD5/USART2_TX/FMC_NWE_169") (pintype "passive"))
    )
    (net (code "314") (name "/FMC_SDCKE0") (class "Default")
      (node (ref "U1") (pin "37") (pinfunction "CKE_37") (pintype "input"))
      (node (ref "U5") (pin "38") (pinfunction "PC3/SPI2_MOSI/I2S2_SD/OTG_HS_ULPI_NXT/ETH_MII_TX_CLK/FMC_SDCKE0_38") (pintype "passive"))
    )
    (net (code "315") (name "/FMC_SDCLK") (class "Default")
      (node (ref "U1") (pin "38") (pinfunction "CLK_38") (pintype "input"))
      (node (ref "U5") (pin "135") (pinfunction "PG8/SPI6_NSS/_USART6_RTS/__ETH_PPS_OUT/_FMC_SDCLK_135") (pintype "passive"))
    )
    (net (code "316") (name "/FMC_SDNCAS") (class "Default")
      (node (ref "U1") (pin "17") (pinfunction "~{CAS}_17") (pintype "input"))
      (node (ref "U5") (pin "191") (pinfunction "PG15/USART6_CTS/_FMC_SDNCAS_191") (pintype "passive"))
    )
    (net (code "317") (name "/FMC_SDNE0") (class "Default")
      (node (ref "R6") (pin "1") (pintype "passive"))
      (node (ref "U1") (pin "19") (pinfunction "~{CS}_19") (pintype "input"))
      (node (ref "U5") (pin "37") (pinfunction "PC2/SPI2_MISO/I2S2ext_SD/OTG_HS_ULPI_DIR/ETH_MII_TXD2/FMC_SDNE0_37") (pintype "passive"))
    )
    (net (code "318") (name "/FMC_SDNRAS") (class "Default")
      (node (ref "U1") (pin "18") (pinfunction "~{RAS}_18") (pintype "passive"))
      (node (ref "U5") (pin "70") (pinfunction "PF11/SPI5_MOSI/FMC_SDNRAS/DCMI_D12_70") (pintype "passive"))
    )
    (net (code "319") (name "/FMC_SDNWE") (class "Default")
      (node (ref "U1") (pin "16") (pinfunction "~{WE}_16") (pintype "input"))
      (node (ref "U5") (pin "35") (pinfunction "PC0/OTG_HS_ULPI_STP/FMC_SDNWE_35") (pintype "passive"))
    )
    (net (code "320") (name "/F_CS") (class "Default")
      (node (ref "R54") (pin "2") (pintype "passive"))
      (node (ref "U5") (pin "27") (pinfunction "PF6/TIM10_CH1/SPI5_NSS/SAI1_SD_B/UART7_Rx/FMC_NIORD_27") (pintype "passive"))
      (node (ref "U7") (pin "1") (pinfunction "~{CS}_1") (pintype "passive"))
    )
    (net (code "321") (name "/GPIO0") (class "Default")
      (node (ref "U5") (pin "49") (pinfunction "PH5/I2C2_SDA/SPI5_NSS/_FMC_SDNWE_49") (pintype "passive"))
    )
    (net (code "324") (name "/HALL1_IN") (class "Default")
      (node (ref "U5") (pin "8") (pinfunction "PC13_8") (pintype "passive"))
    )
    (net (code "325") (name "/IIC_SCL") (class "Default")
      (node (ref "R55") (pin "2") (pintype "passive"))
      (node (ref "U5") (pin "97") (pinfunction "PH7/I2C3_SCL/_SPI5_MISO/__ETH_MII_RXD3/_FMC_SDCKE1/DCMI_D9_97") (pintype "passive"))
      (node (ref "U8") (pin "6") (pinfunction "SCL_6") (pintype "passive"))
    )
    (net (code "326") (name "/IIC_SCL_2") (class "Default")
      (node (ref "R13") (pin "2") (pinfunction "2_2") (pintype "passive"))
      (node (ref "U4") (pin "47") (pinfunction "IIC_SCL_47") (pintype "passive"))
    )
    (net (code "327") (name "/IIC_SDA") (class "Default")
      (node (ref "R56") (pin "2") (pintype "passive"))
      (node (ref "U5") (pin "98") (pinfunction "PH8/I2C3_SDA/_FMC_D16/_DCMI_HSYNC/_LCD_R2_98") (pintype "passive"))
      (node (ref "U8") (pin "5") (pinfunction "SDA_5") (pintype "passive"))
    )
    (net (code "328") (name "/IIC_SDA_2") (class "Default")
      (node (ref "R15") (pin "2") (pinfunction "2_2") (pintype "passive"))
      (node (ref "U4") (pin "48") (pinfunction "IIC_SDA_48") (pintype "passive"))
    )
    (net (code "341") (name "/JTCK-SWCLK") (class "Default")
      (node (ref "D23") (pin "1") (pinfunction "A_1") (pintype "passive"))
      (node (ref "P1") (pin "4") (pinfunction "4_4") (pintype "passive"))
      (node (ref "U5") (pin "159") (pinfunction "PA14/JTCK-SWCLK_159") (pintype "passive"))
    )
    (net (code "342") (name "/JTMS-SWDIO") (class "Default")
      (node (ref "D22") (pin "1") (pinfunction "A_1") (pintype "passive"))
      (node (ref "P1") (pin "3") (pinfunction "3_3") (pintype "passive"))
      (node (ref "U5") (pin "147") (pinfunction "PA13/JTMS-SWDIO_147") (pintype "passive"))
    )
    (net (code "343") (name "/KEY1") (class "Default")
      (node (ref "K1") (pin "2") (pinfunction "2_2") (pintype "passive"))
      (node (ref "P15") (pin "1") (pinfunction "1_1") (pintype "passive"))
      (node (ref "U5") (pin "2") (pinfunction "PE3/TRACED0/SAI1_SD_B/FMC_A19_2") (pintype "passive"))
    )
    (net (code "344") (name "/KEY2") (class "Default")
      (node (ref "K2") (pin "2") (pinfunction "2_2") (pintype "passive"))
      (node (ref "P16") (pin "1") (pinfunction "1_1") (pintype "passive"))
      (node (ref "U5") (pin "5") (pinfunction "PE6/TRACED3/TIM9_CH2/SPI4_MOSI/SAI1_SD_A/FMC_A22/DCMI_D7/LCD_G1_5") (pintype "passive"))
    )
    (net (code "345") (name "/KEY3") (class "Default")
      (node (ref "K3") (pin "2") (pinfunction "2_2") (pintype "passive"))
      (node (ref "U5") (pin "11") (pinfunction "PI9/CAN1_RX/_FMC_D30/_LCD_VSYNC_11") (pintype "passive"))
    )
    (net (code "346") (name "/KEY4") (class "Default")
      (node (ref "K4") (pin "2") (pinfunction "2_2") (pintype "passive"))
      (node (ref "U5") (pin "3") (pinfunction "PE4/TRACED1/SPI4_NSS/SAI1_FS_A/FMC_A20/DCMI_D4/LCD_B0_3") (pintype "passive"))
    )
    (net (code "347") (name "/KEY5") (class "Default")
      (node (ref "K5") (pin "2") (pinfunction "2_2") (pintype "passive"))
      (node (ref "U5") (pin "4") (pinfunction "PE5/TRACED2/_TIM9_CH1/SPI4_MISO/SAI1_SCK_A/FMC_A21/DCMI_D6/LCD_G0_4") (pintype "passive"))
    )
    (net (code "348") (name "/KEY6") (class "Default")
      (node (ref "K6") (pin "2") (pinfunction "2_2") (pintype "passive"))
      (node (ref "U5") (pin "12") (pinfunction "PI10/ETH_MII_RX_ER/FMC_D31/LCD_HSYNC_12") (pintype "passive"))
    )
    (net (code "349") (name "/KEY7") (class "Default")
      (node (ref "U5") (pin "13") (pinfunction "PI11/OTG_HS_ULPI_DIR_13") (pintype "passive"))
    )
    (net (code "353") (name "/LCD_B3") (class "Default")
      (node (ref "PLCD1") (pin "24") (pinfunction "24_24") (pintype "passive"))
      (node (ref "U5") (pin "177") (pinfunction "PJ15/LCD_B3_177") (pintype "passive"))
    )
    (net (code "354") (name "/LCD_B4") (class "Default")
      (node (ref "PLCD1") (pin "25") (pinfunction "25_25") (pintype "passive"))
      (node (ref "U5") (pin "186") (pinfunction "PK3/LCD_B4_186") (pintype "passive"))
    )
    (net (code "355") (name "/LCD_B5") (class "Default")
      (node (ref "PLCD1") (pin "26") (pinfunction "26_26") (pintype "passive"))
      (node (ref "U5") (pin "187") (pinfunction "PK4/LCD_B5_187") (pintype "passive"))
    )
    (net (code "356") (name "/LCD_B6") (class "Default")
      (node (ref "PLCD1") (pin "27") (pinfunction "27_27") (pintype "passive"))
      (node (ref "U5") (pin "188") (pinfunction "PK5/LCD_B6_188") (pintype "passive"))
    )
    (net (code "357") (name "/LCD_B7") (class "Default")
      (node (ref "PLCD1") (pin "28") (pinfunction "28_28") (pintype "passive"))
      (node (ref "U5") (pin "189") (pinfunction "PK6/LCD_B7_189") (pintype "passive"))
    )
    (net (code "358") (name "/LCD_BL") (class "Default")
      (node (ref "PLCD1") (pin "34") (pinfunction "34_34") (pintype "passive"))
      (node (ref "U5") (pin "199") (pinfunction "PB9/TIM4_CH4/TIM11_CH1/I2C1_SDA/SPI2_NSS/I2S2_WS/CAN1_TX/SDIO_D5/DCMI_D7/LCD_B7_199") (pintype "passive"))
    )
    (net (code "359") (name "/LCD_CLK") (class "Default")
      (node (ref "PLCD1") (pin "30") (pinfunction "30_30") (pintype "passive"))
      (node (ref "U5") (pin "21") (pinfunction "PI14/LCD_CLK_21") (pintype "passive"))
    )
    (net (code "360") (name "/LCD_DE") (class "Default")
      (node (ref "PLCD1") (pin "33") (pinfunction "33_33") (pintype "passive"))
      (node (ref "U5") (pin "190") (pinfunction "PK7/LCD_DE_190") (pintype "passive"))
    )
    (net (code "363") (name "/LCD_G2") (class "Default")
      (node (ref "PLCD1") (pin "14") (pinfunction "14_14") (pintype "passive"))
      (node (ref "U5") (pin "121") (pinfunction "PJ9/LCD_G2_121") (pintype "passive"))
    )
    (net (code "364") (name "/LCD_G3") (class "Default")
      (node (ref "PLCD1") (pin "15") (pinfunction "15_15") (pintype "passive"))
      (node (ref "U5") (pin "122") (pinfunction "PJ10/LCD_G3_122") (pintype "passive"))
    )
    (net (code "365") (name "/LCD_G4") (class "Default")
      (node (ref "PLCD1") (pin "16") (pinfunction "16_16") (pintype "passive"))
      (node (ref "U5") (pin "123") (pinfunction "PJ11/LCD_G4_123") (pintype "passive"))
    )
    (net (code "366") (name "/LCD_G5") (class "Default")
      (node (ref "PLCD1") (pin "17") (pinfunction "17_17") (pintype "passive"))
      (node (ref "U5") (pin "126") (pinfunction "PK0/LCD_G5_126") (pintype "passive"))
    )
    (net (code "367") (name "/LCD_G6") (class "Default")
      (node (ref "PLCD1") (pin "18") (pinfunction "18_18") (pintype "passive"))
      (node (ref "U5") (pin "127") (pinfunction "PK1/LCD_G6_127") (pintype "passive"))
    )
    (net (code "368") (name "/LCD_G7") (class "Default")
      (node (ref "PLCD1") (pin "19") (pinfunction "19_19") (pintype "passive"))
      (node (ref "U5") (pin "128") (pinfunction "PK2/LCD_G7_128") (pintype "passive"))
    )
    (net (code "369") (name "/LCD_HSYNC") (class "Default")
      (node (ref "PLCD1") (pin "31") (pinfunction "31_31") (pintype "passive"))
      (node (ref "U5") (pin "19") (pinfunction "PI12/LCD_HSYNC_19") (pintype "passive"))
    )
    (net (code "370") (name "/LCD_R0") (class "Default")
      (node (ref "U5") (pin "64") (pinfunction "PI15/LCD_R0_64") (pintype "passive"))
    )
    (net (code "371") (name "/LCD_R1") (class "Default")
      (node (ref "U5") (pin "65") (pinfunction "PJ0/LCD_R1_65") (pintype "passive"))
    )
    (net (code "372") (name "/LCD_R2") (class "Default")
      (node (ref "U5") (pin "66") (pinfunction "PJ1/LCD_R2_66") (pintype "passive"))
    )
    (net (code "373") (name "/LCD_R3") (class "Default")
      (node (ref "PLCD1") (pin "6") (pinfunction "6_6") (pintype "passive"))
      (node (ref "U5") (pin "67") (pinfunction "PJ2/LCD_R3_67") (pintype "passive"))
    )
    (net (code "374") (name "/LCD_R4") (class "Default")
      (node (ref "PLCD1") (pin "7") (pinfunction "7_7") (pintype "passive"))
      (node (ref "U5") (pin "68") (pinfunction "PJ3/LCD_R4_68") (pintype "passive"))
    )
    (net (code "375") (name "/LCD_R5") (class "Default")
      (node (ref "PLCD1") (pin "8") (pinfunction "8_8") (pintype "passive"))
      (node (ref "U5") (pin "69") (pinfunction "PJ4/LCD_R5_69") (pintype "passive"))
    )
    (net (code "376") (name "/LCD_R6") (class "Default")
      (node (ref "PLCD1") (pin "9") (pinfunction "9_9") (pintype "passive"))
      (node (ref "U5") (pin "95") (pinfunction "PJ5/LCD_R6_95") (pintype "passive"))
    )
    (net (code "377") (name "/LCD_R7") (class "Default")
      (node (ref "PLCD1") (pin "10") (pinfunction "10_10") (pintype "passive"))
      (node (ref "U5") (pin "118") (pinfunction "PJ6/LCD_R7_118") (pintype "passive"))
    )
    (net (code "378") (name "/LCD_RESET") (class "Default")
      (node (ref "*R4") (pin "1") (pintype "passive"))
      (node (ref "U5") (pin "48") (pinfunction "PH4/I2C2_SCL/OTG_HS_ULPI_NXT_48") (pintype "passive"))
    )
    (net (code "379") (name "/LCD_RESIN") (class "Default")
      (node (ref "*R4") (pin "2") (pintype "passive"))
      (node (ref "PLCD1") (pin "40") (pinfunction "40_40") (pintype "passive"))
      (node (ref "R61") (pin "2") (pintype "passive"))
    )
    (net (code "380") (name "/LCD_VSYNC") (class "Default")
      (node (ref "PLCD1") (pin "32") (pinfunction "32_32") (pintype "passive"))
      (node (ref "U5") (pin "20") (pinfunction "PI13/LCD_VSYNC_20") (pintype "passive"))
    )
    (net (code "387") (name "/MCLK") (class "Default")
      (node (ref "R22") (pin "2") (pinfunction "2_2") (pintype "passive"))
      (node (ref "U5") (pin "32") (pinfunction "PH0/OSC_IN_32") (pintype "passive"))
    )
    (net (code "388") (name "/MIC_BIAS") (class "Default")
      (node (ref "C34") (pin "1") (pinfunction "1_1") (pintype "passive"))
      (node (ref "U4") (pin "12") (pinfunction "MIC_Bias_12") (pintype "passive"))
    )
    (net (code "389") (name "/MIC_N") (class "Default")
      (node (ref "U4") (pin "13") (pinfunction "MIC_N_13") (pintype "passive"))
    )
    (net (code "390") (name "/MIC_P") (class "Default")
      (node (ref "U4") (pin "15") (pinfunction "MIC_P_15") (pintype "passive"))
    )
    (net (code "391") (name "/NRST") (class "Default")
      (node (ref "C4") (pin "2") (pinfunction "2_2") (pintype "passive"))
      (node (ref "D18") (pin "1") (pinfunction "A_1") (pintype "passive"))
      (node (ref "D24") (pin "1") (pinfunction "A_1") (pintype "passive"))
      (node (ref "D4") (pin "1") (pintype "passive"))
      (node (ref "K7") (pin "1") (pinfunction "1_1") (pintype "passive"))
      (node (ref "P1") (pin "5") (pinfunction "5_5") (pintype "passive"))
      (node (ref "R2") (pin "2") (pintype "passive"))
      (node (ref "R61") (pin "1") (pintype "passive"))
      (node (ref "U5") (pin "34") (pinfunction "NRST_34") (pintype "passive"))
    )
    (net (code "392") (name "/PB10_USART3TX") (class "Default")
      (node (ref "P14") (pin "2") (pinfunction "2_2") (pintype "passive"))
      (node (ref "R17") (pin "2") (pinfunction "2_2") (pintype "passive"))
      (node (ref "U4") (pin "39") (pinfunction "RXD_39") (pintype "passive"))
      (node (ref "U5") (pin "90") (pinfunction "PB10/TIM2_CH3/I2C2_SCL/SPI2_SCK/I2S2_CK/USART3_TX/OTG_HS_ULPI_D3/ETH_MII_RX_ER_90") (pintype "passive"))
    )
    (net (code "393") (name "/PB11_USART3RX") (class "Default")
      (node (ref "P14") (pin "3") (pinfunction "3_3") (pintype "passive"))
      (node (ref "R16") (pin "2") (pinfunction "2_2") (pintype "passive"))
      (node (ref "U4") (pin "41") (pinfunction "TXD_41") (pintype "passive"))
      (node (ref "U5") (pin "91") (pinfunction "PB11/TIM2_CH4/I2C2_SDA/USART3_RX/OTG_HS_ULPI_D4/ETH_MII_TX_EN/ETH_RMII_TX_EN/LCD_G5_91") (pintype "passive"))
    )
    (net (code "394") (name "/RDY") (class "Default")
      (node (ref "D1") (pin "2") (pinfunction "K_2") (pintype "passive"))
      (node (ref "R26") (pin "1") (pinfunction "1_1") (pintype "passive"))
      (node (ref "U4") (pin "40") (pinfunction "RDY_40") (pintype "passive"))
    )
    (net (code "395") (name "/SCQ_D1") (class "Default")
      (node (ref "U5") (pin "156") (pinfunction "PI2/TIM8_CH4/_SPI2_MISO/__I2S2ext_SD/_FMC_D26/DCMI_D9/_LCD_G7_156") (pintype "passive"))
      (node (ref "USCQ1") (pin "2") (pinfunction "D1_2") (pintype "input"))
      (node (ref "USCQ10") (pin "2") (pinfunction "D1_2") (pintype "input"))
      (node (ref "USCQ11") (pin "2") (pinfunction "D1_2") (pintype "input"))
      (node (ref "USCQ12") (pin "2") (pinfunction "D1_2") (pintype "input"))
      (node (ref "USCQ13") (pin "2") (pinfunction "D1_2") (pintype "input"))
      (node (ref "USCQ14") (pin "2") (pinfunction "D1_2") (pintype "input"))
      (node (ref "USCQ15") (pin "2") (pinfunction "D1_2") (pintype "input"))
      (node (ref "USCQ16") (pin "2") (pinfunction "D1_2") (pintype "input"))
      (node (ref "USCQ17") (pin "2") (pinfunction "D1_2") (pintype "input"))
      (node (ref "USCQ18") (pin "2") (pinfunction "D1_2") (pintype "input"))
      (node (ref "USCQ19") (pin "2") (pinfunction "D1_2") (pintype "input"))
      (node (ref "USCQ2") (pin "2") (pinfunction "D1_2") (pintype "input"))
      (node (ref "USCQ20") (pin "2") (pinfunction "D1_2") (pintype "input"))
      (node (ref "USCQ21") (pin "2") (pinfunction "D1_2") (pintype "input"))
      (node (ref "USCQ22") (pin "2") (pinfunction "D1_2") (pintype "input"))
      (node (ref "USCQ23") (pin "2") (pinfunction "D1_2") (pintype "input"))
      (node (ref "USCQ24") (pin "2") (pinfunction "D1_2") (pintype "input"))
      (node (ref "USCQ25") (pin "2") (pinfunction "D1_2") (pintype "input"))
      (node (ref "USCQ26") (pin "2") (pinfunction "D1_2") (pintype "input"))
      (node (ref "USCQ27") (pin "2") (pinfunction "D1_2") (pintype "input"))
      (node (ref "USCQ28") (pin "2") (pinfunction "D1_2") (pintype "input"))
      (node (ref "USCQ29") (pin "2") (pinfunction "D1_2") (pintype "input"))
      (node (ref "USCQ3") (pin "2") (pinfunction "D1_2") (pintype "input"))
      (node (ref "USCQ30") (pin "2") (pinfunction "D1_2") (pintype "input"))
      (node (ref "USCQ4") (pin "2") (pinfunction "D1_2") (pintype "input"))
      (node (ref "USCQ5") (pin "2") (pinfunction "D1_2") (pintype "input"))
      (node (ref "USCQ6") (pin "2") (pinfunction "D1_2") (pintype "input"))
      (node (ref "USCQ7") (pin "2") (pinfunction "D1_2") (pintype "input"))
      (node (ref "USCQ8") (pin "2") (pinfunction "D1_2") (pintype "input"))
      (node (ref "USCQ9") (pin "2") (pinfunction "D1_2") (pintype "input"))
    )
    (net (code "396") (name "/SCQ_D2") (class "Default")
      (node (ref "U5") (pin "155") (pinfunction "PI1/SPI2_SCK/I2S2_CK(6)/__FMC_D25/DCMI_D8/__LCD_G6_155") (pintype "passive"))
      (node (ref "USCQ1") (pin "3") (pinfunction "D2_3") (pintype "input"))
      (node (ref "USCQ10") (pin "3") (pinfunction "D2_3") (pintype "input"))
      (node (ref "USCQ11") (pin "3") (pinfunction "D2_3") (pintype "input"))
      (node (ref "USCQ12") (pin "3") (pinfunction "D2_3") (pintype "input"))
      (node (ref "USCQ13") (pin "3") (pinfunction "D2_3") (pintype "input"))
      (node (ref "USCQ14") (pin "3") (pinfunction "D2_3") (pintype "input"))
      (node (ref "USCQ15") (pin "3") (pinfunction "D2_3") (pintype "input"))
      (node (ref "USCQ16") (pin "3") (pinfunction "D2_3") (pintype "input"))
      (node (ref "USCQ17") (pin "3") (pinfunction "D2_3") (pintype "input"))
      (node (ref "USCQ18") (pin "3") (pinfunction "D2_3") (pintype "input"))
      (node (ref "USCQ19") (pin "3") (pinfunction "D2_3") (pintype "input"))
      (node (ref "USCQ2") (pin "3") (pinfunction "D2_3") (pintype "input"))
      (node (ref "USCQ20") (pin "3") (pinfunction "D2_3") (pintype "input"))
      (node (ref "USCQ21") (pin "3") (pinfunction "D2_3") (pintype "input"))
      (node (ref "USCQ22") (pin "3") (pinfunction "D2_3") (pintype "input"))
      (node (ref "USCQ23") (pin "3") (pinfunction "D2_3") (pintype "input"))
      (node (ref "USCQ24") (pin "3") (pinfunction "D2_3") (pintype "input"))
      (node (ref "USCQ25") (pin "3") (pinfunction "D2_3") (pintype "input"))
      (node (ref "USCQ26") (pin "3") (pinfunction "D2_3") (pintype "input"))
      (node (ref "USCQ27") (pin "3") (pinfunction "D2_3") (pintype "input"))
      (node (ref "USCQ28") (pin "3") (pinfunction "D2_3") (pintype "input"))
      (node (ref "USCQ29") (pin "3") (pinfunction "D2_3") (pintype "input"))
      (node (ref "USCQ3") (pin "3") (pinfunction "D2_3") (pintype "input"))
      (node (ref "USCQ30") (pin "3") (pinfunction "D2_3") (pintype "input"))
      (node (ref "USCQ4") (pin "3") (pinfunction "D2_3") (pintype "input"))
      (node (ref "USCQ5") (pin "3") (pinfunction "D2_3") (pintype "input"))
      (node (ref "USCQ6") (pin "3") (pinfunction "D2_3") (pintype "input"))
      (node (ref "USCQ7") (pin "3") (pinfunction "D2_3") (pintype "input"))
      (node (ref "USCQ8") (pin "3") (pinfunction "D2_3") (pintype "input"))
      (node (ref "USCQ9") (pin "3") (pinfunction "D2_3") (pintype "input"))
    )
    (net (code "397") (name "/SCQ_D3") (class "Default")
      (node (ref "U5") (pin "154") (pinfunction "PI0/TIM5_CH4/__SPI2_NSS/I2S2_WS(6)/__FMC_D24/_DCMI_D13/__LCD_G5_154") (pintype "passive"))
      (node (ref "USCQ1") (pin "4") (pinfunction "D3_4") (pintype "input"))
      (node (ref "USCQ10") (pin "4") (pinfunction "D3_4") (pintype "input"))
      (node (ref "USCQ11") (pin "4") (pinfunction "D3_4") (pintype "input"))
      (node (ref "USCQ12") (pin "4") (pinfunction "D3_4") (pintype "input"))
      (node (ref "USCQ13") (pin "4") (pinfunction "D3_4") (pintype "input"))
      (node (ref "USCQ14") (pin "4") (pinfunction "D3_4") (pintype "input"))
      (node (ref "USCQ15") (pin "4") (pinfunction "D3_4") (pintype "input"))
      (node (ref "USCQ16") (pin "4") (pinfunction "D3_4") (pintype "input"))
      (node (ref "USCQ17") (pin "4") (pinfunction "D3_4") (pintype "input"))
      (node (ref "USCQ18") (pin "4") (pinfunction "D3_4") (pintype "input"))
      (node (ref "USCQ19") (pin "4") (pinfunction "D3_4") (pintype "input"))
      (node (ref "USCQ2") (pin "4") (pinfunction "D3_4") (pintype "input"))
      (node (ref "USCQ20") (pin "4") (pinfunction "D3_4") (pintype "input"))
      (node (ref "USCQ21") (pin "4") (pinfunction "D3_4") (pintype "input"))
      (node (ref "USCQ22") (pin "4") (pinfunction "D3_4") (pintype "input"))
      (node (ref "USCQ23") (pin "4") (pinfunction "D3_4") (pintype "input"))
      (node (ref "USCQ24") (pin "4") (pinfunction "D3_4") (pintype "input"))
      (node (ref "USCQ25") (pin "4") (pinfunction "D3_4") (pintype "input"))
      (node (ref "USCQ26") (pin "4") (pinfunction "D3_4") (pintype "input"))
      (node (ref "USCQ27") (pin "4") (pinfunction "D3_4") (pintype "input"))
      (node (ref "USCQ28") (pin "4") (pinfunction "D3_4") (pintype "input"))
      (node (ref "USCQ29") (pin "4") (pinfunction "D3_4") (pintype "input"))
      (node (ref "USCQ3") (pin "4") (pinfunction "D3_4") (pintype "input"))
      (node (ref "USCQ30") (pin "4") (pinfunction "D3_4") (pintype "input"))
      (node (ref "USCQ4") (pin "4") (pinfunction "D3_4") (pintype "input"))
      (node (ref "USCQ5") (pin "4") (pinfunction "D3_4") (pintype "input"))
      (node (ref "USCQ6") (pin "4") (pinfunction "D3_4") (pintype "input"))
      (node (ref "USCQ7") (pin "4") (pinfunction "D3_4") (pintype "input"))
      (node (ref "USCQ8") (pin "4") (pinfunction "D3_4") (pintype "input"))
      (node (ref "USCQ9") (pin "4") (pinfunction "D3_4") (pintype "input"))
    )
    (net (code "398") (name "/SCQ_D4") (class "Default")
      (node (ref "U5") (pin "153") (pinfunction "PH15/TIM8_CH3N/_FMC_D23/_DCMI_D11/_LCD_G4_153") (pintype "passive"))
      (node (ref "USCQ1") (pin "5") (pinfunction "D4_5") (pintype "input"))
      (node (ref "USCQ10") (pin "5") (pinfunction "D4_5") (pintype "input"))
      (node (ref "USCQ11") (pin "5") (pinfunction "D4_5") (pintype "input"))
      (node (ref "USCQ12") (pin "5") (pinfunction "D4_5") (pintype "input"))
      (node (ref "USCQ13") (pin "5") (pinfunction "D4_5") (pintype "input"))
      (node (ref "USCQ14") (pin "5") (pinfunction "D4_5") (pintype "input"))
      (node (ref "USCQ15") (pin "5") (pinfunction "D4_5") (pintype "input"))
      (node (ref "USCQ16") (pin "5") (pinfunction "D4_5") (pintype "input"))
      (node (ref "USCQ17") (pin "5") (pinfunction "D4_5") (pintype "input"))
      (node (ref "USCQ18") (pin "5") (pinfunction "D4_5") (pintype "input"))
      (node (ref "USCQ19") (pin "5") (pinfunction "D4_5") (pintype "input"))
      (node (ref "USCQ2") (pin "5") (pinfunction "D4_5") (pintype "input"))
      (node (ref "USCQ20") (pin "5") (pinfunction "D4_5") (pintype "input"))
      (node (ref "USCQ21") (pin "5") (pinfunction "D4_5") (pintype "input"))
      (node (ref "USCQ22") (pin "5") (pinfunction "D4_5") (pintype "input"))
      (node (ref "USCQ23") (pin "5") (pinfunction "D4_5") (pintype "input"))
      (node (ref "USCQ24") (pin "5") (pinfunction "D4_5") (pintype "input"))
      (node (ref "USCQ25") (pin "5") (pinfunction "D4_5") (pintype "input"))
      (node (ref "USCQ26") (pin "5") (pinfunction "D4_5") (pintype "input"))
      (node (ref "USCQ27") (pin "5") (pinfunction "D4_5") (pintype "input"))
      (node (ref "USCQ28") (pin "5") (pinfunction "D4_5") (pintype "input"))
      (node (ref "USCQ29") (pin "5") (pinfunction "D4_5") (pintype "input"))
      (node (ref "USCQ3") (pin "5") (pinfunction "D4_5") (pintype "input"))
      (node (ref "USCQ30") (pin "5") (pinfunction "D4_5") (pintype "input"))
      (node (ref "USCQ4") (pin "5") (pinfunction "D4_5") (pintype "input"))
      (node (ref "USCQ5") (pin "5") (pinfunction "D4_5") (pintype "input"))
      (node (ref "USCQ6") (pin "5") (pinfunction "D4_5") (pintype "input"))
      (node (ref "USCQ7") (pin "5") (pinfunction "D4_5") (pintype "input"))
      (node (ref "USCQ8") (pin "5") (pinfunction "D4_5") (pintype "input"))
      (node (ref "USCQ9") (pin "5") (pinfunction "D4_5") (pintype "input"))
    )
    (net (code "399") (name "/SCQ_D5") (class "Default")
      (node (ref "U5") (pin "152") (pinfunction "PH14/TIM8_CH2N/FMC_D22/DCMI_D4/_LCD_G3_152") (pintype "passive"))
      (node (ref "USCQ1") (pin "6") (pinfunction "D5_6") (pintype "input"))
      (node (ref "USCQ10") (pin "6") (pinfunction "D5_6") (pintype "input"))
      (node (ref "USCQ11") (pin "6") (pinfunction "D5_6") (pintype "input"))
      (node (ref "USCQ12") (pin "6") (pinfunction "D5_6") (pintype "input"))
      (node (ref "USCQ13") (pin "6") (pinfunction "D5_6") (pintype "input"))
      (node (ref "USCQ14") (pin "6") (pinfunction "D5_6") (pintype "input"))
      (node (ref "USCQ15") (pin "6") (pinfunction "D5_6") (pintype "input"))
      (node (ref "USCQ16") (pin "6") (pinfunction "D5_6") (pintype "input"))
      (node (ref "USCQ17") (pin "6") (pinfunction "D5_6") (pintype "input"))
      (node (ref "USCQ18") (pin "6") (pinfunction "D5_6") (pintype "input"))
      (node (ref "USCQ19") (pin "6") (pinfunction "D5_6") (pintype "input"))
      (node (ref "USCQ2") (pin "6") (pinfunction "D5_6") (pintype "input"))
      (node (ref "USCQ20") (pin "6") (pinfunction "D5_6") (pintype "input"))
      (node (ref "USCQ21") (pin "6") (pinfunction "D5_6") (pintype "input"))
      (node (ref "USCQ22") (pin "6") (pinfunction "D5_6") (pintype "input"))
      (node (ref "USCQ23") (pin "6") (pinfunction "D5_6") (pintype "input"))
      (node (ref "USCQ24") (pin "6") (pinfunction "D5_6") (pintype "input"))
      (node (ref "USCQ25") (pin "6") (pinfunction "D5_6") (pintype "input"))
      (node (ref "USCQ26") (pin "6") (pinfunction "D5_6") (pintype "input"))
      (node (ref "USCQ27") (pin "6") (pinfunction "D5_6") (pintype "input"))
      (node (ref "USCQ28") (pin "6") (pinfunction "D5_6") (pintype "input"))
      (node (ref "USCQ29") (pin "6") (pinfunction "D5_6") (pintype "input"))
      (node (ref "USCQ3") (pin "6") (pinfunction "D5_6") (pintype "input"))
      (node (ref "USCQ30") (pin "6") (pinfunction "D5_6") (pintype "input"))
      (node (ref "USCQ4") (pin "6") (pinfunction "D5_6") (pintype "input"))
      (node (ref "USCQ5") (pin "6") (pinfunction "D5_6") (pintype "input"))
      (node (ref "USCQ6") (pin "6") (pinfunction "D5_6") (pintype "input"))
      (node (ref "USCQ7") (pin "6") (pinfunction "D5_6") (pintype "input"))
      (node (ref "USCQ8") (pin "6") (pinfunction "D5_6") (pintype "input"))
      (node (ref "USCQ9") (pin "6") (pinfunction "D5_6") (pintype "input"))
    )
    (net (code "400") (name "/SCQ_D6") (class "Default")
      (node (ref "U5") (pin "151") (pinfunction "PH13/TIM8_CH1N/_CAN1_TX/FMC_D21/_LCD_G2_151") (pintype "passive"))
      (node (ref "USCQ1") (pin "7") (pinfunction "D6_7") (pintype "input"))
      (node (ref "USCQ10") (pin "7") (pinfunction "D6_7") (pintype "input"))
      (node (ref "USCQ11") (pin "7") (pinfunction "D6_7") (pintype "input"))
      (node (ref "USCQ12") (pin "7") (pinfunction "D6_7") (pintype "input"))
      (node (ref "USCQ13") (pin "7") (pinfunction "D6_7") (pintype "input"))
      (node (ref "USCQ14") (pin "7") (pinfunction "D6_7") (pintype "input"))
      (node (ref "USCQ15") (pin "7") (pinfunction "D6_7") (pintype "input"))
      (node (ref "USCQ16") (pin "7") (pinfunction "D6_7") (pintype "input"))
      (node (ref "USCQ17") (pin "7") (pinfunction "D6_7") (pintype "input"))
      (node (ref "USCQ18") (pin "7") (pinfunction "D6_7") (pintype "input"))
      (node (ref "USCQ19") (pin "7") (pinfunction "D6_7") (pintype "input"))
      (node (ref "USCQ2") (pin "7") (pinfunction "D6_7") (pintype "input"))
      (node (ref "USCQ20") (pin "7") (pinfunction "D6_7") (pintype "input"))
      (node (ref "USCQ21") (pin "7") (pinfunction "D6_7") (pintype "input"))
      (node (ref "USCQ22") (pin "7") (pinfunction "D6_7") (pintype "input"))
      (node (ref "USCQ23") (pin "7") (pinfunction "D6_7") (pintype "input"))
      (node (ref "USCQ24") (pin "7") (pinfunction "D6_7") (pintype "input"))
      (node (ref "USCQ25") (pin "7") (pinfunction "D6_7") (pintype "input"))
      (node (ref "USCQ26") (pin "7") (pinfunction "D6_7") (pintype "input"))
      (node (ref "USCQ27") (pin "7") (pinfunction "D6_7") (pintype "input"))
      (node (ref "USCQ28") (pin "7") (pinfunction "D6_7") (pintype "input"))
      (node (ref "USCQ29") (pin "7") (pinfunction "D6_7") (pintype "input"))
      (node (ref "USCQ3") (pin "7") (pinfunction "D6_7") (pintype "input"))
      (node (ref "USCQ30") (pin "7") (pinfunction "D6_7") (pintype "input"))
      (node (ref "USCQ4") (pin "7") (pinfunction "D6_7") (pintype "input"))
      (node (ref "USCQ5") (pin "7") (pinfunction "D6_7") (pintype "input"))
      (node (ref "USCQ6") (pin "7") (pinfunction "D6_7") (pintype "input"))
      (node (ref "USCQ7") (pin "7") (pinfunction "D6_7") (pintype "input"))
      (node (ref "USCQ8") (pin "7") (pinfunction "D6_7") (pintype "input"))
      (node (ref "USCQ9") (pin "7") (pinfunction "D6_7") (pintype "input"))
    )
    (net (code "401") (name "/SCQ_D7") (class "Default")
      (node (ref "U5") (pin "146") (pinfunction "PA12/TIM1_ETR/USART1_RTS/CAN1_TX/LCD_R5/OTG_FS_DP_146") (pintype "passive"))
      (node (ref "USCQ1") (pin "8") (pinfunction "D7_8") (pintype "input"))
      (node (ref "USCQ10") (pin "8") (pinfunction "D7_8") (pintype "input"))
      (node (ref "USCQ11") (pin "8") (pinfunction "D7_8") (pintype "input"))
      (node (ref "USCQ12") (pin "8") (pinfunction "D7_8") (pintype "input"))
      (node (ref "USCQ13") (pin "8") (pinfunction "D7_8") (pintype "input"))
      (node (ref "USCQ14") (pin "8") (pinfunction "D7_8") (pintype "input"))
      (node (ref "USCQ15") (pin "8") (pinfunction "D7_8") (pintype "input"))
      (node (ref "USCQ16") (pin "8") (pinfunction "D7_8") (pintype "input"))
      (node (ref "USCQ17") (pin "8") (pinfunction "D7_8") (pintype "input"))
      (node (ref "USCQ18") (pin "8") (pinfunction "D7_8") (pintype "input"))
      (node (ref "USCQ19") (pin "8") (pinfunction "D7_8") (pintype "input"))
      (node (ref "USCQ2") (pin "8") (pinfunction "D7_8") (pintype "input"))
      (node (ref "USCQ20") (pin "8") (pinfunction "D7_8") (pintype "input"))
      (node (ref "USCQ21") (pin "8") (pinfunction "D7_8") (pintype "input"))
      (node (ref "USCQ22") (pin "8") (pinfunction "D7_8") (pintype "input"))
      (node (ref "USCQ23") (pin "8") (pinfunction "D7_8") (pintype "input"))
      (node (ref "USCQ24") (pin "8") (pinfunction "D7_8") (pintype "input"))
      (node (ref "USCQ25") (pin "8") (pinfunction "D7_8") (pintype "input"))
      (node (ref "USCQ26") (pin "8") (pinfunction "D7_8") (pintype "input"))
      (node (ref "USCQ27") (pin "8") (pinfunction "D7_8") (pintype "input"))
      (node (ref "USCQ28") (pin "8") (pinfunction "D7_8") (pintype "input"))
      (node (ref "USCQ29") (pin "8") (pinfunction "D7_8") (pintype "input"))
      (node (ref "USCQ3") (pin "8") (pinfunction "D7_8") (pintype "input"))
      (node (ref "USCQ30") (pin "8") (pinfunction "D7_8") (pintype "input"))
      (node (ref "USCQ4") (pin "8") (pinfunction "D7_8") (pintype "input"))
      (node (ref "USCQ5") (pin "8") (pinfunction "D7_8") (pintype "input"))
      (node (ref "USCQ6") (pin "8") (pinfunction "D7_8") (pintype "input"))
      (node (ref "USCQ7") (pin "8") (pinfunction "D7_8") (pintype "input"))
      (node (ref "USCQ8") (pin "8") (pinfunction "D7_8") (pintype "input"))
      (node (ref "USCQ9") (pin "8") (pinfunction "D7_8") (pintype "input"))
    )
    (net (code "402") (name "/SCQ_D8") (class "Default")
      (node (ref "U5") (pin "145") (pinfunction "PA11/TIM1_CH4/_USART1_CTS/CAN1_RX/LCD_R4/OTG_FS_DM_145") (pintype "passive"))
      (node (ref "USCQ1") (pin "9") (pinfunction "D8_9") (pintype "input"))
      (node (ref "USCQ10") (pin "9") (pinfunction "D8_9") (pintype "input"))
      (node (ref "USCQ11") (pin "9") (pinfunction "D8_9") (pintype "input"))
      (node (ref "USCQ12") (pin "9") (pinfunction "D8_9") (pintype "input"))
      (node (ref "USCQ13") (pin "9") (pinfunction "D8_9") (pintype "input"))
      (node (ref "USCQ14") (pin "9") (pinfunction "D8_9") (pintype "input"))
      (node (ref "USCQ15") (pin "9") (pinfunction "D8_9") (pintype "input"))
      (node (ref "USCQ16") (pin "9") (pinfunction "D8_9") (pintype "input"))
      (node (ref "USCQ17") (pin "9") (pinfunction "D8_9") (pintype "input"))
      (node (ref "USCQ18") (pin "9") (pinfunction "D8_9") (pintype "input"))
      (node (ref "USCQ19") (pin "9") (pinfunction "D8_9") (pintype "input"))
      (node (ref "USCQ2") (pin "9") (pinfunction "D8_9") (pintype "input"))
      (node (ref "USCQ20") (pin "9") (pinfunction "D8_9") (pintype "input"))
      (node (ref "USCQ21") (pin "9") (pinfunction "D8_9") (pintype "input"))
      (node (ref "USCQ22") (pin "9") (pinfunction "D8_9") (pintype "input"))
      (node (ref "USCQ23") (pin "9") (pinfunction "D8_9") (pintype "input"))
      (node (ref "USCQ24") (pin "9") (pinfunction "D8_9") (pintype "input"))
      (node (ref "USCQ25") (pin "9") (pinfunction "D8_9") (pintype "input"))
      (node (ref "USCQ26") (pin "9") (pinfunction "D8_9") (pintype "input"))
      (node (ref "USCQ27") (pin "9") (pinfunction "D8_9") (pintype "input"))
      (node (ref "USCQ28") (pin "9") (pinfunction "D8_9") (pintype "input"))
      (node (ref "USCQ29") (pin "9") (pinfunction "D8_9") (pintype "input"))
      (node (ref "USCQ3") (pin "9") (pinfunction "D8_9") (pintype "input"))
      (node (ref "USCQ30") (pin "9") (pinfunction "D8_9") (pintype "input"))
      (node (ref "USCQ4") (pin "9") (pinfunction "D8_9") (pintype "input"))
      (node (ref "USCQ5") (pin "9") (pinfunction "D8_9") (pintype "input"))
      (node (ref "USCQ6") (pin "9") (pinfunction "D8_9") (pintype "input"))
      (node (ref "USCQ7") (pin "9") (pinfunction "D8_9") (pintype "input"))
      (node (ref "USCQ8") (pin "9") (pinfunction "D8_9") (pintype "input"))
      (node (ref "USCQ9") (pin "9") (pinfunction "D8_9") (pintype "input"))
    )
    (net (code "403") (name "/SCQ_LE1") (class "Default")
      (node (ref "U5") (pin "208") (pinfunction "PI7/TIM8_CH3/FMC_D29/__DCMI_D7/LCD_B7_208") (pintype "passive"))
      (node (ref "USCQ1") (pin "11") (pinfunction "LE_11") (pintype "input"))
    )
    (net (code "404") (name "/SCQ_LE2") (class "Default")
      (node (ref "U5") (pin "206") (pinfunction "PI5/TIM8_CH1/_FMC_NBL3/DCMI_VSYNC/_LCD_B5_206") (pintype "passive"))
      (node (ref "USCQ2") (pin "11") (pinfunction "LE_11") (pintype "input"))
    )
    (net (code "405") (name "/SCQ_LE3") (class "Default")
      (node (ref "U5") (pin "176") (pinfunction "PJ14/LCD_B2,_176") (pintype "passive"))
      (node (ref "USCQ3") (pin "11") (pinfunction "LE_11") (pintype "input"))
    )
    (net (code "406") (name "/SCQ_LE4") (class "Default")
      (node (ref "U5") (pin "174") (pinfunction "PJ12/LCD_B0_174") (pintype "passive"))
      (node (ref "USCQ4") (pin "11") (pinfunction "LE_11") (pintype "input"))
    )
    (net (code "407") (name "/SCQ_LE5") (class "Default")
      (node (ref "U5") (pin "167") (pinfunction "PD3/SPI2_SCK/I2S2_CK/USART2_CTS/FMC_CLK/DCMI_D5_167") (pintype "passive"))
      (node (ref "USCQ5") (pin "11") (pinfunction "LE_11") (pintype "input"))
    )
    (net (code "408") (name "/SCQ_LE6") (class "Default")
      (node (ref "U5") (pin "157") (pinfunction "PI3/TIM8_ETR/_SPI2_MOSI/I2S2_SD/_FMC_D27/_DCMI_D10_157") (pintype "passive"))
      (node (ref "USCQ6") (pin "11") (pinfunction "LE_11") (pintype "input"))
    )
    (net (code "409") (name "/SCQ_LE7") (class "Default")
      (node (ref "U5") (pin "139") (pinfunction "PC7/TIM3_CH2/TIM8_CH2/I2S3_MCK/USART6_RX/SDIO_D7/DCMI_D1_139") (pintype "passive"))
      (node (ref "USCQ7") (pin "11") (pinfunction "LE_11") (pintype "input"))
    )
    (net (code "410") (name "/SCQ_LE8") (class "Default")
      (node (ref "U5") (pin "134") (pinfunction "PG7/USART6_CK/_FMC_INT3/__DCMI_D13/_LCD_CLK_134") (pintype "passive"))
      (node (ref "USCQ8") (pin "11") (pinfunction "LE_11") (pintype "input"))
    )
    (net (code "411") (name "/SCQ_LE9") (class "Default")
      (node (ref "U5") (pin "130") (pinfunction "PG3/FMC_A13_130") (pintype "passive"))
      (node (ref "USCQ9") (pin "11") (pinfunction "LE_11") (pintype "input"))
    )
    (net (code "412") (name "/SCQ_LE10") (class "Default")
      (node (ref "U5") (pin "119") (pinfunction "PJ7/LCD_G0_119") (pintype "passive"))
      (node (ref "USCQ10") (pin "11") (pinfunction "LE_11") (pintype "input"))
    )
    (net (code "413") (name "/SCQ_LE11") (class "Default")
      (node (ref "U5") (pin "105") (pinfunction "PB13/TIM1_CH1N/SPI2_SCK/I2S2_CK/USART3_CTS/CAN2_TX/OTG_HS_ULPI_D6/ETH_MII_TXD1/ETH_RMI__I_TXD1_105") (pintype "passive"))
      (node (ref "USCQ11") (pin "11") (pinfunction "LE_11") (pintype "input"))
    )
    (net (code "414") (name "/SCQ_LE12") (class "Default")
      (node (ref "U5") (pin "107") (pinfunction "PB15/RTC_REFIN/TIM1_CH3N/TIM8_CH3N/SPI2_MOSI/I2S2_SD/TIM12_CH2/OTG_HS_DP_107") (pintype "passive"))
      (node (ref "USCQ12") (pin "11") (pinfunction "LE_11") (pintype "input"))
    )
    (net (code "415") (name "/SCQ_LE13") (class "Default")
      (node (ref "U5") (pin "102") (pinfunction "PH12/TIM5_CH3/_FMC_D20/_DCMI_D3/_LCD_R6_102") (pintype "passive"))
      (node (ref "USCQ13") (pin "11") (pinfunction "LE_11") (pintype "input"))
    )
    (net (code "416") (name "/SCQ_LE14") (class "Default")
      (node (ref "U5") (pin "100") (pinfunction "PH10/TIM5_CH1/FMC_D18/_DCMI_D1/LCD_R4_100") (pintype "passive"))
      (node (ref "USCQ14") (pin "11") (pinfunction "LE_11") (pintype "input"))
    )
    (net (code "417") (name "/SCQ_LE15") (class "Default")
      (node (ref "U5") (pin "96") (pinfunction "PH6/I2C2_SMBA/SPI5_SCK/__TIM12_CH1/ETH_MII_RXD2/FMC_SDNE1/DCMI_D8_96") (pintype "passive"))
      (node (ref "USCQ15") (pin "11") (pinfunction "LE_11") (pintype "input"))
    )
    (net (code "418") (name "/SCQ_LE16") (class "Default")
      (node (ref "U5") (pin "1") (pinfunction "PE2/TRACECLK/SPI4_SCK/SAI1_MCLK_A/ETH_MII_TXD3/FMC_A23_1") (pintype "passive"))
      (node (ref "USCQ16") (pin "11") (pinfunction "LE_11") (pintype "input"))
    )
    (net (code "419") (name "/SCQ_LE17") (class "Default")
      (node (ref "U5") (pin "207") (pinfunction "PI6/TIM8_CH2,_FMC_D28/DCMI_D6/_LCD_B6_207") (pintype "passive"))
      (node (ref "USCQ17") (pin "11") (pinfunction "LE_11") (pintype "input"))
    )
    (net (code "420") (name "/SCQ_LE18") (class "Default")
      (node (ref "U5") (pin "205") (pinfunction "PI4/TIM8_BKIN/_FMC_NBL2/DCMI_D5/_LCD_B4_205") (pintype "passive"))
      (node (ref "USCQ18") (pin "11") (pinfunction "LE_11") (pintype "input"))
    )
    (net (code "421") (name "/SCQ_LE19") (class "Default")
      (node (ref "U5") (pin "175") (pinfunction "PJ13/LCD_B1_175") (pintype "passive"))
      (node (ref "USCQ19") (pin "11") (pinfunction "LE_11") (pintype "input"))
    )
    (net (code "422") (name "/SCQ_LE20") (class "Default")
      (node (ref "U5") (pin "173") (pinfunction "PD7/USART2_CK/FMC_NE1/FMC_NCE2_173") (pintype "passive"))
      (node (ref "USCQ20") (pin "11") (pinfunction "LE_11") (pintype "input"))
    )
    (net (code "423") (name "/SCQ_LE21") (class "Default")
      (node (ref "U5") (pin "160") (pinfunction "PA15/JTDI/TIM2_CH1/TIM2_ETR/SPI1_NSS/SPI3_NSS/I2S3_WS_160") (pintype "passive"))
      (node (ref "USCQ21") (pin "11") (pinfunction "LE_11") (pintype "input"))
    )
    (net (code "424") (name "/SCQ_LE22") (class "Default")
      (node (ref "U5") (pin "142") (pinfunction "PA8/MCO1/TIM1_CH1/_I2C3_SCL/USART1_CK/OTG_FS_SOF/LCD_R6_142") (pintype "passive"))
      (node (ref "USCQ22") (pin "11") (pinfunction "LE_11") (pintype "input"))
    )
    (net (code "425") (name "/SCQ_LE23") (class "Default")
      (node (ref "U5") (pin "138") (pinfunction "PC6/TIM3_CH1/TIM8_CH1/_I2S2_MCK/USART6_TX/SDIO_D6/DCMI_D0/LCD_HSYNC_138") (pintype "passive"))
      (node (ref "USCQ23") (pin "11") (pinfunction "LE_11") (pintype "input"))
    )
    (net (code "426") (name "/SCQ_LE24") (class "Default")
      (node (ref "U5") (pin "133") (pinfunction "PG6/FMC_INT2/_DCMI_D12_133") (pintype "passive"))
      (node (ref "USCQ24") (pin "11") (pinfunction "LE_11") (pintype "input"))
    )
    (net (code "427") (name "/SCQ_LE25") (class "Default")
      (node (ref "U5") (pin "120") (pinfunction "PJ8/LCD_G1_120") (pintype "passive"))
      (node (ref "USCQ25") (pin "11") (pinfunction "LE_11") (pintype "input"))
    )
    (net (code "428") (name "/SCQ_LE26") (class "Default")
      (node (ref "U5") (pin "113") (pinfunction "PD13/TIM4_CH2/_FMC_A18_113") (pintype "passive"))
      (node (ref "USCQ26") (pin "11") (pinfunction "LE_11") (pintype "input"))
    )
    (net (code "429") (name "/SCQ_LE27") (class "Default")
      (node (ref "U5") (pin "106") (pinfunction "PB14/TIM1_CH2N/TIM8_CH2N/SPI2_MISO/I2S2ext_SD/USART3_RTS/TIM12_CH1/OTG_HS_DM_106") (pintype "passive"))
      (node (ref "USCQ27") (pin "11") (pinfunction "LE_11") (pintype "input"))
    )
    (net (code "430") (name "/SCQ_LE28") (class "Default")
      (node (ref "U5") (pin "104") (pinfunction "PB12/TIM1_BKIN/_I2C2_SMBA/_SPI2_NSS/I2S2_WS/USART3_CK/_CAN2_RX/OTG_HS_ULPI_D5/ETH_MII_TXD0/ETH_RMI__I_TXD0/OTG_HS_ID_104") (pintype "passive"))
      (node (ref "USCQ28") (pin "11") (pinfunction "LE_11") (pintype "input"))
    )
    (net (code "431") (name "/SCQ_LE29") (class "Default")
      (node (ref "U5") (pin "101") (pinfunction "PH11/TIM5_CH2/FMC_D19/_DCMI_D2/LCD_R5_101") (pintype "passive"))
      (node (ref "USCQ29") (pin "11") (pinfunction "LE_11") (pintype "input"))
    )
    (net (code "432") (name "/SCQ_LE30") (class "Default")
      (node (ref "U5") (pin "99") (pinfunction "PH9/I2C3_SMBA/_TIM12_CH2/_FMC_D17/DCMI_D0/LCD_R3_99") (pintype "passive"))
      (node (ref "USCQ30") (pin "11") (pinfunction "LE_11") (pintype "input"))
    )
    (net (code "433") (name "/SCQ_Q1") (class "Default")
      (node (ref "UDLDG1") (pin "1") (pinfunction "IN1_1") (pintype "passive"))
      (node (ref "USCQ1") (pin "19") (pinfunction "Q1_19") (pintype "tri_state"))
    )
    (net (code "434") (name "/SCQ_Q2") (class "Default")
      (node (ref "UDLDG1") (pin "2") (pinfunction "IN2_2") (pintype "passive"))
      (node (ref "USCQ1") (pin "18") (pinfunction "Q2_18") (pintype "tri_state"))
    )
    (net (code "435") (name "/SCQ_Q3") (class "Default")
      (node (ref "UDLDG1") (pin "3") (pinfunction "IN3_3") (pintype "passive"))
      (node (ref "USCQ1") (pin "17") (pinfunction "Q3_17") (pintype "tri_state"))
    )
    (net (code "436") (name "/SCQ_Q4") (class "Default")
      (node (ref "UDLDG1") (pin "4") (pinfunction "IN4_4") (pintype "passive"))
      (node (ref "USCQ1") (pin "16") (pinfunction "Q4_16") (pintype "tri_state"))
    )
    (net (code "437") (name "/SCQ_Q5") (class "Default")
      (node (ref "UDLDG1") (pin "5") (pinfunction "IN5_5") (pintype "passive"))
      (node (ref "USCQ1") (pin "15") (pinfunction "Q5_15") (pintype "tri_state"))
    )
    (net (code "438") (name "/SCQ_Q6") (class "Default")
      (node (ref "UDLDG1") (pin "6") (pinfunction "IN6_6") (pintype "passive"))
      (node (ref "USCQ1") (pin "14") (pinfunction "Q6_14") (pintype "tri_state"))
    )
    (net (code "439") (name "/SCQ_Q7") (class "Default")
      (node (ref "UDLDG1") (pin "7") (pinfunction "IN7_7") (pintype "passive"))
      (node (ref "USCQ1") (pin "13") (pinfunction "Q7_13") (pintype "tri_state"))
    )
    (net (code "440") (name "/SCQ_Q8") (class "Default")
      (node (ref "UDLDG1") (pin "8") (pinfunction "IN8_8") (pintype "passive"))
      (node (ref "USCQ1") (pin "12") (pinfunction "Q8_12") (pintype "tri_state"))
    )
    (net (code "441") (name "/SCQ_Q9") (class "Default")
      (node (ref "UDLDG2") (pin "1") (pinfunction "IN1_1") (pintype "passive"))
      (node (ref "USCQ2") (pin "19") (pinfunction "Q1_19") (pintype "tri_state"))
    )
    (net (code "442") (name "/SCQ_Q10") (class "Default")
      (node (ref "UDLDG2") (pin "2") (pinfunction "IN2_2") (pintype "passive"))
      (node (ref "USCQ2") (pin "18") (pinfunction "Q2_18") (pintype "tri_state"))
    )
    (net (code "443") (name "/SCQ_Q11") (class "Default")
      (node (ref "UDLDG2") (pin "3") (pinfunction "IN3_3") (pintype "passive"))
      (node (ref "USCQ2") (pin "17") (pinfunction "Q3_17") (pintype "tri_state"))
    )
    (net (code "444") (name "/SCQ_Q12") (class "Default")
      (node (ref "UDLDG2") (pin "4") (pinfunction "IN4_4") (pintype "passive"))
      (node (ref "USCQ2") (pin "16") (pinfunction "Q4_16") (pintype "tri_state"))
    )
    (net (code "445") (name "/SCQ_Q13") (class "Default")
      (node (ref "UDLDG2") (pin "5") (pinfunction "IN5_5") (pintype "passive"))
      (node (ref "USCQ2") (pin "15") (pinfunction "Q5_15") (pintype "tri_state"))
    )
    (net (code "446") (name "/SCQ_Q14") (class "Default")
      (node (ref "UDLDG2") (pin "6") (pinfunction "IN6_6") (pintype "passive"))
      (node (ref "USCQ2") (pin "14") (pinfunction "Q6_14") (pintype "tri_state"))
    )
    (net (code "447") (name "/SCQ_Q15") (class "Default")
      (node (ref "UDLDG2") (pin "7") (pinfunction "IN7_7") (pintype "passive"))
      (node (ref "USCQ2") (pin "13") (pinfunction "Q7_13") (pintype "tri_state"))
    )
    (net (code "448") (name "/SCQ_Q16") (class "Default")
      (node (ref "UDLDG2") (pin "8") (pinfunction "IN8_8") (pintype "passive"))
      (node (ref "USCQ2") (pin "12") (pinfunction "Q8_12") (pintype "tri_state"))
    )
    (net (code "449") (name "/SCQ_Q17") (class "Default")
      (node (ref "UDLDG3") (pin "1") (pinfunction "IN1_1") (pintype "passive"))
      (node (ref "USCQ3") (pin "19") (pinfunction "Q1_19") (pintype "tri_state"))
    )
    (net (code "450") (name "/SCQ_Q18") (class "Default")
      (node (ref "UDLDG3") (pin "2") (pinfunction "IN2_2") (pintype "passive"))
      (node (ref "USCQ3") (pin "18") (pinfunction "Q2_18") (pintype "tri_state"))
    )
    (net (code "451") (name "/SCQ_Q19") (class "Default")
      (node (ref "UDLDG3") (pin "3") (pinfunction "IN3_3") (pintype "passive"))
      (node (ref "USCQ3") (pin "17") (pinfunction "Q3_17") (pintype "tri_state"))
    )
    (net (code "452") (name "/SCQ_Q20") (class "Default")
      (node (ref "UDLDG3") (pin "4") (pinfunction "IN4_4") (pintype "passive"))
      (node (ref "USCQ3") (pin "16") (pinfunction "Q4_16") (pintype "tri_state"))
    )
    (net (code "453") (name "/SCQ_Q21") (class "Default")
      (node (ref "UDLDG3") (pin "5") (pinfunction "IN5_5") (pintype "passive"))
      (node (ref "USCQ3") (pin "15") (pinfunction "Q5_15") (pintype "tri_state"))
    )
    (net (code "454") (name "/SCQ_Q22") (class "Default")
      (node (ref "UDLDG3") (pin "6") (pinfunction "IN6_6") (pintype "passive"))
      (node (ref "USCQ3") (pin "14") (pinfunction "Q6_14") (pintype "tri_state"))
    )
    (net (code "455") (name "/SCQ_Q23") (class "Default")
      (node (ref "UDLDG3") (pin "7") (pinfunction "IN7_7") (pintype "passive"))
      (node (ref "USCQ3") (pin "13") (pinfunction "Q7_13") (pintype "tri_state"))
    )
    (net (code "456") (name "/SCQ_Q24") (class "Default")
      (node (ref "UDLDG3") (pin "8") (pinfunction "IN8_8") (pintype "passive"))
      (node (ref "USCQ3") (pin "12") (pinfunction "Q8_12") (pintype "tri_state"))
    )
    (net (code "457") (name "/SCQ_Q25") (class "Default")
      (node (ref "UDLDG4") (pin "1") (pinfunction "IN1_1") (pintype "passive"))
      (node (ref "USCQ4") (pin "19") (pinfunction "Q1_19") (pintype "tri_state"))
    )
    (net (code "458") (name "/SCQ_Q26") (class "Default")
      (node (ref "UDLDG4") (pin "2") (pinfunction "IN2_2") (pintype "passive"))
      (node (ref "USCQ4") (pin "18") (pinfunction "Q2_18") (pintype "tri_state"))
    )
    (net (code "459") (name "/SCQ_Q27") (class "Default")
      (node (ref "UDLDG4") (pin "3") (pinfunction "IN3_3") (pintype "passive"))
      (node (ref "USCQ4") (pin "17") (pinfunction "Q3_17") (pintype "tri_state"))
    )
    (net (code "460") (name "/SCQ_Q28") (class "Default")
      (node (ref "UDLDG4") (pin "4") (pinfunction "IN4_4") (pintype "passive"))
      (node (ref "USCQ4") (pin "16") (pinfunction "Q4_16") (pintype "tri_state"))
    )
    (net (code "461") (name "/SCQ_Q29") (class "Default")
      (node (ref "UDLDG4") (pin "5") (pinfunction "IN5_5") (pintype "passive"))
      (node (ref "USCQ4") (pin "15") (pinfunction "Q5_15") (pintype "tri_state"))
    )
    (net (code "462") (name "/SCQ_Q30") (class "Default")
      (node (ref "UDLDG4") (pin "6") (pinfunction "IN6_6") (pintype "passive"))
      (node (ref "USCQ4") (pin "14") (pinfunction "Q6_14") (pintype "tri_state"))
    )
    (net (code "463") (name "/SCQ_Q31") (class "Default")
      (node (ref "UDLDG4") (pin "7") (pinfunction "IN7_7") (pintype "passive"))
      (node (ref "USCQ4") (pin "13") (pinfunction "Q7_13") (pintype "tri_state"))
    )
    (net (code "464") (name "/SCQ_Q32") (class "Default")
      (node (ref "UDLDG4") (pin "8") (pinfunction "IN8_8") (pintype "passive"))
      (node (ref "USCQ4") (pin "12") (pinfunction "Q8_12") (pintype "tri_state"))
    )
    (net (code "465") (name "/SCQ_Q33") (class "Default")
      (node (ref "UDLDG5") (pin "1") (pinfunction "IN1_1") (pintype "passive"))
      (node (ref "USCQ5") (pin "19") (pinfunction "Q1_19") (pintype "tri_state"))
    )
    (net (code "466") (name "/SCQ_Q34") (class "Default")
      (node (ref "UDLDG5") (pin "2") (pinfunction "IN2_2") (pintype "passive"))
      (node (ref "USCQ5") (pin "18") (pinfunction "Q2_18") (pintype "tri_state"))
    )
    (net (code "467") (name "/SCQ_Q35") (class "Default")
      (node (ref "UDLDG5") (pin "3") (pinfunction "IN3_3") (pintype "passive"))
      (node (ref "USCQ5") (pin "17") (pinfunction "Q3_17") (pintype "tri_state"))
    )
    (net (code "468") (name "/SCQ_Q36") (class "Default")
      (node (ref "UDLDG5") (pin "4") (pinfunction "IN4_4") (pintype "passive"))
      (node (ref "USCQ5") (pin "16") (pinfunction "Q4_16") (pintype "tri_state"))
    )
    (net (code "469") (name "/SCQ_Q37") (class "Default")
      (node (ref "UDLDG5") (pin "5") (pinfunction "IN5_5") (pintype "passive"))
      (node (ref "USCQ5") (pin "15") (pinfunction "Q5_15") (pintype "tri_state"))
    )
    (net (code "470") (name "/SCQ_Q38") (class "Default")
      (node (ref "UDLDG5") (pin "6") (pinfunction "IN6_6") (pintype "passive"))
      (node (ref "USCQ5") (pin "14") (pinfunction "Q6_14") (pintype "tri_state"))
    )
    (net (code "471") (name "/SCQ_Q39") (class "Default")
      (node (ref "UDLDG5") (pin "7") (pinfunction "IN7_7") (pintype "passive"))
      (node (ref "USCQ5") (pin "13") (pinfunction "Q7_13") (pintype "tri_state"))
    )
    (net (code "472") (name "/SCQ_Q40") (class "Default")
      (node (ref "UDLDG5") (pin "8") (pinfunction "IN8_8") (pintype "passive"))
      (node (ref "USCQ5") (pin "12") (pinfunction "Q8_12") (pintype "tri_state"))
    )
    (net (code "473") (name "/SCQ_Q41") (class "Default")
      (node (ref "UDLDG6") (pin "1") (pinfunction "IN1_1") (pintype "passive"))
      (node (ref "USCQ6") (pin "19") (pinfunction "Q1_19") (pintype "tri_state"))
    )
    (net (code "474") (name "/SCQ_Q42") (class "Default")
      (node (ref "UDLDG6") (pin "2") (pinfunction "IN2_2") (pintype "passive"))
      (node (ref "USCQ6") (pin "18") (pinfunction "Q2_18") (pintype "tri_state"))
    )
    (net (code "475") (name "/SCQ_Q43") (class "Default")
      (node (ref "UDLDG6") (pin "3") (pinfunction "IN3_3") (pintype "passive"))
      (node (ref "USCQ6") (pin "17") (pinfunction "Q3_17") (pintype "tri_state"))
    )
    (net (code "476") (name "/SCQ_Q44") (class "Default")
      (node (ref "UDLDG6") (pin "4") (pinfunction "IN4_4") (pintype "passive"))
      (node (ref "USCQ6") (pin "16") (pinfunction "Q4_16") (pintype "tri_state"))
    )
    (net (code "477") (name "/SCQ_Q45") (class "Default")
      (node (ref "UDLDG6") (pin "5") (pinfunction "IN5_5") (pintype "passive"))
      (node (ref "USCQ6") (pin "15") (pinfunction "Q5_15") (pintype "tri_state"))
    )
    (net (code "478") (name "/SCQ_Q46") (class "Default")
      (node (ref "UDLDG6") (pin "6") (pinfunction "IN6_6") (pintype "passive"))
      (node (ref "USCQ6") (pin "14") (pinfunction "Q6_14") (pintype "tri_state"))
    )
    (net (code "479") (name "/SCQ_Q47") (class "Default")
      (node (ref "UDLDG6") (pin "7") (pinfunction "IN7_7") (pintype "passive"))
      (node (ref "USCQ6") (pin "13") (pinfunction "Q7_13") (pintype "tri_state"))
    )
    (net (code "480") (name "/SCQ_Q48") (class "Default")
      (node (ref "UDLDG6") (pin "8") (pinfunction "IN8_8") (pintype "passive"))
      (node (ref "USCQ6") (pin "12") (pinfunction "Q8_12") (pintype "tri_state"))
    )
    (net (code "481") (name "/SCQ_Q49") (class "Default")
      (node (ref "UDLDG7") (pin "1") (pinfunction "IN1_1") (pintype "passive"))
      (node (ref "USCQ7") (pin "19") (pinfunction "Q1_19") (pintype "tri_state"))
    )
    (net (code "482") (name "/SCQ_Q50") (class "Default")
      (node (ref "UDLDG7") (pin "2") (pinfunction "IN2_2") (pintype "passive"))
      (node (ref "USCQ7") (pin "18") (pinfunction "Q2_18") (pintype "tri_state"))
    )
    (net (code "483") (name "/SCQ_Q51") (class "Default")
      (node (ref "UDLDG7") (pin "3") (pinfunction "IN3_3") (pintype "passive"))
      (node (ref "USCQ7") (pin "17") (pinfunction "Q3_17") (pintype "tri_state"))
    )
    (net (code "484") (name "/SCQ_Q52") (class "Default")
      (node (ref "UDLDG7") (pin "4") (pinfunction "IN4_4") (pintype "passive"))
      (node (ref "USCQ7") (pin "16") (pinfunction "Q4_16") (pintype "tri_state"))
    )
    (net (code "485") (name "/SCQ_Q53") (class "Default")
      (node (ref "UDLDG7") (pin "5") (pinfunction "IN5_5") (pintype "passive"))
      (node (ref "USCQ7") (pin "15") (pinfunction "Q5_15") (pintype "tri_state"))
    )
    (net (code "486") (name "/SCQ_Q54") (class "Default")
      (node (ref "UDLDG7") (pin "6") (pinfunction "IN6_6") (pintype "passive"))
      (node (ref "USCQ7") (pin "14") (pinfunction "Q6_14") (pintype "tri_state"))
    )
    (net (code "487") (name "/SCQ_Q55") (class "Default")
      (node (ref "UDLDG7") (pin "7") (pinfunction "IN7_7") (pintype "passive"))
      (node (ref "USCQ7") (pin "13") (pinfunction "Q7_13") (pintype "tri_state"))
    )
    (net (code "488") (name "/SCQ_Q56") (class "Default")
      (node (ref "UDLDG7") (pin "8") (pinfunction "IN8_8") (pintype "passive"))
      (node (ref "USCQ7") (pin "12") (pinfunction "Q8_12") (pintype "tri_state"))
    )
    (net (code "489") (name "/SCQ_Q57") (class "Default")
      (node (ref "UDLDG8") (pin "1") (pinfunction "IN1_1") (pintype "passive"))
      (node (ref "USCQ8") (pin "19") (pinfunction "Q1_19") (pintype "tri_state"))
    )
    (net (code "490") (name "/SCQ_Q58") (class "Default")
      (node (ref "UDLDG8") (pin "2") (pinfunction "IN2_2") (pintype "passive"))
      (node (ref "USCQ8") (pin "18") (pinfunction "Q2_18") (pintype "tri_state"))
    )
    (net (code "491") (name "/SCQ_Q59") (class "Default")
      (node (ref "UDLDG8") (pin "3") (pinfunction "IN3_3") (pintype "passive"))
      (node (ref "USCQ8") (pin "17") (pinfunction "Q3_17") (pintype "tri_state"))
    )
    (net (code "492") (name "/SCQ_Q60") (class "Default")
      (node (ref "UDLDG8") (pin "4") (pinfunction "IN4_4") (pintype "passive"))
      (node (ref "USCQ8") (pin "16") (pinfunction "Q4_16") (pintype "tri_state"))
    )
    (net (code "493") (name "/SCQ_Q61") (class "Default")
      (node (ref "UDLDG8") (pin "5") (pinfunction "IN5_5") (pintype "passive"))
      (node (ref "USCQ8") (pin "15") (pinfunction "Q5_15") (pintype "tri_state"))
    )
    (net (code "494") (name "/SCQ_Q62") (class "Default")
      (node (ref "UDLDG8") (pin "6") (pinfunction "IN6_6") (pintype "passive"))
      (node (ref "USCQ8") (pin "14") (pinfunction "Q6_14") (pintype "tri_state"))
    )
    (net (code "495") (name "/SCQ_Q63") (class "Default")
      (node (ref "UDLDG8") (pin "7") (pinfunction "IN7_7") (pintype "passive"))
      (node (ref "USCQ8") (pin "13") (pinfunction "Q7_13") (pintype "tri_state"))
    )
    (net (code "496") (name "/SCQ_Q64") (class "Default")
      (node (ref "UDLDG8") (pin "8") (pinfunction "IN8_8") (pintype "passive"))
      (node (ref "USCQ8") (pin "12") (pinfunction "Q8_12") (pintype "tri_state"))
    )
    (net (code "497") (name "/SCQ_Q65") (class "Default")
      (node (ref "UDLDG9") (pin "1") (pinfunction "IN1_1") (pintype "passive"))
      (node (ref "USCQ9") (pin "19") (pinfunction "Q1_19") (pintype "tri_state"))
    )
    (net (code "498") (name "/SCQ_Q66") (class "Default")
      (node (ref "UDLDG9") (pin "2") (pinfunction "IN2_2") (pintype "passive"))
      (node (ref "USCQ9") (pin "18") (pinfunction "Q2_18") (pintype "tri_state"))
    )
    (net (code "499") (name "/SCQ_Q67") (class "Default")
      (node (ref "UDLDG9") (pin "3") (pinfunction "IN3_3") (pintype "passive"))
      (node (ref "USCQ9") (pin "17") (pinfunction "Q3_17") (pintype "tri_state"))
    )
    (net (code "500") (name "/SCQ_Q68") (class "Default")
      (node (ref "UDLDG9") (pin "4") (pinfunction "IN4_4") (pintype "passive"))
      (node (ref "USCQ9") (pin "16") (pinfunction "Q4_16") (pintype "tri_state"))
    )
    (net (code "501") (name "/SCQ_Q69") (class "Default")
      (node (ref "UDLDG9") (pin "5") (pinfunction "IN5_5") (pintype "passive"))
      (node (ref "USCQ9") (pin "15") (pinfunction "Q5_15") (pintype "tri_state"))
    )
    (net (code "502") (name "/SCQ_Q70") (class "Default")
      (node (ref "UDLDG9") (pin "6") (pinfunction "IN6_6") (pintype "passive"))
      (node (ref "USCQ9") (pin "14") (pinfunction "Q6_14") (pintype "tri_state"))
    )
    (net (code "503") (name "/SCQ_Q71") (class "Default")
      (node (ref "UDLDG9") (pin "7") (pinfunction "IN7_7") (pintype "passive"))
      (node (ref "USCQ9") (pin "13") (pinfunction "Q7_13") (pintype "tri_state"))
    )
    (net (code "504") (name "/SCQ_Q72") (class "Default")
      (node (ref "UDLDG9") (pin "8") (pinfunction "IN8_8") (pintype "passive"))
      (node (ref "USCQ9") (pin "12") (pinfunction "Q8_12") (pintype "tri_state"))
    )
    (net (code "505") (name "/SCQ_Q73") (class "Default")
      (node (ref "UDLDG10") (pin "1") (pinfunction "IN1_1") (pintype "passive"))
      (node (ref "USCQ10") (pin "19") (pinfunction "Q1_19") (pintype "tri_state"))
    )
    (net (code "506") (name "/SCQ_Q74") (class "Default")
      (node (ref "UDLDG10") (pin "2") (pinfunction "IN2_2") (pintype "passive"))
      (node (ref "USCQ10") (pin "18") (pinfunction "Q2_18") (pintype "tri_state"))
    )
    (net (code "507") (name "/SCQ_Q75") (class "Default")
      (node (ref "UDLDG10") (pin "3") (pinfunction "IN3_3") (pintype "passive"))
      (node (ref "USCQ10") (pin "17") (pinfunction "Q3_17") (pintype "tri_state"))
    )
    (net (code "508") (name "/SCQ_Q76") (class "Default")
      (node (ref "UDLDG10") (pin "4") (pinfunction "IN4_4") (pintype "passive"))
      (node (ref "USCQ10") (pin "16") (pinfunction "Q4_16") (pintype "tri_state"))
    )
    (net (code "509") (name "/SCQ_Q77") (class "Default")
      (node (ref "UDLDG10") (pin "5") (pinfunction "IN5_5") (pintype "passive"))
      (node (ref "USCQ10") (pin "15") (pinfunction "Q5_15") (pintype "tri_state"))
    )
    (net (code "510") (name "/SCQ_Q78") (class "Default")
      (node (ref "UDLDG10") (pin "6") (pinfunction "IN6_6") (pintype "passive"))
      (node (ref "USCQ10") (pin "14") (pinfunction "Q6_14") (pintype "tri_state"))
    )
    (net (code "511") (name "/SCQ_Q79") (class "Default")
      (node (ref "UDLDG10") (pin "7") (pinfunction "IN7_7") (pintype "passive"))
      (node (ref "USCQ10") (pin "13") (pinfunction "Q7_13") (pintype "tri_state"))
    )
    (net (code "512") (name "/SCQ_Q80") (class "Default")
      (node (ref "UDLDG10") (pin "8") (pinfunction "IN8_8") (pintype "passive"))
      (node (ref "USCQ10") (pin "12") (pinfunction "Q8_12") (pintype "tri_state"))
    )
    (net (code "513") (name "/SCQ_Q81") (class "Default")
      (node (ref "UDLDG11") (pin "1") (pinfunction "IN1_1") (pintype "passive"))
      (node (ref "USCQ11") (pin "19") (pinfunction "Q1_19") (pintype "tri_state"))
    )
    (net (code "514") (name "/SCQ_Q82") (class "Default")
      (node (ref "UDLDG11") (pin "2") (pinfunction "IN2_2") (pintype "passive"))
      (node (ref "USCQ11") (pin "18") (pinfunction "Q2_18") (pintype "tri_state"))
    )
    (net (code "515") (name "/SCQ_Q83") (class "Default")
      (node (ref "UDLDG11") (pin "3") (pinfunction "IN3_3") (pintype "passive"))
      (node (ref "USCQ11") (pin "17") (pinfunction "Q3_17") (pintype "tri_state"))
    )
    (net (code "516") (name "/SCQ_Q84") (class "Default")
      (node (ref "UDLDG11") (pin "4") (pinfunction "IN4_4") (pintype "passive"))
      (node (ref "USCQ11") (pin "16") (pinfunction "Q4_16") (pintype "tri_state"))
    )
    (net (code "517") (name "/SCQ_Q85") (class "Default")
      (node (ref "UDLDG11") (pin "5") (pinfunction "IN5_5") (pintype "passive"))
      (node (ref "USCQ11") (pin "15") (pinfunction "Q5_15") (pintype "tri_state"))
    )
    (net (code "518") (name "/SCQ_Q86") (class "Default")
      (node (ref "UDLDG11") (pin "6") (pinfunction "IN6_6") (pintype "passive"))
      (node (ref "USCQ11") (pin "14") (pinfunction "Q6_14") (pintype "tri_state"))
    )
    (net (code "519") (name "/SCQ_Q87") (class "Default")
      (node (ref "UDLDG11") (pin "7") (pinfunction "IN7_7") (pintype "passive"))
      (node (ref "USCQ11") (pin "13") (pinfunction "Q7_13") (pintype "tri_state"))
    )
    (net (code "520") (name "/SCQ_Q88") (class "Default")
      (node (ref "UDLDG11") (pin "8") (pinfunction "IN8_8") (pintype "passive"))
      (node (ref "USCQ11") (pin "12") (pinfunction "Q8_12") (pintype "tri_state"))
    )
    (net (code "521") (name "/SCQ_Q89") (class "Default")
      (node (ref "UDLDG12") (pin "1") (pinfunction "IN1_1") (pintype "passive"))
      (node (ref "USCQ12") (pin "19") (pinfunction "Q1_19") (pintype "tri_state"))
    )
    (net (code "522") (name "/SCQ_Q90") (class "Default")
      (node (ref "UDLDG12") (pin "2") (pinfunction "IN2_2") (pintype "passive"))
      (node (ref "USCQ12") (pin "18") (pinfunction "Q2_18") (pintype "tri_state"))
    )
    (net (code "523") (name "/SCQ_Q91") (class "Default")
      (node (ref "UDLDG12") (pin "3") (pinfunction "IN3_3") (pintype "passive"))
      (node (ref "USCQ12") (pin "17") (pinfunction "Q3_17") (pintype "tri_state"))
    )
    (net (code "524") (name "/SCQ_Q92") (class "Default")
      (node (ref "UDLDG12") (pin "4") (pinfunction "IN4_4") (pintype "passive"))
      (node (ref "USCQ12") (pin "16") (pinfunction "Q4_16") (pintype "tri_state"))
    )
    (net (code "525") (name "/SCQ_Q93") (class "Default")
      (node (ref "UDLDG12") (pin "5") (pinfunction "IN5_5") (pintype "passive"))
      (node (ref "USCQ12") (pin "15") (pinfunction "Q5_15") (pintype "tri_state"))
    )
    (net (code "526") (name "/SCQ_Q94") (class "Default")
      (node (ref "UDLDG12") (pin "6") (pinfunction "IN6_6") (pintype "passive"))
      (node (ref "USCQ12") (pin "14") (pinfunction "Q6_14") (pintype "tri_state"))
    )
    (net (code "527") (name "/SCQ_Q95") (class "Default")
      (node (ref "UDLDG12") (pin "7") (pinfunction "IN7_7") (pintype "passive"))
      (node (ref "USCQ12") (pin "13") (pinfunction "Q7_13") (pintype "tri_state"))
    )
    (net (code "528") (name "/SCQ_Q96") (class "Default")
      (node (ref "UDLDG12") (pin "8") (pinfunction "IN8_8") (pintype "passive"))
      (node (ref "USCQ12") (pin "12") (pinfunction "Q8_12") (pintype "tri_state"))
    )
    (net (code "529") (name "/SCQ_Q97") (class "Default")
      (node (ref "UDLDG13") (pin "1") (pinfunction "IN1_1") (pintype "passive"))
      (node (ref "USCQ13") (pin "19") (pinfunction "Q1_19") (pintype "tri_state"))
    )
    (net (code "530") (name "/SCQ_Q98") (class "Default")
      (node (ref "UDLDG13") (pin "2") (pinfunction "IN2_2") (pintype "passive"))
      (node (ref "USCQ13") (pin "18") (pinfunction "Q2_18") (pintype "tri_state"))
    )
    (net (code "531") (name "/SCQ_Q99") (class "Default")
      (node (ref "UDLDG13") (pin "3") (pinfunction "IN3_3") (pintype "passive"))
      (node (ref "USCQ13") (pin "17") (pinfunction "Q3_17") (pintype "tri_state"))
    )
    (net (code "532") (name "/SCQ_Q100") (class "Default")
      (node (ref "UDLDG13") (pin "4") (pinfunction "IN4_4") (pintype "passive"))
      (node (ref "USCQ13") (pin "16") (pinfunction "Q4_16") (pintype "tri_state"))
    )
    (net (code "533") (name "/SCQ_Q101") (class "Default")
      (node (ref "UDLDG13") (pin "5") (pinfunction "IN5_5") (pintype "passive"))
      (node (ref "USCQ13") (pin "15") (pinfunction "Q5_15") (pintype "tri_state"))
    )
    (net (code "534") (name "/SCQ_Q102") (class "Default")
      (node (ref "UDLDG13") (pin "6") (pinfunction "IN6_6") (pintype "passive"))
      (node (ref "USCQ13") (pin "14") (pinfunction "Q6_14") (pintype "tri_state"))
    )
    (net (code "535") (name "/SCQ_Q103") (class "Default")
      (node (ref "UDLDG13") (pin "7") (pinfunction "IN7_7") (pintype "passive"))
      (node (ref "USCQ13") (pin "13") (pinfunction "Q7_13") (pintype "tri_state"))
    )
    (net (code "536") (name "/SCQ_Q104") (class "Default")
      (node (ref "UDLDG13") (pin "8") (pinfunction "IN8_8") (pintype "passive"))
      (node (ref "USCQ13") (pin "12") (pinfunction "Q8_12") (pintype "tri_state"))
    )
    (net (code "537") (name "/SCQ_Q105") (class "Default")
      (node (ref "UDLDG14") (pin "1") (pinfunction "IN1_1") (pintype "passive"))
      (node (ref "USCQ14") (pin "19") (pinfunction "Q1_19") (pintype "tri_state"))
    )
    (net (code "538") (name "/SCQ_Q106") (class "Default")
      (node (ref "UDLDG14") (pin "2") (pinfunction "IN2_2") (pintype "passive"))
      (node (ref "USCQ14") (pin "18") (pinfunction "Q2_18") (pintype "tri_state"))
    )
    (net (code "539") (name "/SCQ_Q107") (class "Default")
      (node (ref "UDLDG14") (pin "3") (pinfunction "IN3_3") (pintype "passive"))
      (node (ref "USCQ14") (pin "17") (pinfunction "Q3_17") (pintype "tri_state"))
    )
    (net (code "540") (name "/SCQ_Q108") (class "Default")
      (node (ref "UDLDG14") (pin "4") (pinfunction "IN4_4") (pintype "passive"))
      (node (ref "USCQ14") (pin "16") (pinfunction "Q4_16") (pintype "tri_state"))
    )
    (net (code "541") (name "/SCQ_Q109") (class "Default")
      (node (ref "UDLDG14") (pin "5") (pinfunction "IN5_5") (pintype "passive"))
      (node (ref "USCQ14") (pin "15") (pinfunction "Q5_15") (pintype "tri_state"))
    )
    (net (code "542") (name "/SCQ_Q110") (class "Default")
      (node (ref "UDLDG14") (pin "6") (pinfunction "IN6_6") (pintype "passive"))
      (node (ref "USCQ14") (pin "14") (pinfunction "Q6_14") (pintype "tri_state"))
    )
    (net (code "543") (name "/SCQ_Q111") (class "Default")
      (node (ref "UDLDG14") (pin "7") (pinfunction "IN7_7") (pintype "passive"))
      (node (ref "USCQ14") (pin "13") (pinfunction "Q7_13") (pintype "tri_state"))
    )
    (net (code "544") (name "/SCQ_Q112") (class "Default")
      (node (ref "UDLDG14") (pin "8") (pinfunction "IN8_8") (pintype "passive"))
      (node (ref "USCQ14") (pin "12") (pinfunction "Q8_12") (pintype "tri_state"))
    )
    (net (code "545") (name "/SCQ_Q113") (class "Default")
      (node (ref "UDLDG15") (pin "1") (pinfunction "IN1_1") (pintype "passive"))
      (node (ref "USCQ15") (pin "19") (pinfunction "Q1_19") (pintype "tri_state"))
    )
    (net (code "546") (name "/SCQ_Q114") (class "Default")
      (node (ref "UDLDG15") (pin "2") (pinfunction "IN2_2") (pintype "passive"))
      (node (ref "USCQ15") (pin "18") (pinfunction "Q2_18") (pintype "tri_state"))
    )
    (net (code "547") (name "/SCQ_Q115") (class "Default")
      (node (ref "UDLDG15") (pin "3") (pinfunction "IN3_3") (pintype "passive"))
      (node (ref "USCQ15") (pin "17") (pinfunction "Q3_17") (pintype "tri_state"))
    )
    (net (code "548") (name "/SCQ_Q116") (class "Default")
      (node (ref "UDLDG15") (pin "4") (pinfunction "IN4_4") (pintype "passive"))
      (node (ref "USCQ15") (pin "16") (pinfunction "Q4_16") (pintype "tri_state"))
    )
    (net (code "549") (name "/SCQ_Q117") (class "Default")
      (node (ref "UDLDG15") (pin "5") (pinfunction "IN5_5") (pintype "passive"))
      (node (ref "USCQ15") (pin "15") (pinfunction "Q5_15") (pintype "tri_state"))
    )
    (net (code "550") (name "/SCQ_Q118") (class "Default")
      (node (ref "UDLDG15") (pin "6") (pinfunction "IN6_6") (pintype "passive"))
      (node (ref "USCQ15") (pin "14") (pinfunction "Q6_14") (pintype "tri_state"))
    )
    (net (code "551") (name "/SCQ_Q119") (class "Default")
      (node (ref "UDLDG15") (pin "7") (pinfunction "IN7_7") (pintype "passive"))
      (node (ref "USCQ15") (pin "13") (pinfunction "Q7_13") (pintype "tri_state"))
    )
    (net (code "552") (name "/SCQ_Q120") (class "Default")
      (node (ref "UDLDG15") (pin "8") (pinfunction "IN8_8") (pintype "passive"))
      (node (ref "USCQ15") (pin "12") (pinfunction "Q8_12") (pintype "tri_state"))
    )
    (net (code "553") (name "/SCQ_Q121") (class "Default")
      (node (ref "UDLDG16") (pin "1") (pinfunction "IN1_1") (pintype "passive"))
      (node (ref "USCQ16") (pin "19") (pinfunction "Q1_19") (pintype "tri_state"))
    )
    (net (code "554") (name "/SCQ_Q122") (class "Default")
      (node (ref "UDLDG16") (pin "2") (pinfunction "IN2_2") (pintype "passive"))
      (node (ref "USCQ16") (pin "18") (pinfunction "Q2_18") (pintype "tri_state"))
    )
    (net (code "555") (name "/SCQ_Q123") (class "Default")
      (node (ref "UDLDG16") (pin "3") (pinfunction "IN3_3") (pintype "passive"))
      (node (ref "USCQ16") (pin "17") (pinfunction "Q3_17") (pintype "tri_state"))
    )
    (net (code "556") (name "/SCQ_Q124") (class "Default")
      (node (ref "UDLDG16") (pin "4") (pinfunction "IN4_4") (pintype "passive"))
      (node (ref "USCQ16") (pin "16") (pinfunction "Q4_16") (pintype "tri_state"))
    )
    (net (code "557") (name "/SCQ_Q125") (class "Default")
      (node (ref "UDLDG16") (pin "5") (pinfunction "IN5_5") (pintype "passive"))
      (node (ref "USCQ16") (pin "15") (pinfunction "Q5_15") (pintype "tri_state"))
    )
    (net (code "558") (name "/SCQ_Q126") (class "Default")
      (node (ref "UDLDG16") (pin "6") (pinfunction "IN6_6") (pintype "passive"))
      (node (ref "USCQ16") (pin "14") (pinfunction "Q6_14") (pintype "tri_state"))
    )
    (net (code "559") (name "/SCQ_Q127") (class "Default")
      (node (ref "UDLDG16") (pin "7") (pinfunction "IN7_7") (pintype "passive"))
      (node (ref "USCQ16") (pin "13") (pinfunction "Q7_13") (pintype "tri_state"))
    )
    (net (code "560") (name "/SCQ_Q128") (class "Default")
      (node (ref "UDLDG16") (pin "8") (pinfunction "IN8_8") (pintype "passive"))
      (node (ref "USCQ16") (pin "12") (pinfunction "Q8_12") (pintype "tri_state"))
    )
    (net (code "561") (name "/SCQ_Q129") (class "Default")
      (node (ref "UDLDG17") (pin "1") (pinfunction "IN1_1") (pintype "passive"))
      (node (ref "USCQ17") (pin "19") (pinfunction "Q1_19") (pintype "tri_state"))
    )
    (net (code "562") (name "/SCQ_Q130") (class "Default")
      (node (ref "UDLDG17") (pin "2") (pinfunction "IN2_2") (pintype "passive"))
      (node (ref "USCQ17") (pin "18") (pinfunction "Q2_18") (pintype "tri_state"))
    )
    (net (code "563") (name "/SCQ_Q131") (class "Default")
      (node (ref "UDLDG17") (pin "3") (pinfunction "IN3_3") (pintype "passive"))
      (node (ref "USCQ17") (pin "17") (pinfunction "Q3_17") (pintype "tri_state"))
    )
    (net (code "564") (name "/SCQ_Q132") (class "Default")
      (node (ref "UDLDG17") (pin "4") (pinfunction "IN4_4") (pintype "passive"))
      (node (ref "USCQ17") (pin "16") (pinfunction "Q4_16") (pintype "tri_state"))
    )
    (net (code "565") (name "/SCQ_Q133") (class "Default")
      (node (ref "UDLDG17") (pin "5") (pinfunction "IN5_5") (pintype "passive"))
      (node (ref "USCQ17") (pin "15") (pinfunction "Q5_15") (pintype "tri_state"))
    )
    (net (code "566") (name "/SCQ_Q134") (class "Default")
      (node (ref "UDLDG17") (pin "6") (pinfunction "IN6_6") (pintype "passive"))
      (node (ref "USCQ17") (pin "14") (pinfunction "Q6_14") (pintype "tri_state"))
    )
    (net (code "567") (name "/SCQ_Q135") (class "Default")
      (node (ref "UDLDG17") (pin "7") (pinfunction "IN7_7") (pintype "passive"))
      (node (ref "USCQ17") (pin "13") (pinfunction "Q7_13") (pintype "tri_state"))
    )
    (net (code "568") (name "/SCQ_Q136") (class "Default")
      (node (ref "UDLDG17") (pin "8") (pinfunction "IN8_8") (pintype "passive"))
      (node (ref "USCQ17") (pin "12") (pinfunction "Q8_12") (pintype "tri_state"))
    )
    (net (code "569") (name "/SCQ_Q137") (class "Default")
      (node (ref "UDLDG18") (pin "1") (pinfunction "IN1_1") (pintype "passive"))
      (node (ref "USCQ18") (pin "19") (pinfunction "Q1_19") (pintype "tri_state"))
    )
    (net (code "570") (name "/SCQ_Q138") (class "Default")
      (node (ref "UDLDG18") (pin "2") (pinfunction "IN2_2") (pintype "passive"))
      (node (ref "USCQ18") (pin "18") (pinfunction "Q2_18") (pintype "tri_state"))
    )
    (net (code "571") (name "/SCQ_Q139") (class "Default")
      (node (ref "UDLDG18") (pin "3") (pinfunction "IN3_3") (pintype "passive"))
      (node (ref "USCQ18") (pin "17") (pinfunction "Q3_17") (pintype "tri_state"))
    )
    (net (code "572") (name "/SCQ_Q140") (class "Default")
      (node (ref "UDLDG18") (pin "4") (pinfunction "IN4_4") (pintype "passive"))
      (node (ref "USCQ18") (pin "16") (pinfunction "Q4_16") (pintype "tri_state"))
    )
    (net (code "573") (name "/SCQ_Q141") (class "Default")
      (node (ref "UDLDG18") (pin "5") (pinfunction "IN5_5") (pintype "passive"))
      (node (ref "USCQ18") (pin "15") (pinfunction "Q5_15") (pintype "tri_state"))
    )
    (net (code "574") (name "/SCQ_Q142") (class "Default")
      (node (ref "UDLDG18") (pin "6") (pinfunction "IN6_6") (pintype "passive"))
      (node (ref "USCQ18") (pin "14") (pinfunction "Q6_14") (pintype "tri_state"))
    )
    (net (code "575") (name "/SCQ_Q143") (class "Default")
      (node (ref "UDLDG18") (pin "7") (pinfunction "IN7_7") (pintype "passive"))
      (node (ref "USCQ18") (pin "13") (pinfunction "Q7_13") (pintype "tri_state"))
    )
    (net (code "576") (name "/SCQ_Q144") (class "Default")
      (node (ref "UDLDG18") (pin "8") (pinfunction "IN8_8") (pintype "passive"))
      (node (ref "USCQ18") (pin "12") (pinfunction "Q8_12") (pintype "tri_state"))
    )
    (net (code "577") (name "/SCQ_Q145") (class "Default")
      (node (ref "UDLDG19") (pin "1") (pinfunction "IN1_1") (pintype "passive"))
      (node (ref "USCQ19") (pin "19") (pinfunction "Q1_19") (pintype "tri_state"))
    )
    (net (code "578") (name "/SCQ_Q146") (class "Default")
      (node (ref "UDLDG19") (pin "2") (pinfunction "IN2_2") (pintype "passive"))
      (node (ref "USCQ19") (pin "18") (pinfunction "Q2_18") (pintype "tri_state"))
    )
    (net (code "579") (name "/SCQ_Q147") (class "Default")
      (node (ref "UDLDG19") (pin "3") (pinfunction "IN3_3") (pintype "passive"))
      (node (ref "USCQ19") (pin "17") (pinfunction "Q3_17") (pintype "tri_state"))
    )
    (net (code "580") (name "/SCQ_Q148") (class "Default")
      (node (ref "UDLDG19") (pin "4") (pinfunction "IN4_4") (pintype "passive"))
      (node (ref "USCQ19") (pin "16") (pinfunction "Q4_16") (pintype "tri_state"))
    )
    (net (code "581") (name "/SCQ_Q149") (class "Default")
      (node (ref "UDLDG19") (pin "5") (pinfunction "IN5_5") (pintype "passive"))
      (node (ref "USCQ19") (pin "15") (pinfunction "Q5_15") (pintype "tri_state"))
    )
    (net (code "582") (name "/SCQ_Q150") (class "Default")
      (node (ref "UDLDG19") (pin "6") (pinfunction "IN6_6") (pintype "passive"))
      (node (ref "USCQ19") (pin "14") (pinfunction "Q6_14") (pintype "tri_state"))
    )
    (net (code "583") (name "/SCQ_Q151") (class "Default")
      (node (ref "UDLDG19") (pin "7") (pinfunction "IN7_7") (pintype "passive"))
      (node (ref "USCQ19") (pin "13") (pinfunction "Q7_13") (pintype "tri_state"))
    )
    (net (code "584") (name "/SCQ_Q152") (class "Default")
      (node (ref "UDLDG19") (pin "8") (pinfunction "IN8_8") (pintype "passive"))
      (node (ref "USCQ19") (pin "12") (pinfunction "Q8_12") (pintype "tri_state"))
    )
    (net (code "585") (name "/SCQ_Q153") (class "Default")
      (node (ref "UDLDG20") (pin "1") (pinfunction "IN1_1") (pintype "passive"))
      (node (ref "USCQ20") (pin "19") (pinfunction "Q1_19") (pintype "tri_state"))
    )
    (net (code "586") (name "/SCQ_Q154") (class "Default")
      (node (ref "UDLDG20") (pin "2") (pinfunction "IN2_2") (pintype "passive"))
      (node (ref "USCQ20") (pin "18") (pinfunction "Q2_18") (pintype "tri_state"))
    )
    (net (code "587") (name "/SCQ_Q155") (class "Default")
      (node (ref "UDLDG20") (pin "3") (pinfunction "IN3_3") (pintype "passive"))
      (node (ref "USCQ20") (pin "17") (pinfunction "Q3_17") (pintype "tri_state"))
    )
    (net (code "588") (name "/SCQ_Q156") (class "Default")
      (node (ref "UDLDG20") (pin "4") (pinfunction "IN4_4") (pintype "passive"))
      (node (ref "USCQ20") (pin "16") (pinfunction "Q4_16") (pintype "tri_state"))
    )
    (net (code "589") (name "/SCQ_Q157") (class "Default")
      (node (ref "UDLDG20") (pin "5") (pinfunction "IN5_5") (pintype "passive"))
      (node (ref "USCQ20") (pin "15") (pinfunction "Q5_15") (pintype "tri_state"))
    )
    (net (code "590") (name "/SCQ_Q158") (class "Default")
      (node (ref "UDLDG20") (pin "6") (pinfunction "IN6_6") (pintype "passive"))
      (node (ref "USCQ20") (pin "14") (pinfunction "Q6_14") (pintype "tri_state"))
    )
    (net (code "591") (name "/SCQ_Q159") (class "Default")
      (node (ref "UDLDG20") (pin "7") (pinfunction "IN7_7") (pintype "passive"))
      (node (ref "USCQ20") (pin "13") (pinfunction "Q7_13") (pintype "tri_state"))
    )
    (net (code "592") (name "/SCQ_Q160") (class "Default")
      (node (ref "UDLDG20") (pin "8") (pinfunction "IN8_8") (pintype "passive"))
      (node (ref "USCQ20") (pin "12") (pinfunction "Q8_12") (pintype "tri_state"))
    )
    (net (code "593") (name "/SCQ_Q161") (class "Default")
      (node (ref "UDLDG21") (pin "1") (pinfunction "IN1_1") (pintype "passive"))
      (node (ref "USCQ21") (pin "19") (pinfunction "Q1_19") (pintype "tri_state"))
    )
    (net (code "594") (name "/SCQ_Q162") (class "Default")
      (node (ref "UDLDG21") (pin "2") (pinfunction "IN2_2") (pintype "passive"))
      (node (ref "USCQ21") (pin "18") (pinfunction "Q2_18") (pintype "tri_state"))
    )
    (net (code "595") (name "/SCQ_Q163") (class "Default")
      (node (ref "UDLDG21") (pin "3") (pinfunction "IN3_3") (pintype "passive"))
      (node (ref "USCQ21") (pin "17") (pinfunction "Q3_17") (pintype "tri_state"))
    )
    (net (code "596") (name "/SCQ_Q164") (class "Default")
      (node (ref "UDLDG21") (pin "4") (pinfunction "IN4_4") (pintype "passive"))
      (node (ref "USCQ21") (pin "16") (pinfunction "Q4_16") (pintype "tri_state"))
    )
    (net (code "597") (name "/SCQ_Q165") (class "Default")
      (node (ref "UDLDG21") (pin "5") (pinfunction "IN5_5") (pintype "passive"))
      (node (ref "USCQ21") (pin "15") (pinfunction "Q5_15") (pintype "tri_state"))
    )
    (net (code "598") (name "/SCQ_Q166") (class "Default")
      (node (ref "UDLDG21") (pin "6") (pinfunction "IN6_6") (pintype "passive"))
      (node (ref "USCQ21") (pin "14") (pinfunction "Q6_14") (pintype "tri_state"))
    )
    (net (code "599") (name "/SCQ_Q167") (class "Default")
      (node (ref "UDLDG21") (pin "7") (pinfunction "IN7_7") (pintype "passive"))
      (node (ref "USCQ21") (pin "13") (pinfunction "Q7_13") (pintype "tri_state"))
    )
    (net (code "600") (name "/SCQ_Q168") (class "Default")
      (node (ref "UDLDG21") (pin "8") (pinfunction "IN8_8") (pintype "passive"))
      (node (ref "USCQ21") (pin "12") (pinfunction "Q8_12") (pintype "tri_state"))
    )
    (net (code "601") (name "/SCQ_Q169") (class "Default")
      (node (ref "UDLDG22") (pin "1") (pinfunction "IN1_1") (pintype "passive"))
      (node (ref "USCQ22") (pin "19") (pinfunction "Q1_19") (pintype "tri_state"))
    )
    (net (code "602") (name "/SCQ_Q170") (class "Default")
      (node (ref "UDLDG22") (pin "2") (pinfunction "IN2_2") (pintype "passive"))
      (node (ref "USCQ22") (pin "18") (pinfunction "Q2_18") (pintype "tri_state"))
    )
    (net (code "603") (name "/SCQ_Q171") (class "Default")
      (node (ref "UDLDG22") (pin "3") (pinfunction "IN3_3") (pintype "passive"))
      (node (ref "USCQ22") (pin "17") (pinfunction "Q3_17") (pintype "tri_state"))
    )
    (net (code "604") (name "/SCQ_Q172") (class "Default")
      (node (ref "UDLDG22") (pin "4") (pinfunction "IN4_4") (pintype "passive"))
      (node (ref "USCQ22") (pin "16") (pinfunction "Q4_16") (pintype "tri_state"))
    )
    (net (code "605") (name "/SCQ_Q173") (class "Default")
      (node (ref "UDLDG22") (pin "5") (pinfunction "IN5_5") (pintype "passive"))
      (node (ref "USCQ22") (pin "15") (pinfunction "Q5_15") (pintype "tri_state"))
    )
    (net (code "606") (name "/SCQ_Q174") (class "Default")
      (node (ref "UDLDG22") (pin "6") (pinfunction "IN6_6") (pintype "passive"))
      (node (ref "USCQ22") (pin "14") (pinfunction "Q6_14") (pintype "tri_state"))
    )
    (net (code "607") (name "/SCQ_Q175") (class "Default")
      (node (ref "UDLDG22") (pin "7") (pinfunction "IN7_7") (pintype "passive"))
      (node (ref "USCQ22") (pin "13") (pinfunction "Q7_13") (pintype "tri_state"))
    )
    (net (code "608") (name "/SCQ_Q176") (class "Default")
      (node (ref "UDLDG22") (pin "8") (pinfunction "IN8_8") (pintype "passive"))
      (node (ref "USCQ22") (pin "12") (pinfunction "Q8_12") (pintype "tri_state"))
    )
    (net (code "609") (name "/SCQ_Q177") (class "Default")
      (node (ref "UDLDG23") (pin "1") (pinfunction "IN1_1") (pintype "passive"))
      (node (ref "USCQ23") (pin "19") (pinfunction "Q1_19") (pintype "tri_state"))
    )
    (net (code "610") (name "/SCQ_Q178") (class "Default")
      (node (ref "UDLDG23") (pin "2") (pinfunction "IN2_2") (pintype "passive"))
      (node (ref "USCQ23") (pin "18") (pinfunction "Q2_18") (pintype "tri_state"))
    )
    (net (code "611") (name "/SCQ_Q179") (class "Default")
      (node (ref "UDLDG23") (pin "3") (pinfunction "IN3_3") (pintype "passive"))
      (node (ref "USCQ23") (pin "17") (pinfunction "Q3_17") (pintype "tri_state"))
    )
    (net (code "612") (name "/SCQ_Q180") (class "Default")
      (node (ref "UDLDG23") (pin "4") (pinfunction "IN4_4") (pintype "passive"))
      (node (ref "USCQ23") (pin "16") (pinfunction "Q4_16") (pintype "tri_state"))
    )
    (net (code "613") (name "/SCQ_Q181") (class "Default")
      (node (ref "UDLDG23") (pin "5") (pinfunction "IN5_5") (pintype "passive"))
      (node (ref "USCQ23") (pin "15") (pinfunction "Q5_15") (pintype "tri_state"))
    )
    (net (code "614") (name "/SCQ_Q182") (class "Default")
      (node (ref "UDLDG23") (pin "6") (pinfunction "IN6_6") (pintype "passive"))
      (node (ref "USCQ23") (pin "14") (pinfunction "Q6_14") (pintype "tri_state"))
    )
    (net (code "615") (name "/SCQ_Q183") (class "Default")
      (node (ref "UDLDG23") (pin "7") (pinfunction "IN7_7") (pintype "passive"))
      (node (ref "USCQ23") (pin "13") (pinfunction "Q7_13") (pintype "tri_state"))
    )
    (net (code "616") (name "/SCQ_Q184") (class "Default")
      (node (ref "UDLDG23") (pin "8") (pinfunction "IN8_8") (pintype "passive"))
      (node (ref "USCQ23") (pin "12") (pinfunction "Q8_12") (pintype "tri_state"))
    )
    (net (code "617") (name "/SCQ_Q185") (class "Default")
      (node (ref "UDLDG24") (pin "1") (pinfunction "IN1_1") (pintype "passive"))
      (node (ref "USCQ24") (pin "19") (pinfunction "Q1_19") (pintype "tri_state"))
    )
    (net (code "618") (name "/SCQ_Q186") (class "Default")
      (node (ref "UDLDG24") (pin "2") (pinfunction "IN2_2") (pintype "passive"))
      (node (ref "USCQ24") (pin "18") (pinfunction "Q2_18") (pintype "tri_state"))
    )
    (net (code "619") (name "/SCQ_Q187") (class "Default")
      (node (ref "UDLDG24") (pin "3") (pinfunction "IN3_3") (pintype "passive"))
      (node (ref "USCQ24") (pin "17") (pinfunction "Q3_17") (pintype "tri_state"))
    )
    (net (code "620") (name "/SCQ_Q188") (class "Default")
      (node (ref "UDLDG24") (pin "4") (pinfunction "IN4_4") (pintype "passive"))
      (node (ref "USCQ24") (pin "16") (pinfunction "Q4_16") (pintype "tri_state"))
    )
    (net (code "621") (name "/SCQ_Q189") (class "Default")
      (node (ref "UDLDG24") (pin "5") (pinfunction "IN5_5") (pintype "passive"))
      (node (ref "USCQ24") (pin "15") (pinfunction "Q5_15") (pintype "tri_state"))
    )
    (net (code "622") (name "/SCQ_Q190") (class "Default")
      (node (ref "UDLDG24") (pin "6") (pinfunction "IN6_6") (pintype "passive"))
      (node (ref "USCQ24") (pin "14") (pinfunction "Q6_14") (pintype "tri_state"))
    )
    (net (code "623") (name "/SCQ_Q191") (class "Default")
      (node (ref "UDLDG24") (pin "7") (pinfunction "IN7_7") (pintype "passive"))
      (node (ref "USCQ24") (pin "13") (pinfunction "Q7_13") (pintype "tri_state"))
    )
    (net (code "624") (name "/SCQ_Q192") (class "Default")
      (node (ref "UDLDG24") (pin "8") (pinfunction "IN8_8") (pintype "passive"))
      (node (ref "USCQ24") (pin "12") (pinfunction "Q8_12") (pintype "tri_state"))
    )
    (net (code "625") (name "/SCQ_Q193") (class "Default")
      (node (ref "UDLDG25") (pin "1") (pinfunction "IN1_1") (pintype "passive"))
      (node (ref "USCQ25") (pin "19") (pinfunction "Q1_19") (pintype "tri_state"))
    )
    (net (code "626") (name "/SCQ_Q194") (class "Default")
      (node (ref "UDLDG25") (pin "2") (pinfunction "IN2_2") (pintype "passive"))
      (node (ref "USCQ25") (pin "18") (pinfunction "Q2_18") (pintype "tri_state"))
    )
    (net (code "627") (name "/SCQ_Q195") (class "Default")
      (node (ref "UDLDG25") (pin "3") (pinfunction "IN3_3") (pintype "passive"))
      (node (ref "USCQ25") (pin "17") (pinfunction "Q3_17") (pintype "tri_state"))
    )
    (net (code "628") (name "/SCQ_Q196") (class "Default")
      (node (ref "UDLDG25") (pin "4") (pinfunction "IN4_4") (pintype "passive"))
      (node (ref "USCQ25") (pin "16") (pinfunction "Q4_16") (pintype "tri_state"))
    )
    (net (code "629") (name "/SCQ_Q197") (class "Default")
      (node (ref "UDLDG25") (pin "5") (pinfunction "IN5_5") (pintype "passive"))
      (node (ref "USCQ25") (pin "15") (pinfunction "Q5_15") (pintype "tri_state"))
    )
    (net (code "630") (name "/SCQ_Q198") (class "Default")
      (node (ref "UDLDG25") (pin "6") (pinfunction "IN6_6") (pintype "passive"))
      (node (ref "USCQ25") (pin "14") (pinfunction "Q6_14") (pintype "tri_state"))
    )
    (net (code "631") (name "/SCQ_Q199") (class "Default")
      (node (ref "UDLDG25") (pin "7") (pinfunction "IN7_7") (pintype "passive"))
      (node (ref "USCQ25") (pin "13") (pinfunction "Q7_13") (pintype "tri_state"))
    )
    (net (code "632") (name "/SCQ_Q200") (class "Default")
      (node (ref "UDLDG25") (pin "8") (pinfunction "IN8_8") (pintype "passive"))
      (node (ref "USCQ25") (pin "12") (pinfunction "Q8_12") (pintype "tri_state"))
    )
    (net (code "633") (name "/SCQ_Q201") (class "Default")
      (node (ref "UDLDG26") (pin "1") (pinfunction "IN1_1") (pintype "passive"))
      (node (ref "USCQ26") (pin "19") (pinfunction "Q1_19") (pintype "tri_state"))
    )
    (net (code "634") (name "/SCQ_Q202") (class "Default")
      (node (ref "UDLDG26") (pin "2") (pinfunction "IN2_2") (pintype "passive"))
      (node (ref "USCQ26") (pin "18") (pinfunction "Q2_18") (pintype "tri_state"))
    )
    (net (code "635") (name "/SCQ_Q203") (class "Default")
      (node (ref "UDLDG26") (pin "3") (pinfunction "IN3_3") (pintype "passive"))
      (node (ref "USCQ26") (pin "17") (pinfunction "Q3_17") (pintype "tri_state"))
    )
    (net (code "636") (name "/SCQ_Q204") (class "Default")
      (node (ref "UDLDG26") (pin "4") (pinfunction "IN4_4") (pintype "passive"))
      (node (ref "USCQ26") (pin "16") (pinfunction "Q4_16") (pintype "tri_state"))
    )
    (net (code "637") (name "/SCQ_Q205") (class "Default")
      (node (ref "UDLDG26") (pin "5") (pinfunction "IN5_5") (pintype "passive"))
      (node (ref "USCQ26") (pin "15") (pinfunction "Q5_15") (pintype "tri_state"))
    )
    (net (code "638") (name "/SCQ_Q206") (class "Default")
      (node (ref "UDLDG26") (pin "6") (pinfunction "IN6_6") (pintype "passive"))
      (node (ref "USCQ26") (pin "14") (pinfunction "Q6_14") (pintype "tri_state"))
    )
    (net (code "639") (name "/SCQ_Q207") (class "Default")
      (node (ref "UDLDG26") (pin "7") (pinfunction "IN7_7") (pintype "passive"))
      (node (ref "USCQ26") (pin "13") (pinfunction "Q7_13") (pintype "tri_state"))
    )
    (net (code "640") (name "/SCQ_Q208") (class "Default")
      (node (ref "UDLDG26") (pin "8") (pinfunction "IN8_8") (pintype "passive"))
      (node (ref "USCQ26") (pin "12") (pinfunction "Q8_12") (pintype "tri_state"))
    )
    (net (code "641") (name "/SCQ_Q209") (class "Default")
      (node (ref "UDLDG27") (pin "1") (pinfunction "IN1_1") (pintype "passive"))
      (node (ref "USCQ27") (pin "19") (pinfunction "Q1_19") (pintype "tri_state"))
    )
    (net (code "642") (name "/SCQ_Q210") (class "Default")
      (node (ref "UDLDG27") (pin "2") (pinfunction "IN2_2") (pintype "passive"))
      (node (ref "USCQ27") (pin "18") (pinfunction "Q2_18") (pintype "tri_state"))
    )
    (net (code "643") (name "/SCQ_Q211") (class "Default")
      (node (ref "UDLDG27") (pin "3") (pinfunction "IN3_3") (pintype "passive"))
      (node (ref "USCQ27") (pin "17") (pinfunction "Q3_17") (pintype "tri_state"))
    )
    (net (code "644") (name "/SCQ_Q212") (class "Default")
      (node (ref "UDLDG27") (pin "4") (pinfunction "IN4_4") (pintype "passive"))
      (node (ref "USCQ27") (pin "16") (pinfunction "Q4_16") (pintype "tri_state"))
    )
    (net (code "645") (name "/SCQ_Q213") (class "Default")
      (node (ref "UDLDG27") (pin "5") (pinfunction "IN5_5") (pintype "passive"))
      (node (ref "USCQ27") (pin "15") (pinfunction "Q5_15") (pintype "tri_state"))
    )
    (net (code "646") (name "/SCQ_Q214") (class "Default")
      (node (ref "UDLDG27") (pin "6") (pinfunction "IN6_6") (pintype "passive"))
      (node (ref "USCQ27") (pin "14") (pinfunction "Q6_14") (pintype "tri_state"))
    )
    (net (code "647") (name "/SCQ_Q215") (class "Default")
      (node (ref "UDLDG27") (pin "7") (pinfunction "IN7_7") (pintype "passive"))
      (node (ref "USCQ27") (pin "13") (pinfunction "Q7_13") (pintype "tri_state"))
    )
    (net (code "648") (name "/SCQ_Q216") (class "Default")
      (node (ref "UDLDG27") (pin "8") (pinfunction "IN8_8") (pintype "passive"))
      (node (ref "USCQ27") (pin "12") (pinfunction "Q8_12") (pintype "tri_state"))
    )
    (net (code "649") (name "/SCQ_Q217") (class "Default")
      (node (ref "UDLDG28") (pin "1") (pinfunction "IN1_1") (pintype "passive"))
      (node (ref "USCQ28") (pin "19") (pinfunction "Q1_19") (pintype "tri_state"))
    )
    (net (code "650") (name "/SCQ_Q218") (class "Default")
      (node (ref "UDLDG28") (pin "2") (pinfunction "IN2_2") (pintype "passive"))
      (node (ref "USCQ28") (pin "18") (pinfunction "Q2_18") (pintype "tri_state"))
    )
    (net (code "651") (name "/SCQ_Q219") (class "Default")
      (node (ref "UDLDG28") (pin "3") (pinfunction "IN3_3") (pintype "passive"))
      (node (ref "USCQ28") (pin "17") (pinfunction "Q3_17") (pintype "tri_state"))
    )
    (net (code "652") (name "/SCQ_Q220") (class "Default")
      (node (ref "UDLDG28") (pin "4") (pinfunction "IN4_4") (pintype "passive"))
      (node (ref "USCQ28") (pin "16") (pinfunction "Q4_16") (pintype "tri_state"))
    )
    (net (code "653") (name "/SCQ_Q221") (class "Default")
      (node (ref "UDLDG28") (pin "5") (pinfunction "IN5_5") (pintype "passive"))
      (node (ref "USCQ28") (pin "15") (pinfunction "Q5_15") (pintype "tri_state"))
    )
    (net (code "654") (name "/SCQ_Q222") (class "Default")
      (node (ref "UDLDG28") (pin "6") (pinfunction "IN6_6") (pintype "passive"))
      (node (ref "USCQ28") (pin "14") (pinfunction "Q6_14") (pintype "tri_state"))
    )
    (net (code "655") (name "/SCQ_Q223") (class "Default")
      (node (ref "UDLDG28") (pin "7") (pinfunction "IN7_7") (pintype "passive"))
      (node (ref "USCQ28") (pin "13") (pinfunction "Q7_13") (pintype "tri_state"))
    )
    (net (code "656") (name "/SCQ_Q224") (class "Default")
      (node (ref "UDLDG28") (pin "8") (pinfunction "IN8_8") (pintype "passive"))
      (node (ref "USCQ28") (pin "12") (pinfunction "Q8_12") (pintype "tri_state"))
    )
    (net (code "657") (name "/SCQ_Q225") (class "Default")
      (node (ref "UDLDG29") (pin "1") (pinfunction "IN1_1") (pintype "passive"))
      (node (ref "USCQ29") (pin "19") (pinfunction "Q1_19") (pintype "tri_state"))
    )
    (net (code "658") (name "/SCQ_Q226") (class "Default")
      (node (ref "UDLDG29") (pin "2") (pinfunction "IN2_2") (pintype "passive"))
      (node (ref "USCQ29") (pin "18") (pinfunction "Q2_18") (pintype "tri_state"))
    )
    (net (code "659") (name "/SCQ_Q227") (class "Default")
      (node (ref "UDLDG29") (pin "3") (pinfunction "IN3_3") (pintype "passive"))
      (node (ref "USCQ29") (pin "17") (pinfunction "Q3_17") (pintype "tri_state"))
    )
    (net (code "660") (name "/SCQ_Q228") (class "Default")
      (node (ref "UDLDG29") (pin "4") (pinfunction "IN4_4") (pintype "passive"))
      (node (ref "USCQ29") (pin "16") (pinfunction "Q4_16") (pintype "tri_state"))
    )
    (net (code "661") (name "/SCQ_Q229") (class "Default")
      (node (ref "UDLDG29") (pin "5") (pinfunction "IN5_5") (pintype "passive"))
      (node (ref "USCQ29") (pin "15") (pinfunction "Q5_15") (pintype "tri_state"))
    )
    (net (code "662") (name "/SCQ_Q230") (class "Default")
      (node (ref "UDLDG29") (pin "6") (pinfunction "IN6_6") (pintype "passive"))
      (node (ref "USCQ29") (pin "14") (pinfunction "Q6_14") (pintype "tri_state"))
    )
    (net (code "663") (name "/SCQ_Q231") (class "Default")
      (node (ref "UDLDG29") (pin "7") (pinfunction "IN7_7") (pintype "passive"))
      (node (ref "USCQ29") (pin "13") (pinfunction "Q7_13") (pintype "tri_state"))
    )
    (net (code "664") (name "/SCQ_Q232") (class "Default")
      (node (ref "UDLDG29") (pin "8") (pinfunction "IN8_8") (pintype "passive"))
      (node (ref "USCQ29") (pin "12") (pinfunction "Q8_12") (pintype "tri_state"))
    )
    (net (code "665") (name "/SCQ_Q233") (class "Default")
      (node (ref "UDLDG30") (pin "1") (pinfunction "IN1_1") (pintype "passive"))
      (node (ref "USCQ30") (pin "19") (pinfunction "Q1_19") (pintype "tri_state"))
    )
    (net (code "666") (name "/SCQ_Q234") (class "Default")
      (node (ref "UDLDG30") (pin "2") (pinfunction "IN2_2") (pintype "passive"))
      (node (ref "USCQ30") (pin "18") (pinfunction "Q2_18") (pintype "tri_state"))
    )
    (net (code "667") (name "/SCQ_Q235") (class "Default")
      (node (ref "UDLDG30") (pin "3") (pinfunction "IN3_3") (pintype "passive"))
      (node (ref "USCQ30") (pin "17") (pinfunction "Q3_17") (pintype "tri_state"))
    )
    (net (code "668") (name "/SCQ_Q236") (class "Default")
      (node (ref "UDLDG30") (pin "4") (pinfunction "IN4_4") (pintype "passive"))
      (node (ref "USCQ30") (pin "16") (pinfunction "Q4_16") (pintype "tri_state"))
    )
    (net (code "669") (name "/SCQ_Q237") (class "Default")
      (node (ref "UDLDG30") (pin "5") (pinfunction "IN5_5") (pintype "passive"))
      (node (ref "USCQ30") (pin "15") (pinfunction "Q5_15") (pintype "tri_state"))
    )
    (net (code "670") (name "/SCQ_Q238") (class "Default")
      (node (ref "UDLDG30") (pin "6") (pinfunction "IN6_6") (pintype "passive"))
      (node (ref "USCQ30") (pin "14") (pinfunction "Q6_14") (pintype "tri_state"))
    )
    (net (code "671") (name "/SCQ_Q239") (class "Default")
      (node (ref "UDLDG30") (pin "7") (pinfunction "IN7_7") (pintype "passive"))
      (node (ref "USCQ30") (pin "13") (pinfunction "Q7_13") (pintype "tri_state"))
    )
    (net (code "672") (name "/SCQ_Q240") (class "Default")
      (node (ref "UDLDG30") (pin "8") (pinfunction "IN8_8") (pintype "passive"))
      (node (ref "USCQ30") (pin "12") (pinfunction "Q8_12") (pintype "tri_state"))
    )
    (net (code "673") (name "/SDIO_CK") (class "Default")
      (node (ref "J1") (pin "5") (pinfunction "CLK/SCLK_5") (pintype "passive"))
      (node (ref "U5") (pin "163") (pinfunction "PC12/SPI3_MOSI/I2S3_SD/USART3_CK/UART5_TX/SDIO_CK/DCMI_D9_163") (pintype "passive"))
    )
    (net (code "674") (name "/SDIO_CMD") (class "Default")
      (node (ref "J1") (pin "2") (pinfunction "CMD/DI_2") (pintype "passive"))
      (node (ref "R10") (pin "1") (pinfunction "1_1") (pintype "passive"))
      (node (ref "U5") (pin "166") (pinfunction "PD2/TIM3_ETR/UART5_RX/SDIO_CMD/DCMI_D11_166") (pintype "passive"))
    )
    (net (code "675") (name "/SDIO_D0") (class "Default")
      (node (ref "J1") (pin "7") (pinfunction "DAT0/DO_7") (pintype "passive"))
      (node (ref "R11") (pin "1") (pinfunction "1_1") (pintype "passive"))
      (node (ref "U5") (pin "140") (pinfunction "PC8/TIM3_CH3/TIM8_CH3/USART6_CK/SDIO_D0/DCMI_D2_140") (pintype "passive"))
    )
    (net (code "676") (name "/SDIO_D1") (class "Default")
      (node (ref "J1") (pin "8") (pinfunction "DAT1_8") (pintype "passive"))
      (node (ref "R12") (pin "1") (pinfunction "1_1") (pintype "passive"))
      (node (ref "U5") (pin "141") (pinfunction "PC9/MCO2/TIM3_CH4/TIM8_CH4/I2C3_SDA/I2S_CKIN/SDIO_D1/DCMI_D3_141") (pintype "passive"))
    )
    (net (code "677") (name "/SDIO_D2") (class "Default")
      (node (ref "J1") (pin "9") (pinfunction "DAT2_9") (pintype "passive"))
      (node (ref "R8") (pin "1") (pinfunction "1_1") (pintype "passive"))
      (node (ref "U5") (pin "161") (pinfunction "PC10/SPI3_SCK/I2S3_CK/USART3_TX/UART4_TX/SDIO_D2/_DCMI_D8/LCD_R2_161") (pintype "passive"))
    )
    (net (code "678") (name "/SDIO_D3") (class "Default")
      (node (ref "J1") (pin "1") (pinfunction "CD/DAT3/CS_1") (pintype "passive"))
      (node (ref "R9") (pin "1") (pinfunction "1_1") (pintype "passive"))
      (node (ref "U5") (pin "162") (pinfunction "PC11/I2S3ext_SD/SPI3_MISO/USART3_RX/UART4_RX/SDIO_D3/DCMI_D4_162") (pintype "passive"))
    )
    (net (code "680") (name "/SPI5_MISO") (class "Default")
      (node (ref "U5") (pin "29") (pinfunction "PF8/SPI5_MISO/SAI1_SCK_B/TIM13_CH1/FMC_NIOWR_29") (pintype "passive"))
      (node (ref "U7") (pin "2") (pinfunction "SO(IO1)_2") (pintype "passive"))
    )
    (net (code "681") (name "/SPI5_MOSI") (class "Default")
      (node (ref "U5") (pin "30") (pinfunction "PF9/SPI5_MOSI/_SAI1_FS_B/_TIM14_CH1/FMC_CD_30") (pintype "passive"))
      (node (ref "U7") (pin "5") (pinfunction "SI(IO0)_5") (pintype "power_in"))
    )
    (net (code "682") (name "/SPI5_SCK") (class "Default")
      (node (ref "U5") (pin "28") (pinfunction "PF7/TIM11_CH1/SPI5_SCK/SAI1_MCLK_B/UART7_Tx/FMC_NREG_28") (pintype "passive"))
      (node (ref "U7") (pin "6") (pinfunction "CLK_6") (pintype "passive"))
    )
    (net (code "683") (name "/SPI_CLK") (class "Default")
      (node (ref "U4") (pin "42") (pinfunction "SPI_CLK_42") (pintype "passive"))
    )
    (net (code "684") (name "/SPI_CS") (class "Default")
      (node (ref "R14") (pin "2") (pinfunction "2_2") (pintype "passive"))
      (node (ref "U4") (pin "43") (pinfunction "SPI_SSEL_43") (pintype "passive"))
    )
    (net (code "685") (name "/SPI_MISO") (class "Default")
      (node (ref "U4") (pin "45") (pinfunction "SPI_SO_45") (pintype "passive"))
    )
    (net (code "686") (name "/SPI_MOSI") (class "Default")
      (node (ref "U4") (pin "44") (pinfunction "SPI_SI_44") (pintype "passive"))
    )
    (net (code "687") (name "/SPKL") (class "Default")
      (node (ref "J2") (pin "2") (pinfunction "2_2") (pintype "passive"))
      (node (ref "R18") (pin "2") (pinfunction "2_2") (pintype "passive"))
      (node (ref "U6") (pin "5") (pinfunction "VO1_5") (pintype "passive"))
    )
    (net (code "688") (name "/SPKN") (class "Default")
      (node (ref "J2") (pin "1") (pinfunction "1_1") (pintype "passive"))
      (node (ref "U6") (pin "8") (pinfunction "VO2_8") (pintype "passive"))
    )
    (net (code "689") (name "/TP_CS") (class "Default")
      (node (ref "PLCD1") (pin "35") (pinfunction "35_35") (pintype "passive"))
      (node (ref "U5") (pin "180") (pinfunction "PG11/ETH_MII_TX_EN/ETH_R__MII_TX_EN/_FMC_NCE4_2/_DCMI_D3/__LCD_B3_180") (pintype "passive"))
    )
    (net (code "690") (name "/TP_MISO") (class "Default")
      (node (ref "PLCD1") (pin "37") (pinfunction "37_37") (pintype "passive"))
      (node (ref "U5") (pin "181") (pinfunction "PG12/SPI6_MISO/_USART6_RTS/_LCD_B4/__FMC_NE4/LCD_B1_181") (pintype "passive"))
    )
    (net (code "691") (name "/TP_MOSI") (class "Default")
      (node (ref "PLCD1") (pin "36") (pinfunction "36_36") (pintype "passive"))
      (node (ref "U5") (pin "183") (pinfunction "PG14/SPI6_MOSI/_USART6_TX/__ETH_MII_TXD1/ETH_RMI__I_TXD1/FMC_A25_183") (pintype "passive"))
    )
    (net (code "692") (name "/TP_PEN") (class "Default")
      (node (ref "PLCD1") (pin "39") (pinfunction "39_39") (pintype "passive"))
      (node (ref "U5") (pin "46") (pinfunction "PH2/ETH_MII_CRS/FMC_SDCKE0/_LCD_R0_46") (pintype "passive"))
    )
    (net (code "693") (name "/TP_SCK") (class "Default")
      (node (ref "PLCD1") (pin "38") (pinfunction "38_38") (pintype "passive"))
      (node (ref "U5") (pin "182") (pinfunction "PG13/SPI6_SCK/__USART6_CTS/_ETH_MII_TXD0/ETH_RMI__I_TXD0/FMC_A24_182") (pintype "passive"))
    )
    (net (code "694") (name "/USART1_RX") (class "Default")
      (node (ref "U5") (pin "144") (pinfunction "PA10/TIM1_CH3/USART1_RX/OTG_FS_ID/DCMI_D1_144") (pintype "passive"))
      (node (ref "U9") (pin "2") (pinfunction "TXD_2") (pintype "passive"))
    )
    (net (code "695") (name "/USART1_TX") (class "Default")
      (node (ref "U5") (pin "143") (pinfunction "PA9/TIM1_CH2/_I2C3_SMBA/USART1_TX/DCMI_D0_143") (pintype "passive"))
      (node (ref "U9") (pin "3") (pinfunction "RXD_3") (pintype "passive"))
    )
    (net (code "696") (name "/USART2_RX") (class "Default")
      (node (ref "U5") (pin "50") (pinfunction "PA3/TIM2_CH4/_TIM5_CH4/TIM9_CH2/USART2_RX/OTG_HS_ULPI_D0/_ETH_MII_COL/LCD_B5_50") (pintype "passive"))
      (node (ref "WK1") (pin "2") (pinfunction "2_2") (pintype "passive"))
    )
    (net (code "697") (name "/USART2_TX") (class "Default")
      (node (ref "U5") (pin "45") (pinfunction "PA2/USART2_TX/ETH_MDIO/ADC_IN2_45") (pintype "passive"))
      (node (ref "WK1") (pin "1") (pinfunction "1_1") (pintype "passive"))
    )
    (net (code "703") (name "/VREF") (class "Default")
      (node (ref "C36") (pin "1") (pinfunction "1_1") (pintype "passive"))
      (node (ref "U4") (pin "18") (pinfunction "VREF_18") (pintype "passive"))
    )
    (net (code "704") (name "/WCLOCKRST") (class "Default")
      (node (ref "DS1") (pin "5") (pinfunction "~{RST}_5") (pintype "passive"))
      (node (ref "U5") (pin "198") (pinfunction "PB8/TIM4_CH3/TIM10_CH1/I2C1_SCL/CAN1_RX/_ETH_MII_TXD3/SDIO_D4/DCMI_D6_198") (pintype "passive"))
    )
    (net (code "705") (name "/WCLOCKSCL") (class "Default")
      (node (ref "DS1") (pin "7") (pinfunction "SCLK_7") (pintype "passive"))
      (node (ref "U5") (pin "195") (pinfunction "PB6/TIM4_CH1/I2C1_SCL/USART1_TX/CAN2_TX/FMC_SDNE1/DCMI_D5_195") (pintype "passive"))
    )
    (net (code "706") (name "/WCLOCKSDA") (class "Default")
      (node (ref "DS1") (pin "6") (pinfunction "I/O_6") (pintype "passive"))
      (node (ref "U5") (pin "196") (pinfunction "PB7/TIM4_CH2/_I2C1_SDA/USART1_RX/FMC_NL/DCMI_VSYNC_196") (pintype "passive"))
    )
    (net (code "707") (name "/XFS_RST") (class "Default")
      (node (ref "C40") (pin "1") (pinfunction "1_1") (pintype "passive"))
      (node (ref "R24") (pin "2") (pinfunction "2_2") (pintype "passive"))
      (node (ref "U4") (pin "28") (pinfunction "RESET_28") (pintype "passive"))
    )
    (net (code "708") (name "/ZDIAN") (class "Default")
      (node (ref "U5") (pin "61") (pinfunction "PB0/TIM1_CH2N/TIM3_CH3/TIM8_CH2N/_LCD_R3/OTG_HS_ULPI_D1/ETH_MII_RXD2_61") (pintype "passive"))
    )
    (net (code "709") (name "/ZFENG") (class "Default")
      (node (ref "U5") (pin "44") (pinfunction "PA1/ETH_MII_RX_CLK/ETH_RMII_REF_CLK/ADC123_IN1_44") (pintype "passive"))
    )
    (net (code "710") (name "/speed") (class "Default")
      (node (ref "U5") (pin "62") (pinfunction "PB1/TIM1_CH3N/TIM3_CH4/TIM8_CH3N/LCD_R6/OTG_HS_ULPI_D2/ETH_MII_RXD3_62") (pintype "passive"))
    )
    (net (code "711") (name "CPU-VDDA") (class "Default")
      (node (ref "C17") (pin "2") (pinfunction "2_2") (pintype "passive"))
      (node (ref "C18") (pin "2") (pinfunction "2_2") (pintype "passive"))
      (node (ref "FB6") (pin "2") (pinfunction "2_2") (pintype "passive"))
      (node (ref "U5") (pin "42") (pinfunction "VDDA_42") (pintype "passive"))
    )
    (net (code "712") (name "CPU-VSSA") (class "Default")
      (node (ref "C17") (pin "1") (pinfunction "1_1") (pintype "passive"))
      (node (ref "C18") (pin "1") (pinfunction "1_1") (pintype "passive"))
      (node (ref "FB7") (pin "2") (pinfunction "2_2") (pintype "passive"))
      (node (ref "U5") (pin "40") (pinfunction "VSSA_40") (pintype "passive"))
    )
    (net (code "713") (name "GND") (class "Default")
      (node (ref "*R2") (pin "1") (pintype "passive"))
      (node (ref "BOOT") (pin "5") (pinfunction "5_5") (pintype "passive"))
      (node (ref "BOOT") (pin "6") (pinfunction "6_6") (pintype "passive"))
      (node (ref "BT1") (pin "2") (pinfunction "2_2") (pintype "passive"))
      (node (ref "C1") (pin "1") (pinfunction "1_1") (pintype "passive"))
      (node (ref "C10") (pin "1") (pinfunction "1_1") (pintype "passive"))
      (node (ref "C11") (pin "1") (pinfunction "1_1") (pintype "passive"))
      (node (ref "C12") (pin "1") (pinfunction "1_1") (pintype "passive"))
      (node (ref "C13") (pin "1") (pinfunction "1_1") (pintype "passive"))
      (node (ref "C14") (pin "1") (pinfunction "1_1") (pintype "passive"))
      (node (ref "C15") (pin "1") (pinfunction "1_1") (pintype "passive"))
      (node (ref "C16") (pin "1") (pinfunction "1_1") (pintype "passive"))
      (node (ref "C19") (pin "1") (pinfunction "1_1") (pintype "passive"))
      (node (ref "C2") (pin "1") (pinfunction "1_1") (pintype "passive"))
      (node (ref "C20") (pin "1") (pinfunction "1_1") (pintype "passive"))
      (node (ref "C21") (pin "2") (pinfunction "2_2") (pintype "passive"))
      (node (ref "C22") (pin "1") (pinfunction "1_1") (pintype "passive"))
      (node (ref "C23") (pin "2") (pinfunction "2_2") (pintype "passive"))
      (node (ref "C24") (pin "1") (pinfunction "1_1") (pintype "passive"))
      (node (ref "C25") (pin "2") (pinfunction "2_2") (pintype "passive"))
      (node (ref "C26") (pin "2") (pinfunction "2_2") (pintype "passive"))
      (node (ref "C27") (pin "2") (pinfunction "2_2") (pintype "passive"))
      (node (ref "C28") (pin "1") (pinfunction "1_1") (pintype "passive"))
      (node (ref "C3") (pin "1") (pinfunction "1_1") (pintype "passive"))
      (node (ref "C30") (pin "1") (pinfunction "1_1") (pintype "passive"))
      (node (ref "C32") (pin "1") (pintype "passive"))
      (node (ref "C33") (pin "2") (pintype "passive"))
      (node (ref "C34") (pin "2") (pinfunction "2_2") (pintype "passive"))
      (node (ref "C35") (pin "2") (pinfunction "2_2") (pintype "passive"))
      (node (ref "C36") (pin "2") (pinfunction "2_2") (pintype "passive"))
      (node (ref "C37") (pin "2") (pinfunction "2_2") (pintype "passive"))
      (node (ref "C38") (pin "2") (pinfunction "2_2") (pintype "passive"))
      (node (ref "C39") (pin "2") (pinfunction "2_2") (pintype "passive"))
      (node (ref "C4") (pin "1") (pinfunction "1_1") (pintype "passive"))
      (node (ref "C40") (pin "2") (pinfunction "2_2") (pintype "passive"))
      (node (ref "C41") (pin "1") (pinfunction "1_1") (pintype "passive"))
      (node (ref "C42") (pin "2") (pinfunction "2_2") (pintype "passive"))
      (node (ref "C43") (pin "1") (pinfunction "1_1") (pintype "passive"))
      (node (ref "C44") (pin "1") (pinfunction "1_1") (pintype "passive"))
      (node (ref "C45") (pin "1") (pinfunction "1_1") (pintype "passive"))
      (node (ref "C46") (pin "1") (pinfunction "1_1") (pintype "passive"))
      (node (ref "C47") (pin "2") (pinfunction "2_2") (pintype "passive"))
      (node (ref "C48") (pin "1") (pinfunction "1_1") (pintype "passive"))
      (node (ref "C49") (pin "1") (pinfunction "1_1") (pintype "passive"))
      (node (ref "C5") (pin "1") (pintype "passive"))
      (node (ref "C50") (pin "2") (pinfunction "2_2") (pintype "passive"))
      (node (ref "C51") (pin "1") (pinfunction "1_1") (pintype "passive"))
      (node (ref "C52") (pin "1") (pinfunction "1_1") (pintype "passive"))
      (node (ref "C53") (pin "1") (pinfunction "1_1") (pintype "passive"))
      (node (ref "C54") (pin "1") (pinfunction "1_1") (pintype "passive"))
      (node (ref "C55") (pin "1") (pinfunction "1_1") (pintype "passive"))
      (node (ref "C56") (pin "1") (pinfunction "1_1") (pintype "passive"))
      (node (ref "C57") (pin "1") (pinfunction "1_1") (pintype "passive"))
      (node (ref "C58") (pin "1") (pinfunction "1_1") (pintype "passive"))
      (node (ref "C59") (pin "1") (pinfunction "1_1") (pintype "passive"))
      (node (ref "C6") (pin "1") (pinfunction "1_1") (pintype "passive"))
      (node (ref "C60") (pin "1") (pinfunction "1_1") (pintype "passive"))
      (node (ref "C61") (pin "1") (pinfunction "1_1") (pintype "passive"))
      (node (ref "C62") (pin "1") (pinfunction "1_1") (pintype "passive"))
      (node (ref "C63") (pin "1") (pinfunction "1_1") (pintype "passive"))
      (node (ref "C64") (pin "1") (pinfunction "1_1") (pintype "passive"))
      (node (ref "C65") (pin "1") (pinfunction "1_1") (pintype "passive"))
      (node (ref "C66") (pin "1") (pinfunction "1_1") (pintype "passive"))
      (node (ref "C67") (pin "1") (pinfunction "1_1") (pintype "passive"))
      (node (ref "C69") (pin "2") (pinfunction "2_2") (pintype "passive"))
      (node (ref "C7") (pin "1") (pinfunction "1_1") (pintype "passive"))
      (node (ref "C70") (pin "2") (pinfunction "2_2") (pintype "passive"))
      (node (ref "C71") (pin "1") (pinfunction "1_1") (pintype "passive"))
      (node (ref "C72") (pin "2") (pinfunction "2_2") (pintype "passive"))
      (node (ref "C73") (pin "2") (pinfunction "2_2") (pintype "passive"))
      (node (ref "C75") (pin "2") (pinfunction "2_2") (pintype "passive"))
      (node (ref "C76") (pin "1") (pinfunction "1_1") (pintype "passive"))
      (node (ref "C77") (pin "2") (pinfunction "2_2") (pintype "passive"))
      (node (ref "C78") (pin "2") (pintype "passive"))
      (node (ref "C79") (pin "2") (pintype "passive"))
      (node (ref "C8") (pin "1") (pinfunction "1_1") (pintype "passive"))
      (node (ref "C80") (pin "1") (pintype "passive"))
      (node (ref "C81") (pin "1") (pintype "passive"))
      (node (ref "C82") (pin "1") (pintype "passive"))
      (node (ref "C83") (pin "1") (pintype "passive"))
      (node (ref "C9") (pin "1") (pinfunction "1_1") (pintype "passive"))
      (node (ref "CA1") (pin "2") (pinfunction "2_2") (pintype "passive"))
      (node (ref "CA2") (pin "2") (pinfunction "2_2") (pintype "passive"))
      (node (ref "CD1") (pin "1") (pinfunction "1_1") (pintype "passive"))
      (node (ref "CD2") (pin "1") (pinfunction "1_1") (pintype "passive"))
      (node (ref "D18") (pin "2") (pinfunction "K_2") (pintype "passive"))
      (node (ref "D2") (pin "1") (pinfunction "A_1") (pintype "passive"))
      (node (ref "D22") (pin "2") (pinfunction "K_2") (pintype "passive"))
      (node (ref "D23") (pin "2") (pinfunction "K_2") (pintype "passive"))
      (node (ref "D24") (pin "2") (pinfunction "K_2") (pintype "passive"))
      (node (ref "D3") (pin "1") (pinfunction "A_1") (pintype "passive"))
      (node (ref "DC1") (pin "2") (pinfunction "2_2") (pintype "passive"))
      (node (ref "DS1") (pin "4") (pinfunction "GND_4") (pintype "passive"))
      (node (ref "FB7") (pin "1") (pinfunction "1_1") (pintype "passive"))
      (node (ref "FB9") (pin "1") (pinfunction "1_1") (pintype "passive"))
      (node (ref "J1") (pin "3") (pinfunction "VSS1_3") (pintype "passive"))
      (node (ref "J1") (pin "6") (pinfunction "VSS2_6") (pintype "passive"))
      (node (ref "K1") (pin "1") (pinfunction "1_1") (pintype "passive"))
      (node (ref "K2") (pin "1") (pinfunction "1_1") (pintype "passive"))
      (node (ref "K3") (pin "1") (pinfunction "1_1") (pintype "passive"))
      (node (ref "K4") (pin "1") (pinfunction "1_1") (pintype "passive"))
      (node (ref "K5") (pin "1") (pinfunction "1_1") (pintype "passive"))
      (node (ref "K6") (pin "1") (pinfunction "1_1") (pintype "passive"))
      (node (ref "K7") (pin "2") (pinfunction "2_2") (pintype "passive"))
      (node (ref "P1") (pin "2") (pinfunction "2_2") (pintype "passive"))
      (node (ref "P12") (pin "2") (pinfunction "2_2") (pintype "passive"))
      (node (ref "P13") (pin "1") (pinfunction "1_1") (pintype "passive"))
      (node (ref "P13") (pin "3") (pinfunction "3_3") (pintype "passive"))
      (node (ref "P13") (pin "5") (pinfunction "5_5") (pintype "passive"))
      (node (ref "P14") (pin "1") (pinfunction "1_1") (pintype "passive"))
      (node (ref "P15") (pin "2") (pinfunction "2_2") (pintype "passive"))
      (node (ref "P16") (pin "2") (pinfunction "2_2") (pintype "passive"))
      (node (ref "P2") (pin "1") (pinfunction "1_1") (pintype "passive"))
      (node (ref "R20") (pin "1") (pinfunction "1_1") (pintype "passive"))
      (node (ref "R27") (pin "1") (pintype "passive"))
      (node (ref "R28") (pin "1") (pintype "passive"))
      (node (ref "R3") (pin "1") (pintype "passive"))
      (node (ref "R31") (pin "1") (pinfunction "1_1") (pintype "passive"))
      (node (ref "R33") (pin "2") (pinfunction "2_2") (pintype "passive"))
      (node (ref "R35") (pin "2") (pinfunction "2_2") (pintype "passive"))
      (node (ref "R4") (pin "1") (pintype "passive"))
      (node (ref "U1") (pin "12") (pinfunction "VSSQ1_12") (pintype "power_in"))
      (node (ref "U1") (pin "28") (pinfunction "VSS2_28") (pintype "power_in"))
      (node (ref "U1") (pin "41") (pinfunction "VSS0_41") (pintype "power_in"))
      (node (ref "U1") (pin "46") (pinfunction "VSSQ2_46") (pintype "power_in"))
      (node (ref "U1") (pin "52") (pinfunction "VSSQ3_52") (pintype "power_in"))
      (node (ref "U1") (pin "54") (pinfunction "VSS1_54") (pintype "power_in"))
      (node (ref "U1") (pin "6") (pinfunction "VSSQ0_6") (pintype "power_in"))
      (node (ref "U10") (pin "2") (pinfunction "GND_2") (pintype "passive"))
      (node (ref "U11") (pin "3") (pinfunction "gnd_3") (pintype "passive"))
      (node (ref "U11") (pin "5") (pinfunction "~{on}/off_5") (pintype "passive"))
      (node (ref "U2") (pin "13") (pinfunction "VSS_13") (pintype "passive"))
      (node (ref "U2") (pin "36") (pinfunction "VSS_36") (pintype "passive"))
      (node (ref "U3") (pin "4") (pinfunction "GND_4") (pintype "passive"))
      (node (ref "U4") (pin "10") (pinfunction "AGND_10") (pintype "passive"))
      (node (ref "U4") (pin "14") (pinfunction "AGND_14") (pintype "passive"))
      (node (ref "U4") (pin "25") (pinfunction "GND_25") (pintype "passive"))
      (node (ref "U4") (pin "37") (pinfunction "GND_37") (pintype "passive"))
      (node (ref "U4") (pin "4") (pinfunction "GND_4") (pintype "passive"))
      (node (ref "U4") (pin "52") (pinfunction "GND_52") (pintype "passive"))
      (node (ref "U4") (pin "64") (pinfunction "GND_64") (pintype "passive"))
      (node (ref "U5") (pin "114") (pinfunction "VSS_114") (pintype "passive"))
      (node (ref "U5") (pin "125") (pinfunction "VSS_125") (pintype "passive"))
      (node (ref "U5") (pin "136") (pinfunction "VSS_136") (pintype "passive"))
      (node (ref "U5") (pin "14") (pinfunction "VSS_14") (pintype "passive"))
      (node (ref "U5") (pin "149") (pinfunction "VSS_149") (pintype "passive"))
      (node (ref "U5") (pin "170") (pinfunction "VSS_170") (pintype "passive"))
      (node (ref "U5") (pin "184") (pinfunction "VSS_184") (pintype "passive"))
      (node (ref "U5") (pin "202") (pinfunction "VSS_202") (pintype "passive"))
      (node (ref "U5") (pin "25") (pinfunction "VSS_25") (pintype "passive"))
      (node (ref "U5") (pin "51") (pinfunction "VSS_51") (pintype "passive"))
      (node (ref "U5") (pin "60") (pinfunction "VSS_60") (pintype "passive"))
      (node (ref "U5") (pin "72") (pinfunction "VSS_72") (pintype "passive"))
      (node (ref "U5") (pin "82") (pinfunction "VSS_82") (pintype "passive"))
      (node (ref "U5") (pin "93") (pinfunction "VSS_93") (pintype "passive"))
      (node (ref "U6") (pin "1") (pinfunction "SD_1") (pintype "passive"))
      (node (ref "U6") (pin "7") (pinfunction "GND_7") (pintype "passive"))
      (node (ref "U7") (pin "4") (pinfunction "GND_4") (pintype "passive"))
      (node (ref "U8") (pin "1") (pinfunction "A0_1") (pintype "passive"))
      (node (ref "U8") (pin "2") (pinfunction "A1_2") (pintype "passive"))
      (node (ref "U8") (pin "3") (pinfunction "A2_3") (pintype "passive"))
      (node (ref "U8") (pin "4") (pinfunction "GND_4") (pintype "passive"))
      (node (ref "U8") (pin "7") (pinfunction "WP_7") (pintype "passive"))
      (node (ref "U9") (pin "1") (pinfunction "GND_1") (pintype "passive"))
      (node (ref "UDLDG1") (pin "9") (pinfunction "GND_9") (pintype "passive"))
      (node (ref "UDLDG10") (pin "9") (pinfunction "GND_9") (pintype "passive"))
      (node (ref "UDLDG11") (pin "9") (pinfunction "GND_9") (pintype "passive"))
      (node (ref "UDLDG12") (pin "9") (pinfunction "GND_9") (pintype "passive"))
      (node (ref "UDLDG13") (pin "9") (pinfunction "GND_9") (pintype "passive"))
      (node (ref "UDLDG14") (pin "9") (pinfunction "GND_9") (pintype "passive"))
      (node (ref "UDLDG15") (pin "9") (pinfunction "GND_9") (pintype "passive"))
      (node (ref "UDLDG16") (pin "9") (pinfunction "GND_9") (pintype "passive"))
      (node (ref "UDLDG17") (pin "9") (pinfunction "GND_9") (pintype "passive"))
      (node (ref "UDLDG18") (pin "9") (pinfunction "GND_9") (pintype "passive"))
      (node (ref "UDLDG19") (pin "9") (pinfunction "GND_9") (pintype "passive"))
      (node (ref "UDLDG2") (pin "9") (pinfunction "GND_9") (pintype "passive"))
      (node (ref "UDLDG20") (pin "9") (pinfunction "GND_9") (pintype "passive"))
      (node (ref "UDLDG21") (pin "9") (pinfunction "GND_9") (pintype "passive"))
      (node (ref "UDLDG22") (pin "9") (pinfunction "GND_9") (pintype "passive"))
      (node (ref "UDLDG23") (pin "9") (pinfunction "GND_9") (pintype "passive"))
      (node (ref "UDLDG24") (pin "9") (pinfunction "GND_9") (pintype "passive"))
      (node (ref "UDLDG25") (pin "9") (pinfunction "GND_9") (pintype "passive"))
      (node (ref "UDLDG26") (pin "9") (pinfunction "GND_9") (pintype "passive"))
      (node (ref "UDLDG27") (pin "9") (pinfunction "GND_9") (pintype "passive"))
      (node (ref "UDLDG28") (pin "9") (pinfunction "GND_9") (pintype "passive"))
      (node (ref "UDLDG29") (pin "9") (pinfunction "GND_9") (pintype "passive"))
      (node (ref "UDLDG3") (pin "9") (pinfunction "GND_9") (pintype "passive"))
      (node (ref "UDLDG30") (pin "9") (pinfunction "GND_9") (pintype "passive"))
      (node (ref "UDLDG4") (pin "9") (pinfunction "GND_9") (pintype "passive"))
      (node (ref "UDLDG5") (pin "9") (pinfunction "GND_9") (pintype "passive"))
      (node (ref "UDLDG6") (pin "9") (pinfunction "GND_9") (pintype "passive"))
      (node (ref "UDLDG7") (pin "9") (pinfunction "GND_9") (pintype "passive"))
      (node (ref "UDLDG8") (pin "9") (pinfunction "GND_9") (pintype "passive"))
      (node (ref "UDLDG9") (pin "9") (pinfunction "GND_9") (pintype "passive"))
      (node (ref "USB_1") (pin "5") (pinfunction "GND_5") (pintype "passive"))
      (node (ref "USCQ1") (pin "1") (pinfunction "~{OE}_1") (pintype "input"))
      (node (ref "USCQ1") (pin "10") (pinfunction "GND_10") (pintype "power_in"))
      (node (ref "USCQ10") (pin "1") (pinfunction "~{OE}_1") (pintype "input"))
      (node (ref "USCQ10") (pin "10") (pinfunction "GND_10") (pintype "power_in"))
      (node (ref "USCQ11") (pin "1") (pinfunction "~{OE}_1") (pintype "input"))
      (node (ref "USCQ11") (pin "10") (pinfunction "GND_10") (pintype "power_in"))
      (node (ref "USCQ12") (pin "1") (pinfunction "~{OE}_1") (pintype "input"))
      (node (ref "USCQ12") (pin "10") (pinfunction "GND_10") (pintype "power_in"))
      (node (ref "USCQ13") (pin "1") (pinfunction "~{OE}_1") (pintype "input"))
      (node (ref "USCQ13") (pin "10") (pinfunction "GND_10") (pintype "power_in"))
      (node (ref "USCQ14") (pin "1") (pinfunction "~{OE}_1") (pintype "input"))
      (node (ref "USCQ14") (pin "10") (pinfunction "GND_10") (pintype "power_in"))
      (node (ref "USCQ15") (pin "1") (pinfunction "~{OE}_1") (pintype "input"))
      (node (ref "USCQ15") (pin "10") (pinfunction "GND_10") (pintype "power_in"))
      (node (ref "USCQ16") (pin "1") (pinfunction "~{OE}_1") (pintype "input"))
      (node (ref "USCQ16") (pin "10") (pinfunction "GND_10") (pintype "power_in"))
      (node (ref "USCQ17") (pin "1") (pinfunction "~{OE}_1") (pintype "input"))
      (node (ref "USCQ17") (pin "10") (pinfunction "GND_10") (pintype "power_in"))
      (node (ref "USCQ18") (pin "1") (pinfunction "~{OE}_1") (pintype "input"))
      (node (ref "USCQ18") (pin "10") (pinfunction "GND_10") (pintype "power_in"))
      (node (ref "USCQ19") (pin "1") (pinfunction "~{OE}_1") (pintype "input"))
      (node (ref "USCQ19") (pin "10") (pinfunction "GND_10") (pintype "power_in"))
      (node (ref "USCQ2") (pin "1") (pinfunction "~{OE}_1") (pintype "input"))
      (node (ref "USCQ2") (pin "10") (pinfunction "GND_10") (pintype "power_in"))
      (node (ref "USCQ20") (pin "1") (pinfunction "~{OE}_1") (pintype "input"))
      (node (ref "USCQ20") (pin "10") (pinfunction "GND_10") (pintype "power_in"))
      (node (ref "USCQ21") (pin "1") (pinfunction "~{OE}_1") (pintype "input"))
      (node (ref "USCQ21") (pin "10") (pinfunction "GND_10") (pintype "power_in"))
      (node (ref "USCQ22") (pin "1") (pinfunction "~{OE}_1") (pintype "input"))
      (node (ref "USCQ22") (pin "10") (pinfunction "GND_10") (pintype "power_in"))
      (node (ref "USCQ23") (pin "1") (pinfunction "~{OE}_1") (pintype "input"))
      (node (ref "USCQ23") (pin "10") (pinfunction "GND_10") (pintype "power_in"))
      (node (ref "USCQ24") (pin "1") (pinfunction "~{OE}_1") (pintype "input"))
      (node (ref "USCQ24") (pin "10") (pinfunction "GND_10") (pintype "power_in"))
      (node (ref "USCQ25") (pin "1") (pinfunction "~{OE}_1") (pintype "input"))
      (node (ref "USCQ25") (pin "10") (pinfunction "GND_10") (pintype "power_in"))
      (node (ref "USCQ26") (pin "1") (pinfunction "~{OE}_1") (pintype "input"))
      (node (ref "USCQ26") (pin "10") (pinfunction "GND_10") (pintype "power_in"))
      (node (ref "USCQ27") (pin "1") (pinfunction "~{OE}_1") (pintype "input"))
      (node (ref "USCQ27") (pin "10") (pinfunction "GND_10") (pintype "power_in"))
      (node (ref "USCQ28") (pin "1") (pinfunction "~{OE}_1") (pintype "input"))
      (node (ref "USCQ28") (pin "10") (pinfunction "GND_10") (pintype "power_in"))
      (node (ref "USCQ29") (pin "1") (pinfunction "~{OE}_1") (pintype "input"))
      (node (ref "USCQ29") (pin "10") (pinfunction "GND_10") (pintype "power_in"))
      (node (ref "USCQ3") (pin "1") (pinfunction "~{OE}_1") (pintype "input"))
      (node (ref "USCQ3") (pin "10") (pinfunction "GND_10") (pintype "power_in"))
      (node (ref "USCQ30") (pin "1") (pinfunction "~{OE}_1") (pintype "input"))
      (node (ref "USCQ30") (pin "10") (pinfunction "GND_10") (pintype "power_in"))
      (node (ref "USCQ4") (pin "1") (pinfunction "~{OE}_1") (pintype "input"))
      (node (ref "USCQ4") (pin "10") (pinfunction "GND_10") (pintype "power_in"))
      (node (ref "USCQ5") (pin "1") (pinfunction "~{OE}_1") (pintype "input"))
      (node (ref "USCQ5") (pin "10") (pinfunction "GND_10") (pintype "power_in"))
      (node (ref "USCQ6") (pin "1") (pinfunction "~{OE}_1") (pintype "input"))
      (node (ref "USCQ6") (pin "10") (pinfunction "GND_10") (pintype "power_in"))
      (node (ref "USCQ7") (pin "1") (pinfunction "~{OE}_1") (pintype "input"))
      (node (ref "USCQ7") (pin "10") (pinfunction "GND_10") (pintype "power_in"))
      (node (ref "USCQ8") (pin "1") (pinfunction "~{OE}_1") (pintype "input"))
      (node (ref "USCQ8") (pin "10") (pinfunction "GND_10") (pintype "power_in"))
      (node (ref "USCQ9") (pin "1") (pinfunction "~{OE}_1") (pintype "input"))
      (node (ref "USCQ9") (pin "10") (pinfunction "GND_10") (pintype "power_in"))
      (node (ref "WK1") (pin "3") (pinfunction "3_3") (pintype "passive"))
      (node (ref "X1") (pin "2") (pinfunction "GND_2") (pintype "passive"))
    )
    (net (code "714") (name "LCDGND") (class "Default")
      (node (ref "C68") (pin "1") (pinfunction "1_1") (pintype "passive"))
      (node (ref "D60") (pin "1") (pinfunction "A_1") (pintype "passive"))
      (node (ref "FB9") (pin "2") (pinfunction "2_2") (pintype "passive"))
      (node (ref "PLCD1") (pin "11") (pinfunction "11_11") (pintype "passive"))
      (node (ref "PLCD1") (pin "12") (pinfunction "12_12") (pintype "passive"))
      (node (ref "PLCD1") (pin "13") (pinfunction "13_13") (pintype "passive"))
      (node (ref "PLCD1") (pin "20") (pinfunction "20_20") (pintype "passive"))
      (node (ref "PLCD1") (pin "21") (pinfunction "21_21") (pintype "passive"))
      (node (ref "PLCD1") (pin "22") (pinfunction "22_22") (pintype "passive"))
      (node (ref "PLCD1") (pin "23") (pinfunction "23_23") (pintype "passive"))
      (node (ref "PLCD1") (pin "29") (pinfunction "29_29") (pintype "passive"))
      (node (ref "PLCD1") (pin "3") (pinfunction "3_3") (pintype "passive"))
      (node (ref "PLCD1") (pin "4") (pinfunction "4_4") (pintype "passive"))
      (node (ref "PLCD1") (pin "5") (pinfunction "5_5") (pintype "passive"))
      (node (ref "PLCD1") (pin "A") (pinfunction "A_A") (pintype "passive"))
      (node (ref "PLCD1") (pin "B") (pinfunction "B_B") (pintype "passive"))
    )
    (net (code "715") (name "LCDVCC5") (class "Default")
      (node (ref "C68") (pin "2") (pinfunction "2_2") (pintype "passive"))
      (node (ref "D60") (pin "2") (pinfunction "K_2") (pintype "passive"))
      (node (ref "FB8") (pin "2") (pinfunction "2_2") (pintype "passive"))
      (node (ref "PLCD1") (pin "1") (pinfunction "1_1") (pintype "passive"))
      (node (ref "PLCD1") (pin "2") (pinfunction "2_2") (pintype "passive"))
    )
    (net (code "716") (name "Net-(BOOT-Pad3)") (class "Default")
      (node (ref "BOOT") (pin "3") (pinfunction "3_3") (pintype "passive"))
      (node (ref "R43") (pin "1") (pintype "passive"))
    )
    (net (code "717") (name "Net-(BOOT-Pad4)") (class "Default")
      (node (ref "BOOT") (pin "4") (pinfunction "4_4") (pintype "passive"))
      (node (ref "R42") (pin "2") (pintype "passive"))
    )
    (net (code "718") (name "Net-(BT1-Pad1)") (class "Default")
      (node (ref "BT1") (pin "1") (pinfunction "1_1") (pintype "passive"))
      (node (ref "D59") (pin "1") (pinfunction "1_1") (pintype "passive"))
    )
    (net (code "719") (name "Net-(C1-Pad2)") (class "Default")
      (node (ref "C1") (pin "2") (pinfunction "2_2") (pintype "passive"))
      (node (ref "C2") (pin "2") (pinfunction "2_2") (pintype "passive"))
      (node (ref "R1") (pin "1") (pintype "passive"))
      (node (ref "U2") (pin "12") (pinfunction "VCC_12") (pintype "passive"))
      (node (ref "U2") (pin "37") (pinfunction "VCC_37") (pintype "passive"))
    )
    (net (code "720") (name "Net-(C29-Pad2)") (class "Default")
      (node (ref "C29") (pin "2") (pinfunction "2_2") (pintype "passive"))
      (node (ref "R19") (pin "2") (pinfunction "2_2") (pintype "passive"))
    )
    (net (code "721") (name "Net-(D1-A)") (class "Default")
      (node (ref "D1") (pin "1") (pinfunction "A_1") (pintype "passive"))
      (node (ref "R21") (pin "1") (pinfunction "1_1") (pintype "passive"))
    )
    (net (code "722") (name "Net-(D2-K)") (class "Default")
      (node (ref "D2") (pin "2") (pinfunction "K_2") (pintype "passive"))
      (node (ref "L2") (pin "2") (pinfunction "2_2") (pintype "passive"))
      (node (ref "U11") (pin "2") (pinfunction "out_2") (pintype "passive"))
    )
    (net (code "723") (name "Net-(D3-K)") (class "Default")
      (node (ref "C74") (pin "1") (pinfunction "1_1") (pintype "passive"))
      (node (ref "D3") (pin "2") (pinfunction "K_2") (pintype "passive"))
      (node (ref "L3") (pin "1") (pinfunction "1_1") (pintype "passive"))
      (node (ref "U10") (pin "6") (pinfunction "SW_6") (pintype "passive"))
    )
    (net (code "724") (name "Net-(DS1-X1)") (class "Default")
      (node (ref "CD1") (pin "2") (pinfunction "2_2") (pintype "passive"))
      (node (ref "DS1") (pin "2") (pinfunction "X1_2") (pintype "passive"))
      (node (ref "Y1") (pin "2") (pinfunction "OSC2_2") (pintype "passive"))
    )
    (net (code "725") (name "Net-(DS1-X2)") (class "Default")
      (node (ref "CD2") (pin "2") (pinfunction "2_2") (pintype "passive"))
      (node (ref "DS1") (pin "3") (pinfunction "X2_3") (pintype "passive"))
      (node (ref "Y1") (pin "1") (pinfunction "OSC1_1") (pintype "passive"))
    )
    (net (code "726") (name "Net-(FB1-Pad1)") (class "Default")
      (node (ref "FB1") (pin "1") (pinfunction "1_1") (pintype "passive"))
      (node (ref "P1") (pin "1") (pinfunction "1_1") (pintype "passive"))
    )
    (net (code "727") (name "Net-(Q1-B)") (class "Default")
      (node (ref "Q1") (pin "2") (pinfunction "B_2") (pintype "passive"))
      (node (ref "Q2") (pin "1") (pinfunction "E_1") (pintype "passive"))
      (node (ref "R39") (pin "2") (pintype "passive"))
    )
    (net (code "728") (name "Net-(Q1-C)") (class "Default")
      (node (ref "Q1") (pin "3") (pinfunction "C_3") (pintype "passive"))
      (node (ref "R38") (pin "1") (pintype "passive"))
    )
    (net (code "729") (name "Net-(Q2-B)") (class "Default")
      (node (ref "Q2") (pin "2") (pinfunction "B_2") (pintype "passive"))
      (node (ref "R40") (pin "2") (pintype "passive"))
    )
    (net (code "730") (name "Net-(Q2-C)") (class "Default")
      (node (ref "D4") (pin "2") (pintype "passive"))
      (node (ref "Q2") (pin "3") (pinfunction "C_3") (pintype "passive"))
      (node (ref "R41") (pin "2") (pintype "passive"))
    )
    (net (code "731") (name "Net-(R22-Pad1)") (class "Default")
      (node (ref "R22") (pin "1") (pinfunction "1_1") (pintype "passive"))
      (node (ref "X1") (pin "3") (pinfunction "3_3") (pintype "passive"))
    )
    (net (code "732") (name "Net-(U2-~{WP})") (class "Default")
      (node (ref "R7") (pin "1") (pintype "passive"))
      (node (ref "U2") (pin "19") (pinfunction "~{WP}_19") (pintype "passive"))
    )
    (net (code "733") (name "Net-(U4-A1)") (class "Default")
      (node (ref "U4") (pin "53") (pinfunction "A1_53") (pintype "passive"))
      (node (ref "U4") (pin "54") (pinfunction "A2_54") (pintype "passive"))
    )
    (net (code "734") (name "Net-(U4-AO_P)") (class "Default")
      (node (ref "C31") (pin "2") (pinfunction "2_2") (pintype "passive"))
      (node (ref "U4") (pin "8") (pinfunction "AO_P_8") (pintype "passive"))
    )
    (net (code "735") (name "Net-(U4-RREF)") (class "Default")
      (node (ref "R20") (pin "2") (pinfunction "2_2") (pintype "passive"))
      (node (ref "U4") (pin "3") (pinfunction "RREF_3") (pintype "passive"))
    )
    (net (code "736") (name "Net-(U4-VCM)") (class "Default")
      (node (ref "C35") (pin "1") (pinfunction "1_1") (pintype "passive"))
      (node (ref "U4") (pin "11") (pinfunction "VCM_11") (pintype "passive"))
    )
    (net (code "737") (name "Net-(U5-PC14{slash}OSC32_IN)") (class "Default")
      (node (ref "C41") (pin "2") (pinfunction "2_2") (pintype "passive"))
      (node (ref "U5") (pin "9") (pinfunction "PC14/OSC32_IN_9") (pintype "passive"))
      (node (ref "Y2") (pin "1") (pintype "passive"))
    )
    (net (code "738") (name "Net-(U5-PC15{slash}OSC32_OUT)") (class "Default")
      (node (ref "C42") (pin "1") (pinfunction "1_1") (pintype "passive"))
      (node (ref "U5") (pin "10") (pinfunction "PC15/OSC32_OUT_10") (pintype "passive"))
      (node (ref "Y2") (pin "2") (pintype "passive"))
    )
    (net (code "739") (name "Net-(U5-PDR_ON)") (class "Default")
      (node (ref "*R2") (pin "2") (pintype "passive"))
      (node (ref "R57") (pin "2") (pintype "passive"))
      (node (ref "U5") (pin "203") (pinfunction "PDR_ON_203") (pintype "passive"))
    )
    (net (code "740") (name "Net-(U5-PH1{slash}OSC_OUT)") (class "Default")
      (node (ref "*R1") (pin "2") (pintype "passive"))
      (node (ref "U5") (pin "33") (pinfunction "PH1/OSC_OUT_33") (pintype "passive"))
    )
    (net (code "741") (name "Net-(U5-VBAT)") (class "Default")
      (node (ref "*R3") (pin "2") (pintype "passive"))
      (node (ref "C47") (pin "1") (pinfunction "1_1") (pintype "passive"))
      (node (ref "R58") (pin "2") (pintype "passive"))
      (node (ref "U5") (pin "6") (pinfunction "VBAT_6") (pintype "passive"))
    )
    (net (code "742") (name "Net-(U5-VCAP1)") (class "Default")
      (node (ref "C49") (pin "2") (pinfunction "2_2") (pintype "passive"))
      (node (ref "U5") (pin "92") (pinfunction "VCAP1_92") (pintype "passive"))
    )
    (net (code "743") (name "Net-(U5-VCAP2)") (class "Default")
      (node (ref "C50") (pin "1") (pinfunction "1_1") (pintype "passive"))
      (node (ref "U5") (pin "148") (pinfunction "VCAP2_148") (pintype "passive"))
    )
    (net (code "744") (name "Net-(U6-+IN)") (class "Default")
      (node (ref "C33") (pin "1") (pintype "passive"))
      (node (ref "U6") (pin "2") (pinfunction "BP_2") (pintype "passive"))
      (node (ref "U6") (pin "3") (pinfunction "+IN_3") (pintype "passive"))
    )
    (net (code "745") (name "Net-(U6--IN)") (class "Default")
      (node (ref "C29") (pin "1") (pinfunction "1_1") (pintype "passive"))
      (node (ref "R18") (pin "1") (pinfunction "1_1") (pintype "passive"))
      (node (ref "U6") (pin "4") (pinfunction "-IN_4") (pintype "passive"))
    )
    (net (code "746") (name "Net-(U9-DTR#)") (class "Default")
      (node (ref "R40") (pin "1") (pintype "passive"))
      (node (ref "U9") (pin "13") (pinfunction "DTR#_13") (pintype "passive"))
    )
    (net (code "747") (name "Net-(U9-RTS#)") (class "Default")
      (node (ref "R39") (pin "1") (pintype "passive"))
      (node (ref "U9") (pin "14") (pinfunction "RTS#_14") (pintype "passive"))
    )
    (net (code "748") (name "Net-(U9-V3)") (class "Default")
      (node (ref "C80") (pin "2") (pintype "passive"))
      (node (ref "U9") (pin "4") (pinfunction "V3_4") (pintype "passive"))
    )
    (net (code "749") (name "Net-(U9-XI)") (class "Default")
      (node (ref "C81") (pin "2") (pintype "passive"))
      (node (ref "U9") (pin "7") (pinfunction "XI_7") (pintype "passive"))
      (node (ref "Y4") (pin "1") (pinfunction "OSC1_1") (pintype "passive"))
    )
    (net (code "750") (name "Net-(U9-XO)") (class "Default")
      (node (ref "C82") (pin "2") (pintype "passive"))
      (node (ref "U9") (pin "8") (pinfunction "XO_8") (pintype "passive"))
      (node (ref "Y4") (pin "2") (pinfunction "OSC2_2") (pintype "passive"))
    )
    (net (code "751") (name "Net-(U10-BST)") (class "Default")
      (node (ref "C74") (pin "2") (pinfunction "2_2") (pintype "passive"))
      (node (ref "U10") (pin "1") (pinfunction "BST_1") (pintype "passive"))
    )
    (net (code "752") (name "Net-(U10-EN)") (class "Default")
      (node (ref "R34") (pin "1") (pinfunction "1_1") (pintype "passive"))
      (node (ref "U10") (pin "4") (pinfunction "EN_4") (pintype "passive"))
    )
    (net (code "753") (name "Net-(U10-FB)") (class "Default")
      (node (ref "R35") (pin "1") (pinfunction "1_1") (pintype "passive"))
      (node (ref "R36") (pin "2") (pinfunction "2_2") (pintype "passive"))
      (node (ref "R37") (pin "2") (pinfunction "2_2") (pintype "passive"))
      (node (ref "U10") (pin "3") (pinfunction "FB_3") (pintype "passive"))
    )
    (net (code "754") (name "Net-(U11-feeddack)") (class "Default")
      (node (ref "R32") (pin "1") (pinfunction "1_1") (pintype "passive"))
      (node (ref "R33") (pin "1") (pinfunction "1_1") (pintype "passive"))
      (node (ref "U11") (pin "4") (pinfunction "feeddack_4") (pintype "passive"))
    )
    (net (code "755") (name "Net-(X1-VCC)") (class "Default")
      (node (ref "C27") (pin "1") (pinfunction "1_1") (pintype "passive"))
      (node (ref "L1") (pin "2") (pinfunction "2_2") (pintype "passive"))
      (node (ref "X1") (pin "1") (pinfunction "1_1") (pintype "passive"))
      (node (ref "X1") (pin "4") (pinfunction "VCC_4") (pintype "passive"))
    )
    (net (code "756") (name "PWR_IN") (class "Default")
      (node (ref "C37") (pin "1") (pinfunction "1_1") (pintype "passive"))
      (node (ref "C38") (pin "1") (pinfunction "1_1") (pintype "passive"))
      (node (ref "C39") (pin "1") (pinfunction "1_1") (pintype "passive"))
      (node (ref "P2") (pin "2") (pinfunction "2_2") (pintype "passive"))
      (node (ref "P3") (pin "1") (pinfunction "1_1") (pintype "passive"))
      (node (ref "R21") (pin "2") (pinfunction "2_2") (pintype "passive"))
      (node (ref "U4") (pin "20") (pinfunction "PWR_IN_20") (pintype "passive"))
    )
    (net (code "757") (name "V3.3V") (class "Default")
      (node (ref "BOOT") (pin "1") (pinfunction "1_1") (pintype "passive"))
      (node (ref "BOOT") (pin "2") (pinfunction "2_2") (pintype "passive"))
      (node (ref "C10") (pin "2") (pinfunction "2_2") (pintype "passive"))
      (node (ref "C11") (pin "2") (pinfunction "2_2") (pintype "passive"))
      (node (ref "C12") (pin "2") (pinfunction "2_2") (pintype "passive"))
      (node (ref "C13") (pin "2") (pinfunction "2_2") (pintype "passive"))
      (node (ref "C16") (pin "2") (pinfunction "2_2") (pintype "passive"))
      (node (ref "C3") (pin "2") (pinfunction "2_2") (pintype "passive"))
      (node (ref "C45") (pin "2") (pinfunction "2_2") (pintype "passive"))
      (node (ref "C46") (pin "2") (pinfunction "2_2") (pintype "passive"))
      (node (ref "C5") (pin "2") (pintype "passive"))
      (node (ref "C51") (pin "2") (pinfunction "2_2") (pintype "passive"))
      (node (ref "C52") (pin "2") (pinfunction "2_2") (pintype "passive"))
      (node (ref "C53") (pin "2") (pinfunction "2_2") (pintype "passive"))
      (node (ref "C54") (pin "2") (pinfunction "2_2") (pintype "passive"))
      (node (ref "C55") (pin "2") (pinfunction "2_2") (pintype "passive"))
      (node (ref "C56") (pin "2") (pinfunction "2_2") (pintype "passive"))
      (node (ref "C57") (pin "2") (pinfunction "2_2") (pintype "passive"))
      (node (ref "C58") (pin "2") (pinfunction "2_2") (pintype "passive"))
      (node (ref "C59") (pin "2") (pinfunction "2_2") (pintype "passive"))
      (node (ref "C60") (pin "2") (pinfunction "2_2") (pintype "passive"))
      (node (ref "C61") (pin "2") (pinfunction "2_2") (pintype "passive"))
      (node (ref "C62") (pin "2") (pinfunction "2_2") (pintype "passive"))
      (node (ref "C63") (pin "2") (pinfunction "2_2") (pintype "passive"))
      (node (ref "C64") (pin "2") (pinfunction "2_2") (pintype "passive"))
      (node (ref "C65") (pin "2") (pinfunction "2_2") (pintype "passive"))
      (node (ref "C66") (pin "2") (pinfunction "2_2") (pintype "passive"))
      (node (ref "C67") (pin "2") (pinfunction "2_2") (pintype "passive"))
      (node (ref "C7") (pin "2") (pinfunction "2_2") (pintype "passive"))
      (node (ref "C76") (pin "2") (pinfunction "2_2") (pintype "passive"))
      (node (ref "C77") (pin "1") (pinfunction "1_1") (pintype "passive"))
      (node (ref "C8") (pin "2") (pinfunction "2_2") (pintype "passive"))
      (node (ref "C9") (pin "2") (pinfunction "2_2") (pintype "passive"))
      (node (ref "D59") (pin "2") (pinfunction "2_2") (pintype "passive"))
      (node (ref "DS1") (pin "1") (pinfunction "VCC2_1") (pintype "passive"))
      (node (ref "FB1") (pin "2") (pinfunction "2_2") (pintype "passive"))
      (node (ref "FB6") (pin "1") (pinfunction "1_1") (pintype "passive"))
      (node (ref "J1") (pin "4") (pinfunction "VDD_4") (pintype "passive"))
      (node (ref "L1") (pin "1") (pinfunction "1_1") (pintype "passive"))
      (node (ref "L3") (pin "2") (pinfunction "2_2") (pintype "passive"))
      (node (ref "P14") (pin "4") (pinfunction "4_4") (pintype "passive"))
      (node (ref "P2") (pin "3") (pinfunction "3_3") (pintype "passive"))
      (node (ref "P4") (pin "2") (pinfunction "2_2") (pintype "passive"))
      (node (ref "Q1") (pin "1") (pinfunction "E_1") (pintype "passive"))
      (node (ref "R1") (pin "2") (pintype "passive"))
      (node (ref "R10") (pin "2") (pinfunction "2_2") (pintype "passive"))
      (node (ref "R11") (pin "2") (pinfunction "2_2") (pintype "passive"))
      (node (ref "R12") (pin "2") (pinfunction "2_2") (pintype "passive"))
      (node (ref "R2") (pin "1") (pintype "passive"))
      (node (ref "R36") (pin "1") (pinfunction "1_1") (pintype "passive"))
      (node (ref "R37") (pin "1") (pinfunction "1_1") (pintype "passive"))
      (node (ref "R41") (pin "1") (pintype "passive"))
      (node (ref "R5") (pin "2") (pintype "passive"))
      (node (ref "R54") (pin "1") (pintype "passive"))
      (node (ref "R55") (pin "1") (pintype "passive"))
      (node (ref "R56") (pin "1") (pintype "passive"))
      (node (ref "R57") (pin "1") (pintype "passive"))
      (node (ref "R58") (pin "1") (pintype "passive"))
      (node (ref "R6") (pin "2") (pintype "passive"))
      (node (ref "R7") (pin "2") (pintype "passive"))
      (node (ref "R8") (pin "2") (pinfunction "2_2") (pintype "passive"))
      (node (ref "R9") (pin "2") (pinfunction "2_2") (pintype "passive"))
      (node (ref "U1") (pin "1") (pinfunction "VDD0_1") (pintype "power_in"))
      (node (ref "U1") (pin "14") (pinfunction "VDD1_14") (pintype "power_in"))
      (node (ref "U1") (pin "27") (pinfunction "VDD2_27") (pintype "power_in"))
      (node (ref "U1") (pin "3") (pinfunction "VDDQ0_3") (pintype "power_in"))
      (node (ref "U1") (pin "43") (pinfunction "VDDQ2_43") (pintype "power_in"))
      (node (ref "U1") (pin "49") (pinfunction "VDDQ3_49") (pintype "power_in"))
      (node (ref "U1") (pin "9") (pinfunction "VDDQ1_9") (pintype "power_in"))
      (node (ref "U5") (pin "103") (pinfunction "VDD_103") (pintype "passive"))
      (node (ref "U5") (pin "115") (pinfunction "VDD_115") (pintype "passive"))
      (node (ref "U5") (pin "124") (pinfunction "VDD_124") (pintype "passive"))
      (node (ref "U5") (pin "137") (pinfunction "VDD_137") (pintype "passive"))
      (node (ref "U5") (pin "15") (pinfunction "VDD_15") (pintype "passive"))
      (node (ref "U5") (pin "150") (pinfunction "VDD_150") (pintype "passive"))
      (node (ref "U5") (pin "158") (pinfunction "VDD_158") (pintype "passive"))
      (node (ref "U5") (pin "171") (pinfunction "VDD_171") (pintype "passive"))
      (node (ref "U5") (pin "185") (pinfunction "VDD_185") (pintype "passive"))
      (node (ref "U5") (pin "204") (pinfunction "VDD_204") (pintype "passive"))
      (node (ref "U5") (pin "26") (pinfunction "VDD_26") (pintype "passive"))
      (node (ref "U5") (pin "39") (pinfunction "VDD_39") (pintype "passive"))
      (node (ref "U5") (pin "52") (pinfunction "VDD_52") (pintype "passive"))
      (node (ref "U5") (pin "59") (pinfunction "VDD_59") (pintype "passive"))
      (node (ref "U5") (pin "73") (pinfunction "VDD_73") (pintype "passive"))
      (node (ref "U5") (pin "83") (pinfunction "VDD_83") (pintype "passive"))
      (node (ref "U5") (pin "94") (pinfunction "VDD_94") (pintype "passive"))
      (node (ref "U7") (pin "3") (pinfunction "~{WP}(IO2)_3") (pintype "passive"))
      (node (ref "U7") (pin "7") (pinfunction "HOLD/RST(IO3)_7") (pintype "power_in"))
      (node (ref "U7") (pin "8") (pinfunction "VCC_8") (pintype "passive"))
      (node (ref "U8") (pin "8") (pinfunction "VCC1_8") (pintype "passive"))
    )
    (net (code "758") (name "V5V") (class "Default")
      (node (ref "C72") (pin "1") (pinfunction "1_1") (pintype "passive"))
      (node (ref "C73") (pin "1") (pinfunction "1_1") (pintype "passive"))
      (node (ref "C75") (pin "1") (pinfunction "1_1") (pintype "passive"))
      (node (ref "C78") (pin "1") (pintype "passive"))
      (node (ref "C79") (pin "1") (pintype "passive"))
      (node (ref "C83") (pin "2") (pintype "passive"))
      (node (ref "FB8") (pin "1") (pinfunction "1_1") (pintype "passive"))
      (node (ref "L2") (pin "1") (pinfunction "1_1") (pintype "passive"))
      (node (ref "P12") (pin "3") (pinfunction "3_3") (pintype "passive"))
      (node (ref "R32") (pin "2") (pinfunction "2_2") (pintype "passive"))
      (node (ref "R34") (pin "2") (pinfunction "2_2") (pintype "passive"))
      (node (ref "U10") (pin "5") (pinfunction "IN_5") (pintype "passive"))
      (node (ref "U9") (pin "16") (pinfunction "VCC_16") (pintype "passive"))
      (node (ref "USB_1") (pin "1") (pinfunction "VCC_1") (pintype "passive"))
      (node (ref "USCQ1") (pin "20") (pinfunction "VCC_20") (pintype "power_in"))
      (node (ref "USCQ10") (pin "20") (pinfunction "VCC_20") (pintype "power_in"))
      (node (ref "USCQ11") (pin "20") (pinfunction "VCC_20") (pintype "power_in"))
      (node (ref "USCQ12") (pin "20") (pinfunction "VCC_20") (pintype "power_in"))
      (node (ref "USCQ13") (pin "20") (pinfunction "VCC_20") (pintype "power_in"))
      (node (ref "USCQ14") (pin "20") (pinfunction "VCC_20") (pintype "power_in"))
      (node (ref "USCQ15") (pin "20") (pinfunction "VCC_20") (pintype "power_in"))
      (node (ref "USCQ16") (pin "20") (pinfunction "VCC_20") (pintype "power_in"))
      (node (ref "USCQ17") (pin "20") (pinfunction "VCC_20") (pintype "power_in"))
      (node (ref "USCQ18") (pin "20") (pinfunction "VCC_20") (pintype "power_in"))
      (node (ref "USCQ19") (pin "20") (pinfunction "VCC_20") (pintype "power_in"))
      (node (ref "USCQ2") (pin "20") (pinfunction "VCC_20") (pintype "power_in"))
      (node (ref "USCQ20") (pin "20") (pinfunction "VCC_20") (pintype "power_in"))
      (node (ref "USCQ21") (pin "20") (pinfunction "VCC_20") (pintype "power_in"))
      (node (ref "USCQ22") (pin "20") (pinfunction "VCC_20") (pintype "power_in"))
      (node (ref "USCQ23") (pin "20") (pinfunction "VCC_20") (pintype "power_in"))
      (node (ref "USCQ24") (pin "20") (pinfunction "VCC_20") (pintype "power_in"))
      (node (ref "USCQ25") (pin "20") (pinfunction "VCC_20") (pintype "power_in"))
      (node (ref "USCQ26") (pin "20") (pinfunction "VCC_20") (pintype "power_in"))
      (node (ref "USCQ27") (pin "20") (pinfunction "VCC_20") (pintype "power_in"))
      (node (ref "USCQ28") (pin "20") (pinfunction "VCC_20") (pintype "power_in"))
      (node (ref "USCQ29") (pin "20") (pinfunction "VCC_20") (pintype "power_in"))
      (node (ref "USCQ3") (pin "20") (pinfunction "VCC_20") (pintype "power_in"))
      (node (ref "USCQ30") (pin "20") (pinfunction "VCC_20") (pintype "power_in"))
      (node (ref "USCQ4") (pin "20") (pinfunction "VCC_20") (pintype "power_in"))
      (node (ref "USCQ5") (pin "20") (pinfunction "VCC_20") (pintype "power_in"))
      (node (ref "USCQ6") (pin "20") (pinfunction "VCC_20") (pintype "power_in"))
      (node (ref "USCQ7") (pin "20") (pinfunction "VCC_20") (pintype "power_in"))
      (node (ref "USCQ8") (pin "20") (pinfunction "VCC_20") (pintype "power_in"))
      (node (ref "USCQ9") (pin "20") (pinfunction "VCC_20") (pintype "power_in"))
    )
    (net (code "759") (name "V6V") (class "Default")
      (node (ref "C14") (pin "2") (pinfunction "2_2") (pintype "passive"))
      (node (ref "C71") (pin "2") (pinfunction "2_2") (pintype "passive"))
      (node (ref "CA1") (pin "1") (pinfunction "1_1") (pintype "passive"))
      (node (ref "K8") (pin "5") (pinfunction "1_5") (pintype "passive"))
      (node (ref "P12") (pin "1") (pinfunction "1_1") (pintype "passive"))
      (node (ref "P13") (pin "2") (pinfunction "2_2") (pintype "passive"))
      (node (ref "P13") (pin "4") (pinfunction "4_4") (pintype "passive"))
      (node (ref "P13") (pin "6") (pinfunction "6_6") (pintype "passive"))
      (node (ref "U11") (pin "1") (pinfunction "Vin_1") (pintype "passive"))
      (node (ref "U3") (pin "2") (pinfunction "VS_2") (pintype "passive"))
    )
    (net (code "760") (name "VCC3.3") (class "Default")
      (node (ref "C20") (pin "2") (pinfunction "2_2") (pintype "passive"))
      (node (ref "C21") (pin "1") (pinfunction "1_1") (pintype "passive"))
      (node (ref "C22") (pin "2") (pinfunction "2_2") (pintype "passive"))
      (node (ref "C6") (pin "2") (pinfunction "2_2") (pintype "passive"))
      (node (ref "C69") (pin "1") (pinfunction "1_1") (pintype "passive"))
      (node (ref "C70") (pin "1") (pinfunction "1_1") (pintype "passive"))
      (node (ref "FB2") (pin "2") (pinfunction "2_2") (pintype "passive"))
      (node (ref "P3") (pin "3") (pinfunction "3_3") (pintype "passive"))
      (node (ref "P4") (pin "1") (pinfunction "1_1") (pintype "passive"))
      (node (ref "R13") (pin "1") (pinfunction "1_1") (pintype "passive"))
      (node (ref "R14") (pin "1") (pinfunction "1_1") (pintype "passive"))
      (node (ref "R15") (pin "1") (pinfunction "1_1") (pintype "passive"))
      (node (ref "R16") (pin "1") (pinfunction "1_1") (pintype "passive"))
      (node (ref "R17") (pin "1") (pinfunction "1_1") (pintype "passive"))
      (node (ref "R23") (pin "1") (pintype "passive"))
      (node (ref "R24") (pin "1") (pinfunction "1_1") (pintype "passive"))
      (node (ref "R25") (pin "1") (pinfunction "1_1") (pintype "passive"))
      (node (ref "R26") (pin "2") (pinfunction "2_2") (pintype "passive"))
      (node (ref "R30") (pin "2") (pintype "passive"))
      (node (ref "U4") (pin "22") (pinfunction "VDD33_O_22") (pintype "passive"))
      (node (ref "U4") (pin "36") (pinfunction "VDD33_36") (pintype "passive"))
      (node (ref "U4") (pin "46") (pinfunction "VDD33_46") (pintype "passive"))
    )
    (net (code "761") (name "VDD12") (class "Default")
      (node (ref "C19") (pin "2") (pinfunction "2_2") (pintype "passive"))
      (node (ref "C26") (pin "1") (pinfunction "1_1") (pintype "passive"))
      (node (ref "C28") (pin "2") (pinfunction "2_2") (pintype "passive"))
      (node (ref "U4") (pin "1") (pinfunction "VDD12_1") (pintype "passive"))
      (node (ref "U4") (pin "23") (pinfunction "VDD12_O_23") (pintype "passive"))
    )
    (net (code "762") (name "VIN_6V") (class "Default")
      (node (ref "DC1") (pin "1") (pinfunction "1_1") (pintype "passive"))
      (node (ref "K8") (pin "6") (pinfunction "2_6") (pintype "passive"))
      (node (ref "P10") (pin "1") (pinfunction "1_1") (pintype "passive"))
      (node (ref "P10") (pin "2") (pinfunction "2_2") (pintype "passive"))
      (node (ref "P11") (pin "1") (pinfunction "1_1") (pintype "passive"))
      (node (ref "P11") (pin "2") (pinfunction "2_2") (pintype "passive"))
      (node (ref "P5") (pin "1") (pinfunction "1_1") (pintype "passive"))
      (node (ref "P5") (pin "2") (pinfunction "2_2") (pintype "passive"))
      (node (ref "P5") (pin "3") (pinfunction "3_3") (pintype "passive"))
      (node (ref "P6") (pin "1") (pinfunction "1_1") (pintype "passive"))
      (node (ref "P6") (pin "2") (pinfunction "2_2") (pintype "passive"))
      (node (ref "P7") (pin "1") (pinfunction "1_1") (pintype "passive"))
      (node (ref "P7") (pin "2") (pinfunction "2_2") (pintype "passive"))
      (node (ref "P8") (pin "1") (pinfunction "1_1") (pintype "passive"))
      (node (ref "P8") (pin "2") (pinfunction "2_2") (pintype "passive"))
      (node (ref "P9") (pin "1") (pinfunction "1_1") (pintype "passive"))
      (node (ref "P9") (pin "2") (pinfunction "2_2") (pintype "passive"))
      (node (ref "UDLDG1") (pin "10") (pinfunction "COM_10") (pintype "passive"))
      (node (ref "UDLDG10") (pin "10") (pinfunction "COM_10") (pintype "passive"))
      (node (ref "UDLDG11") (pin "10") (pinfunction "COM_10") (pintype "passive"))
      (node (ref "UDLDG12") (pin "10") (pinfunction "COM_10") (pintype "passive"))
      (node (ref "UDLDG13") (pin "10") (pinfunction "COM_10") (pintype "passive"))
      (node (ref "UDLDG14") (pin "10") (pinfunction "COM_10") (pintype "passive"))
      (node (ref "UDLDG15") (pin "10") (pinfunction "COM_10") (pintype "passive"))
      (node (ref "UDLDG16") (pin "10") (pinfunction "COM_10") (pintype "passive"))
      (node (ref "UDLDG17") (pin "10") (pinfunction "COM_10") (pintype "passive"))
      (node (ref "UDLDG18") (pin "10") (pinfunction "COM_10") (pintype "passive"))
      (node (ref "UDLDG19") (pin "10") (pinfunction "COM_10") (pintype "passive"))
      (node (ref "UDLDG2") (pin "10") (pinfunction "COM_10") (pintype "passive"))
      (node (ref "UDLDG20") (pin "10") (pinfunction "COM_10") (pintype "passive"))
      (node (ref "UDLDG21") (pin "10") (pinfunction "COM_10") (pintype "passive"))
      (node (ref "UDLDG22") (pin "10") (pinfunction "COM_10") (pintype "passive"))
      (node (ref "UDLDG23") (pin "10") (pinfunction "COM_10") (pintype "passive"))
      (node (ref "UDLDG24") (pin "10") (pinfunction "COM_10") (pintype "passive"))
      (node (ref "UDLDG25") (pin "10") (pinfunction "COM_10") (pintype "passive"))
      (node (ref "UDLDG26") (pin "10") (pinfunction "COM_10") (pintype "passive"))
      (node (ref "UDLDG27") (pin "10") (pinfunction "COM_10") (pintype "passive"))
      (node (ref "UDLDG28") (pin "10") (pinfunction "COM_10") (pintype "passive"))
      (node (ref "UDLDG29") (pin "10") (pinfunction "COM_10") (pintype "passive"))
      (node (ref "UDLDG3") (pin "10") (pinfunction "COM_10") (pintype "passive"))
      (node (ref "UDLDG30") (pin "10") (pinfunction "COM_10") (pintype "passive"))
      (node (ref "UDLDG4") (pin "10") (pinfunction "COM_10") (pintype "passive"))
      (node (ref "UDLDG5") (pin "10") (pinfunction "COM_10") (pintype "passive"))
      (node (ref "UDLDG6") (pin "10") (pinfunction "COM_10") (pintype "passive"))
      (node (ref "UDLDG7") (pin "10") (pinfunction "COM_10") (pintype "passive"))
      (node (ref "UDLDG8") (pin "10") (pinfunction "COM_10") (pintype "passive"))
      (node (ref "UDLDG9") (pin "10") (pinfunction "COM_10") (pintype "passive"))
    )
    (net (code "763") (name "VREF+") (class "Default")
      (node (ref "C15") (pin "2") (pinfunction "2_2") (pintype "passive"))
      (node (ref "CA2") (pin "1") (pinfunction "1_1") (pintype "passive"))
      (node (ref "U3") (pin "6") (pinfunction "OUTPUT_6") (pintype "passive"))
      (node (ref "U5") (pin "41") (pinfunction "VREF+_41") (pintype "passive"))
    )
    (net (code "764") (name "V_SPK") (class "Default")
      (node (ref "C32") (pin "2") (pintype "passive"))
      (node (ref "P3") (pin "2") (pinfunction "2_2") (pintype "passive"))
      (node (ref "U6") (pin "6") (pinfunction "VDD_6") (pintype "passive"))
    )
    (net (code "765") (name "unconnected-(*R1-Pad1)") (class "Default")
      (node (ref "*R1") (pin "1") (pintype "passive"))
    )
    (net (code "766") (name "unconnected-(DC1-Pad3)") (class "Default")
      (node (ref "DC1") (pin "3") (pinfunction "3_3") (pintype "passive"))
    )
    (net (code "767") (name "unconnected-(J1-CD-Pad10)") (class "Default")
      (node (ref "J1") (pin "10") (pinfunction "CD_10") (pintype "passive"))
    )
    (net (code "768") (name "unconnected-(J1-GND-Pad12)") (class "Default")
      (node (ref "J1") (pin "12") (pinfunction "GND_12") (pintype "passive"))
    )
    (net (code "769") (name "unconnected-(J1-GND-Pad13)") (class "Default")
      (node (ref "J1") (pin "13") (pinfunction "GND_13") (pintype "passive"))
    )
    (net (code "770") (name "unconnected-(J1-WP-Pad11)") (class "Default")
      (node (ref "J1") (pin "11") (pinfunction "WP_11") (pintype "passive"))
    )
    (net (code "771") (name "unconnected-(U3-NC-Pad7)") (class "Default")
      (node (ref "U3") (pin "7") (pinfunction "NC_7") (pintype "passive"))
    )
    (net (code "772") (name "unconnected-(U3-NC-Pad8)") (class "Default")
      (node (ref "U3") (pin "8") (pinfunction "NC_8") (pintype "passive"))
    )
    (net (code "773") (name "unconnected-(U3-TP-Pad1)") (class "Default")
      (node (ref "U3") (pin "1") (pinfunction "TP_1") (pintype "passive"))
    )
    (net (code "774") (name "unconnected-(U3-TP-Pad5)") (class "Default")
      (node (ref "U3") (pin "5") (pinfunction "TP_5") (pintype "passive"))
    )
    (net (code "775") (name "unconnected-(U3-~{SLEEP}-Pad3)") (class "Default")
      (node (ref "U3") (pin "3") (pinfunction "~{SLEEP}_3") (pintype "passive"))
    )
    (net (code "776") (name "unconnected-(U4-AO_N-Pad9)") (class "Default")
      (node (ref "U4") (pin "9") (pinfunction "AO_N_9") (pintype "passive"))
    )
    (net (code "777") (name "unconnected-(U4-NC-Pad5)") (class "Default")
      (node (ref "U4") (pin "5") (pinfunction "NC_5") (pintype "passive"))
    )
    (net (code "778") (name "unconnected-(U4-NC-Pad6)") (class "Default")
      (node (ref "U4") (pin "6") (pinfunction "NC_6") (pintype "passive"))
    )
    (net (code "779") (name "unconnected-(U4-NC-Pad19)") (class "Default")
      (node (ref "U4") (pin "19") (pinfunction "NC_19") (pintype "passive"))
    )
    (net (code "780") (name "unconnected-(U4-NC-Pad30)") (class "Default")
      (node (ref "U4") (pin "30") (pinfunction "NC_30") (pintype "passive"))
    )
    (net (code "781") (name "unconnected-(U4-NC-Pad31)") (class "Default")
      (node (ref "U4") (pin "31") (pinfunction "NC_31") (pintype "passive"))
    )
    (net (code "782") (name "unconnected-(U4-NC-Pad32)") (class "Default")
      (node (ref "U4") (pin "32") (pinfunction "NC_32") (pintype "passive"))
    )
    (net (code "783") (name "unconnected-(U4-NC-Pad33)") (class "Default")
      (node (ref "U4") (pin "33") (pinfunction "NC_33") (pintype "passive"))
    )
    (net (code "784") (name "unconnected-(U4-NC-Pad34)") (class "Default")
      (node (ref "U4") (pin "34") (pinfunction "NC_34") (pintype "passive"))
    )
    (net (code "785") (name "unconnected-(U4-NC-Pad35)") (class "Default")
      (node (ref "U4") (pin "35") (pinfunction "NC_35") (pintype "passive"))
    )
    (net (code "786") (name "unconnected-(U4-NC-Pad38)") (class "Default")
      (node (ref "U4") (pin "38") (pinfunction "NC_38") (pintype "passive"))
    )
    (net (code "787") (name "unconnected-(U4-NC-Pad58)") (class "Default")
      (node (ref "U4") (pin "58") (pinfunction "NC_58") (pintype "passive"))
    )
    (net (code "788") (name "unconnected-(U4-NC-Pad61)") (class "Default")
      (node (ref "U4") (pin "61") (pinfunction "NC_61") (pintype "passive"))
    )
    (net (code "789") (name "unconnected-(U4-NC-Pad63)") (class "Default")
      (node (ref "U4") (pin "63") (pinfunction "NC_63") (pintype "passive"))
    )
    (net (code "790") (name "unconnected-(U5-0-Pad113)") (class "Default")
      (node (ref "U5") (pin "113") (pinfunction "0_113") (pintype "passive"))
    )
    (net (code "791") (name "unconnected-(U5-PB3{slash}JTDO{slash}TRACESWO{slash}TIM2_CH2{slash}SPI1_SCK{slash}SPI3_SCK{slash}I2S3_CK-Pad192)") (class "Default")
      (node (ref "U5") (pin "192") (pinfunction "PB3/JTDO/TRACESWO/TIM2_CH2/SPI1_SCK/SPI3_SCK/I2S3_CK_192") (pintype "passive"))
    )
    (net (code "792") (name "unconnected-(U5-PB5{slash}TIM3_CH2{slash}I2C1_SMBA{slash}SPI1_MOSI{slash}SPI3_MOSI{slash}I2S3_SD{slash}CAN2_RX{slash}OTG_HS_ULPI_D7{slash}ETH_PPS_OUT{slash}FMC_SDCKE1-Pad194)") (class "Default")
      (node (ref "U5") (pin "194") (pinfunction "PB5/TIM3_CH2/I2C1_SMBA/SPI1_MOSI/SPI3_MOSI/I2S3_SD/CAN2_RX/OTG_HS_ULPI_D7/ETH_PPS_OUT/FMC_SDCKE1_194") (pintype "passive"))
    )
    (net (code "793") (name "unconnected-(U5-PF10{slash}FMC_INTR{slash}DCMI_D11{slash}__LCD_DE-Pad31)") (class "Default")
      (node (ref "U5") (pin "31") (pinfunction "PF10/FMC_INTR/DCMI_D11/__LCD_DE_31") (pintype "passive"))
    )
    (net (code "794") (name "unconnected-(U5-PG10{slash}LCD_G3{slash}_FMC_NCE4_1{slash}FMC_NE3{slash}DCMI_D2{slash}_LCD_B2-Pad179)") (class "Default")
      (node (ref "U5") (pin "179") (pinfunction "PG10/LCD_G3/_FMC_NCE4_1/FMC_NE3/DCMI_D2/_LCD_B2_179") (pintype "passive"))
    )
    (net (code "795") (name "unconnected-(U5-PH3{slash}ETH_MII_COL{slash}FMC_SDNE0{slash}_LCD_R1-Pad47)") (class "Default")
      (node (ref "U5") (pin "47") (pinfunction "PH3/ETH_MII_COL/FMC_SDNE0/_LCD_R1_47") (pintype "passive"))
    )
    (net (code "796") (name "unconnected-(U5-Pad0)") (class "Default")
      (node (ref "U5") (pin "0") (pinfunction "0_0") (pintype "passive"))
    )
    (net (code "797") (name "unconnected-(U9-CTS#-Pad9)") (class "Default")
      (node (ref "U9") (pin "9") (pinfunction "CTS#_9") (pintype "passive"))
    )
    (net (code "798") (name "unconnected-(U9-DCD#-Pad12)") (class "Default")
      (node (ref "U9") (pin "12") (pinfunction "DCD#_12") (pintype "passive"))
    )
    (net (code "799") (name "unconnected-(U9-DSR#-Pad10)") (class "Default")
      (node (ref "U9") (pin "10") (pinfunction "DSR#_10") (pintype "passive"))
    )
    (net (code "800") (name "unconnected-(U9-R232-Pad15)") (class "Default")
      (node (ref "U9") (pin "15") (pinfunction "R232_15") (pintype "passive"))
    )
    (net (code "801") (name "unconnected-(U9-RI#-Pad11)") (class "Default")
      (node (ref "U9") (pin "11") (pinfunction "RI#_11") (pintype "passive"))
    )
    (net (code "802") (name "unconnected-(USB_1-NC-Pad4)") (class "Default")
      (node (ref "USB_1") (pin "4") (pinfunction "NC_4") (pintype "passive"))
    )
  )
)
